# ASIC_card.net
KiCad netlist of a schematic drawn in EAGLE
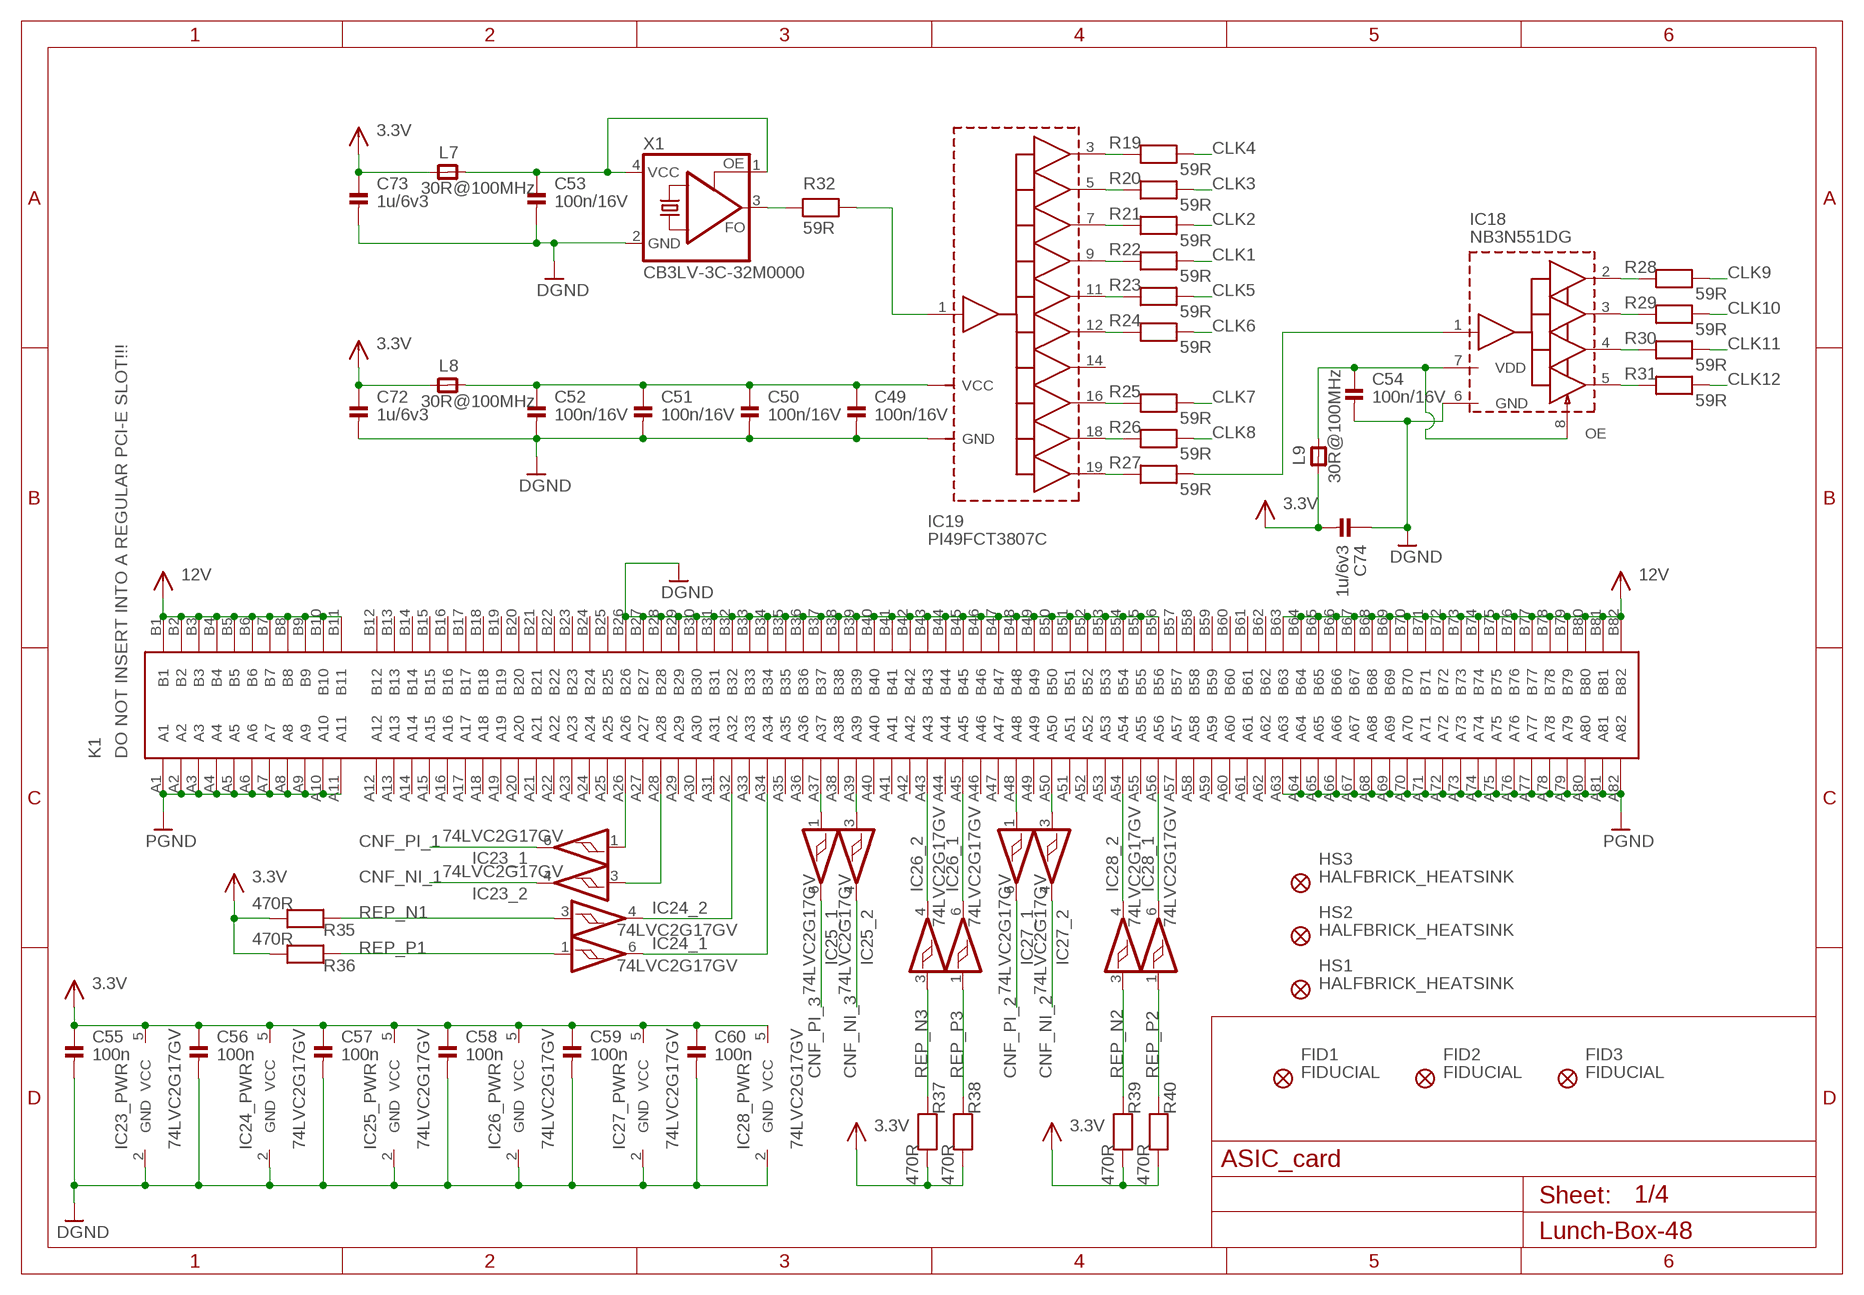
[diagram p0: schematic, sheet 1]
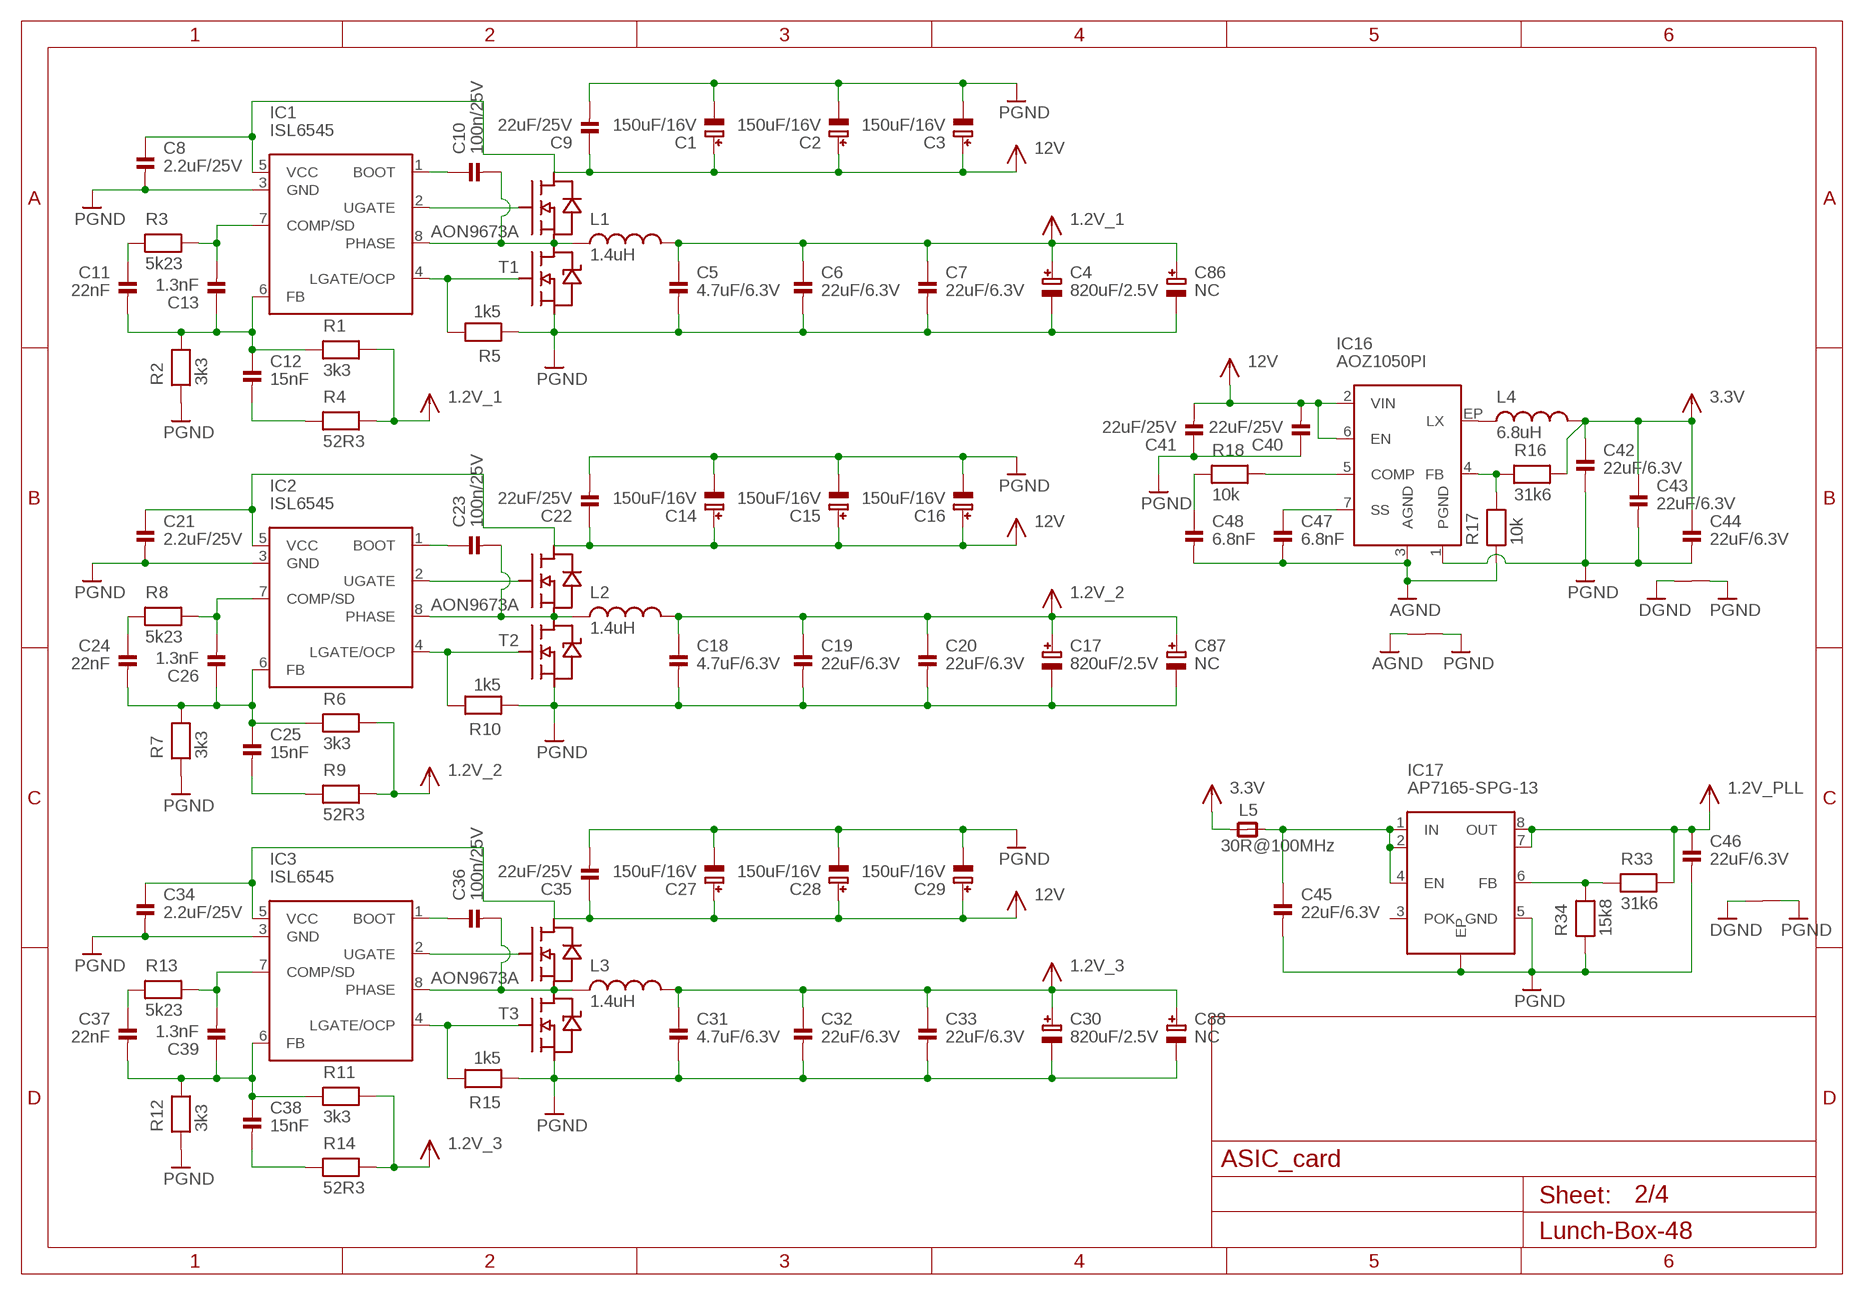
[diagram p1: schematic, sheet 2]
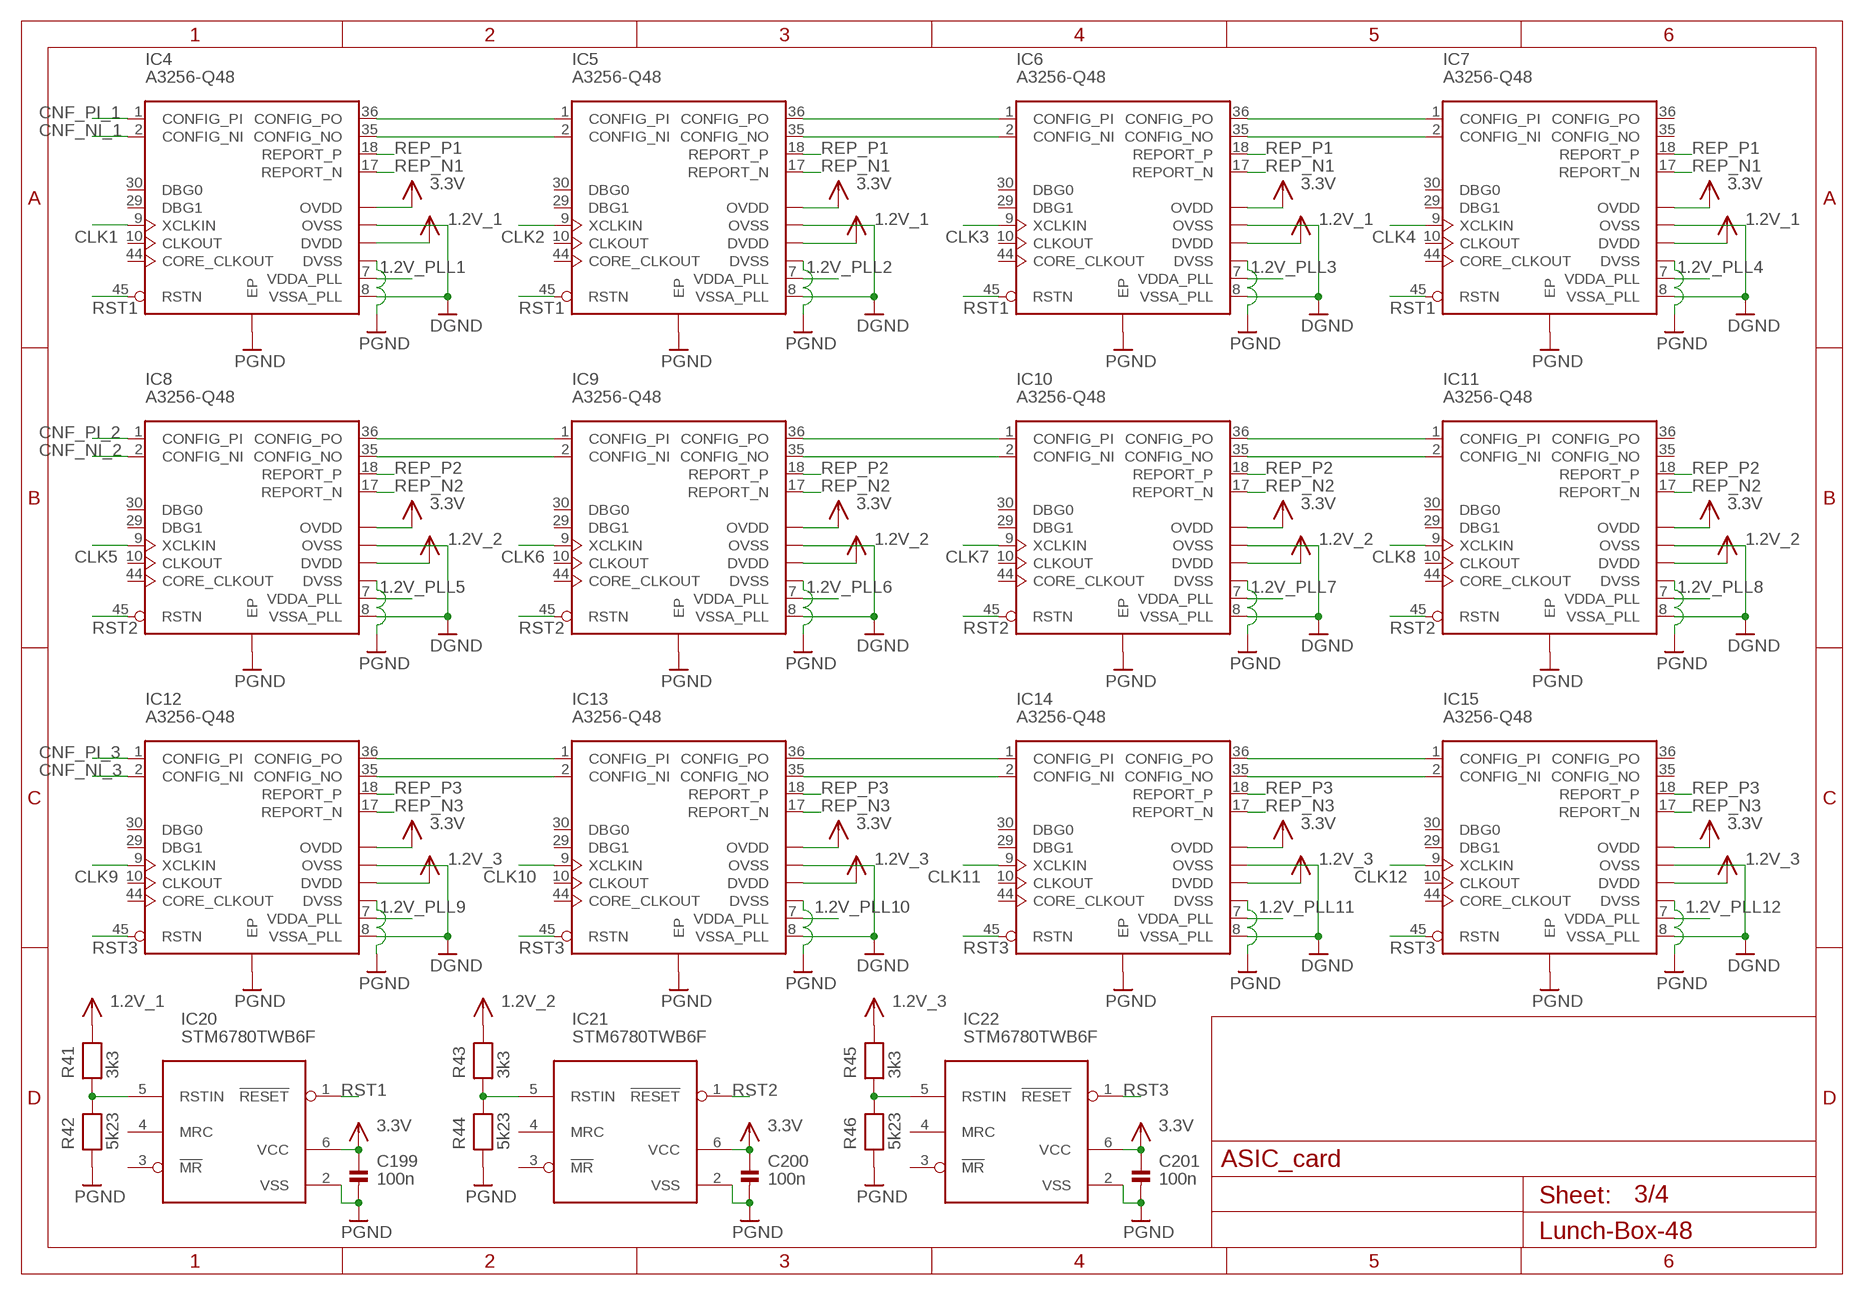
[diagram p2: schematic, sheet 3]
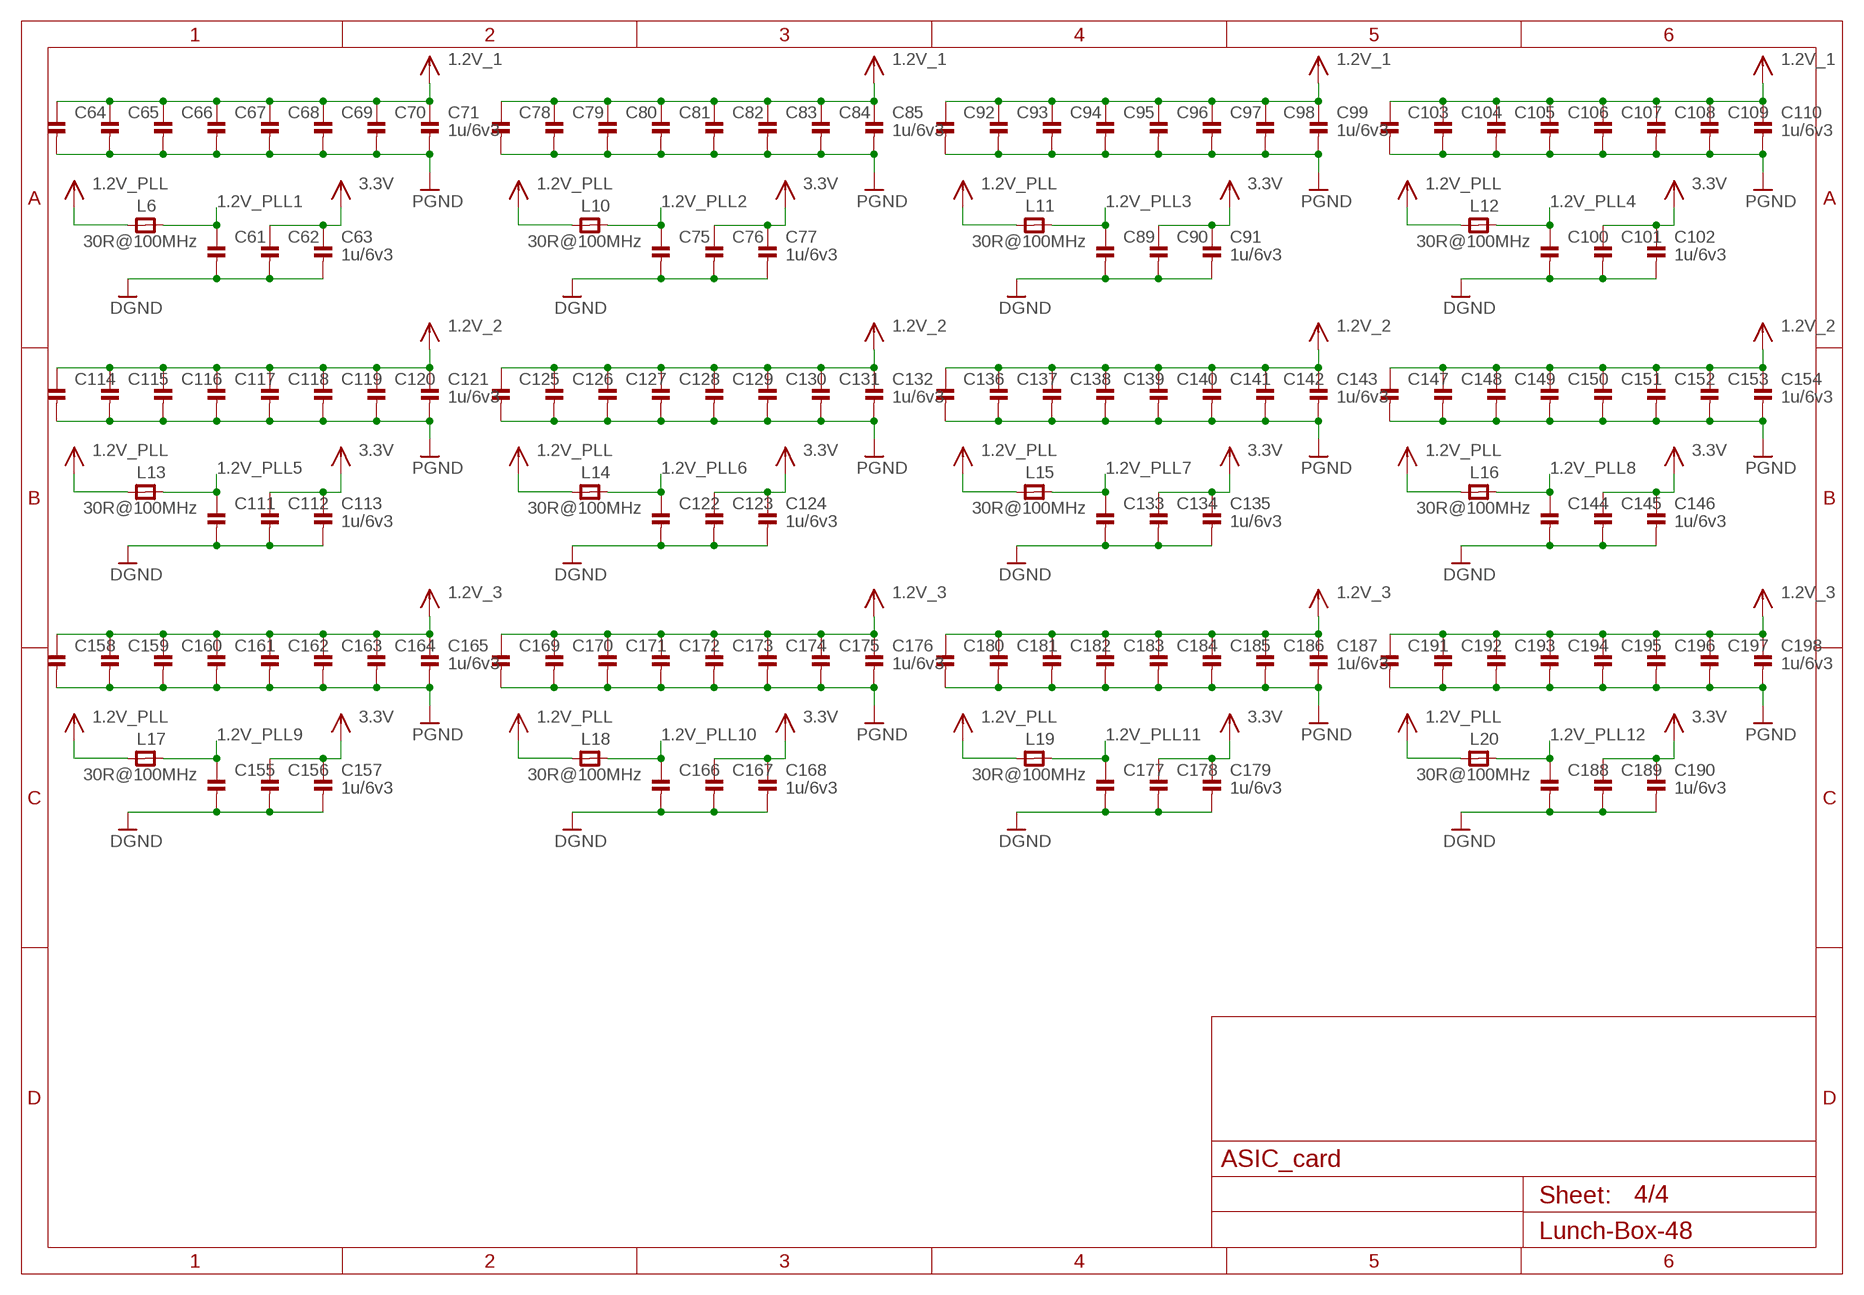
[diagram p3: schematic, sheet 4]

(export (version "E")
  (design (tool "Eeschema 10.0.6"))
  (components
    (comp (ref "C49")
      (value "100n/16V")
      (footprint "eagle-import:0402")
      (libsource (lib "eagle-import") (part "C0402"))
    )
    (comp (ref "C50")
      (value "100n/16V")
      (footprint "eagle-import:0402")
      (libsource (lib "eagle-import") (part "C0402"))
    )
    (comp (ref "C51")
      (value "100n/16V")
      (footprint "eagle-import:0402")
      (libsource (lib "eagle-import") (part "C0402"))
    )
    (comp (ref "C52")
      (value "100n/16V")
      (footprint "eagle-import:0402")
      (libsource (lib "eagle-import") (part "C0402"))
    )
    (comp (ref "C53")
      (value "100n/16V")
      (footprint "eagle-import:0402")
      (libsource (lib "eagle-import") (part "C0402"))
    )
    (comp (ref "C54")
      (value "100n/16V")
      (footprint "eagle-import:0402")
      (libsource (lib "eagle-import") (part "C0402"))
    )
    (comp (ref "C55")
      (value "100n")
      (footprint "eagle-import:0603")
      (libsource (lib "eagle-import") (part "C0603"))
    )
    (comp (ref "C56")
      (value "100n")
      (footprint "eagle-import:0603")
      (libsource (lib "eagle-import") (part "C0603"))
    )
    (comp (ref "C57")
      (value "100n")
      (footprint "eagle-import:0603")
      (libsource (lib "eagle-import") (part "C0603"))
    )
    (comp (ref "C58")
      (value "100n")
      (footprint "eagle-import:0603")
      (libsource (lib "eagle-import") (part "C0603"))
    )
    (comp (ref "C59")
      (value "100n")
      (footprint "eagle-import:0603")
      (libsource (lib "eagle-import") (part "C0603"))
    )
    (comp (ref "C60")
      (value "100n")
      (footprint "eagle-import:0603")
      (libsource (lib "eagle-import") (part "C0603"))
    )
    (comp (ref "C72")
      (value "1u/6v3")
      (footprint "eagle-import:0402")
      (libsource (lib "eagle-import") (part "C0402"))
    )
    (comp (ref "C73")
      (value "1u/6v3")
      (footprint "eagle-import:0402")
      (libsource (lib "eagle-import") (part "C0402"))
    )
    (comp (ref "C74")
      (value "1u/6v3")
      (footprint "eagle-import:0402")
      (libsource (lib "eagle-import") (part "C0402"))
    )
    (comp (ref "FID1")
      (value "FIDUCIAL")
      (footprint "eagle-import:FID_1X2,5")
      (libsource (lib "eagle-import") (part "FIDUCIAL"))
    )
    (comp (ref "FID2")
      (value "FIDUCIAL")
      (footprint "eagle-import:FID_1X2,5")
      (libsource (lib "eagle-import") (part "FIDUCIAL"))
    )
    (comp (ref "FID3")
      (value "FIDUCIAL")
      (footprint "eagle-import:FID_1X2,5")
      (libsource (lib "eagle-import") (part "FIDUCIAL"))
    )
    (comp (ref "HS1")
      (value "HALFBRICK_HEATSINK")
      (footprint "eagle-import:1_2_BRICK_HEATSINK")
      (libsource (lib "eagle-import") (part "HALFBRICK_HEATSINK"))
    )
    (comp (ref "HS2")
      (value "HALFBRICK_HEATSINK")
      (footprint "eagle-import:1_2_BRICK_HEATSINK")
      (libsource (lib "eagle-import") (part "HALFBRICK_HEATSINK"))
    )
    (comp (ref "HS3")
      (value "HALFBRICK_HEATSINK")
      (footprint "eagle-import:1_2_BRICK_HEATSINK")
      (libsource (lib "eagle-import") (part "HALFBRICK_HEATSINK"))
    )
    (comp (ref "IC18")
      (value "NB3N551DG")
      (footprint "eagle-import:SO-8")
      (libsource (lib "eagle-import") (part "NB3N551DG"))
    )
    (comp (ref "IC19")
      (value "PI49FCT3807C")
      (footprint "eagle-import:SSOP-20")
      (libsource (lib "eagle-import") (part "PI49FCT3807C"))
    )
    (comp (ref "IC23")
      (value "74LVC2G17GV")
      (footprint "eagle-import:SOT23-6")
      (libsource (lib "eagle-import") (part "74LVC2G17GV"))
    )
    (comp (ref "IC24")
      (value "74LVC2G17GV")
      (footprint "eagle-import:SOT23-6")
      (libsource (lib "eagle-import") (part "74LVC2G17GV"))
    )
    (comp (ref "IC25")
      (value "74LVC2G17GV")
      (footprint "eagle-import:SOT23-6")
      (libsource (lib "eagle-import") (part "74LVC2G17GV"))
    )
    (comp (ref "IC26")
      (value "74LVC2G17GV")
      (footprint "eagle-import:SOT23-6")
      (libsource (lib "eagle-import") (part "74LVC2G17GV"))
    )
    (comp (ref "IC27")
      (value "74LVC2G17GV")
      (footprint "eagle-import:SOT23-6")
      (libsource (lib "eagle-import") (part "74LVC2G17GV"))
    )
    (comp (ref "IC28")
      (value "74LVC2G17GV")
      (footprint "eagle-import:SOT23-6")
      (libsource (lib "eagle-import") (part "74LVC2G17GV"))
    )
    (comp (ref "K1")
      (value "DO NOT INSERT INTO A REGULAR PCI-E SLOT!!!")
      (footprint "eagle-import:PCI-E_16X")
      (libsource (lib "eagle-import") (part "PCI-E_CARDEDGE"))
    )
    (comp (ref "L7")
      (value "30R@100MHz")
      (footprint "eagle-import:0603")
      (libsource (lib "eagle-import") (part "FERRITE0603"))
    )
    (comp (ref "L8")
      (value "30R@100MHz")
      (footprint "eagle-import:0603")
      (libsource (lib "eagle-import") (part "FERRITE0603"))
    )
    (comp (ref "L9")
      (value "30R@100MHz")
      (footprint "eagle-import:0603")
      (libsource (lib "eagle-import") (part "FERRITE0603"))
    )
    (comp (ref "R19")
      (value "59R")
      (footprint "eagle-import:0402")
      (libsource (lib "eagle-import") (part "R0402"))
    )
    (comp (ref "R20")
      (value "59R")
      (footprint "eagle-import:0402")
      (libsource (lib "eagle-import") (part "R0402"))
    )
    (comp (ref "R21")
      (value "59R")
      (footprint "eagle-import:0402")
      (libsource (lib "eagle-import") (part "R0402"))
    )
    (comp (ref "R22")
      (value "59R")
      (footprint "eagle-import:0402")
      (libsource (lib "eagle-import") (part "R0402"))
    )
    (comp (ref "R23")
      (value "59R")
      (footprint "eagle-import:0402")
      (libsource (lib "eagle-import") (part "R0402"))
    )
    (comp (ref "R24")
      (value "59R")
      (footprint "eagle-import:0402")
      (libsource (lib "eagle-import") (part "R0402"))
    )
    (comp (ref "R25")
      (value "59R")
      (footprint "eagle-import:0402")
      (libsource (lib "eagle-import") (part "R0402"))
    )
    (comp (ref "R26")
      (value "59R")
      (footprint "eagle-import:0402")
      (libsource (lib "eagle-import") (part "R0402"))
    )
    (comp (ref "R27")
      (value "59R")
      (footprint "eagle-import:0402")
      (libsource (lib "eagle-import") (part "R0402"))
    )
    (comp (ref "R28")
      (value "59R")
      (footprint "eagle-import:0402")
      (libsource (lib "eagle-import") (part "R0402"))
    )
    (comp (ref "R29")
      (value "59R")
      (footprint "eagle-import:0402")
      (libsource (lib "eagle-import") (part "R0402"))
    )
    (comp (ref "R30")
      (value "59R")
      (footprint "eagle-import:0402")
      (libsource (lib "eagle-import") (part "R0402"))
    )
    (comp (ref "R31")
      (value "59R")
      (footprint "eagle-import:0402")
      (libsource (lib "eagle-import") (part "R0402"))
    )
    (comp (ref "R32")
      (value "59R")
      (footprint "eagle-import:0402")
      (libsource (lib "eagle-import") (part "R0402"))
    )
    (comp (ref "R35")
      (value "470R")
      (footprint "eagle-import:0603")
      (libsource (lib "eagle-import") (part "R0603"))
    )
    (comp (ref "R36")
      (value "470R")
      (footprint "eagle-import:0603")
      (libsource (lib "eagle-import") (part "R0603"))
    )
    (comp (ref "R37")
      (value "470R")
      (footprint "eagle-import:0603")
      (libsource (lib "eagle-import") (part "R0603"))
    )
    (comp (ref "R38")
      (value "470R")
      (footprint "eagle-import:0603")
      (libsource (lib "eagle-import") (part "R0603"))
    )
    (comp (ref "R39")
      (value "470R")
      (footprint "eagle-import:0603")
      (libsource (lib "eagle-import") (part "R0603"))
    )
    (comp (ref "R40")
      (value "470R")
      (footprint "eagle-import:0603")
      (libsource (lib "eagle-import") (part "R0603"))
    )
    (comp (ref "X1")
      (value "CB3LV-3C-32M0000")
      (footprint "eagle-import:7X5_OSC")
      (libsource (lib "eagle-import") (part "CB3LV-3C-32M0000"))
    )
    (comp (ref "C199")
      (value "100n")
      (footprint "eagle-import:0603")
      (libsource (lib "eagle-import") (part "C0603"))
    )
    (comp (ref "C200")
      (value "100n")
      (footprint "eagle-import:0603")
      (libsource (lib "eagle-import") (part "C0603"))
    )
    (comp (ref "C201")
      (value "100n")
      (footprint "eagle-import:0603")
      (libsource (lib "eagle-import") (part "C0603"))
    )
    (comp (ref "IC4")
      (value "A3256-Q48")
      (footprint "eagle-import:QFN48_EP")
      (libsource (lib "eagle-import") (part "A3256-Q48"))
    )
    (comp (ref "IC5")
      (value "A3256-Q48")
      (footprint "eagle-import:QFN48_EP")
      (libsource (lib "eagle-import") (part "A3256-Q48"))
    )
    (comp (ref "IC6")
      (value "A3256-Q48")
      (footprint "eagle-import:QFN48_EP")
      (libsource (lib "eagle-import") (part "A3256-Q48"))
    )
    (comp (ref "IC7")
      (value "A3256-Q48")
      (footprint "eagle-import:QFN48_EP")
      (libsource (lib "eagle-import") (part "A3256-Q48"))
    )
    (comp (ref "IC8")
      (value "A3256-Q48")
      (footprint "eagle-import:QFN48_EP")
      (libsource (lib "eagle-import") (part "A3256-Q48"))
    )
    (comp (ref "IC9")
      (value "A3256-Q48")
      (footprint "eagle-import:QFN48_EP")
      (libsource (lib "eagle-import") (part "A3256-Q48"))
    )
    (comp (ref "IC10")
      (value "A3256-Q48")
      (footprint "eagle-import:QFN48_EP")
      (libsource (lib "eagle-import") (part "A3256-Q48"))
    )
    (comp (ref "IC11")
      (value "A3256-Q48")
      (footprint "eagle-import:QFN48_EP")
      (libsource (lib "eagle-import") (part "A3256-Q48"))
    )
    (comp (ref "IC12")
      (value "A3256-Q48")
      (footprint "eagle-import:QFN48_EP")
      (libsource (lib "eagle-import") (part "A3256-Q48"))
    )
    (comp (ref "IC13")
      (value "A3256-Q48")
      (footprint "eagle-import:QFN48_EP")
      (libsource (lib "eagle-import") (part "A3256-Q48"))
    )
    (comp (ref "IC14")
      (value "A3256-Q48")
      (footprint "eagle-import:QFN48_EP")
      (libsource (lib "eagle-import") (part "A3256-Q48"))
    )
    (comp (ref "IC15")
      (value "A3256-Q48")
      (footprint "eagle-import:QFN48_EP")
      (libsource (lib "eagle-import") (part "A3256-Q48"))
    )
    (comp (ref "IC20")
      (value "STM6780TWB6F")
      (footprint "eagle-import:SOT23-6")
      (libsource (lib "eagle-import") (part "STM6780TWB6F"))
    )
    (comp (ref "IC21")
      (value "STM6780TWB6F")
      (footprint "eagle-import:SOT23-6")
      (libsource (lib "eagle-import") (part "STM6780TWB6F"))
    )
    (comp (ref "IC22")
      (value "STM6780TWB6F")
      (footprint "eagle-import:SOT23-6")
      (libsource (lib "eagle-import") (part "STM6780TWB6F"))
    )
    (comp (ref "R41")
      (value "3k3")
      (footprint "eagle-import:0603")
      (libsource (lib "eagle-import") (part "R0603"))
    )
    (comp (ref "R42")
      (value "5k23")
      (footprint "eagle-import:0603")
      (libsource (lib "eagle-import") (part "R0603"))
    )
    (comp (ref "R43")
      (value "3k3")
      (footprint "eagle-import:0603")
      (libsource (lib "eagle-import") (part "R0603"))
    )
    (comp (ref "R44")
      (value "5k23")
      (footprint "eagle-import:0603")
      (libsource (lib "eagle-import") (part "R0603"))
    )
    (comp (ref "R45")
      (value "3k3")
      (footprint "eagle-import:0603")
      (libsource (lib "eagle-import") (part "R0603"))
    )
    (comp (ref "R46")
      (value "5k23")
      (footprint "eagle-import:0603")
      (libsource (lib "eagle-import") (part "R0603"))
    )
    (comp (ref "C61")
      (value "1u/6v3")
      (footprint "eagle-import:0402")
      (libsource (lib "eagle-import") (part "C0402"))
    )
    (comp (ref "C62")
      (value "1u/6v3")
      (footprint "eagle-import:0402")
      (libsource (lib "eagle-import") (part "C0402"))
    )
    (comp (ref "C63")
      (value "1u/6v3")
      (footprint "eagle-import:0402")
      (libsource (lib "eagle-import") (part "C0402"))
    )
    (comp (ref "C64")
      (value "1u/6v3")
      (footprint "eagle-import:0402")
      (libsource (lib "eagle-import") (part "C0402"))
    )
    (comp (ref "C65")
      (value "1u/6v3")
      (footprint "eagle-import:0402")
      (libsource (lib "eagle-import") (part "C0402"))
    )
    (comp (ref "C66")
      (value "1u/6v3")
      (footprint "eagle-import:0402")
      (libsource (lib "eagle-import") (part "C0402"))
    )
    (comp (ref "C67")
      (value "1u/6v3")
      (footprint "eagle-import:0402")
      (libsource (lib "eagle-import") (part "C0402"))
    )
    (comp (ref "C68")
      (value "1u/6v3")
      (footprint "eagle-import:0402")
      (libsource (lib "eagle-import") (part "C0402"))
    )
    (comp (ref "C69")
      (value "1u/6v3")
      (footprint "eagle-import:0402")
      (libsource (lib "eagle-import") (part "C0402"))
    )
    (comp (ref "C70")
      (value "1u/6v3")
      (footprint "eagle-import:0402")
      (libsource (lib "eagle-import") (part "C0402"))
    )
    (comp (ref "C71")
      (value "1u/6v3")
      (footprint "eagle-import:0402")
      (libsource (lib "eagle-import") (part "C0402"))
    )
    (comp (ref "C75")
      (value "1u/6v3")
      (footprint "eagle-import:0402")
      (libsource (lib "eagle-import") (part "C0402"))
    )
    (comp (ref "C76")
      (value "1u/6v3")
      (footprint "eagle-import:0402")
      (libsource (lib "eagle-import") (part "C0402"))
    )
    (comp (ref "C77")
      (value "1u/6v3")
      (footprint "eagle-import:0402")
      (libsource (lib "eagle-import") (part "C0402"))
    )
    (comp (ref "C78")
      (value "1u/6v3")
      (footprint "eagle-import:0402")
      (libsource (lib "eagle-import") (part "C0402"))
    )
    (comp (ref "C79")
      (value "1u/6v3")
      (footprint "eagle-import:0402")
      (libsource (lib "eagle-import") (part "C0402"))
    )
    (comp (ref "C80")
      (value "1u/6v3")
      (footprint "eagle-import:0402")
      (libsource (lib "eagle-import") (part "C0402"))
    )
    (comp (ref "C81")
      (value "1u/6v3")
      (footprint "eagle-import:0402")
      (libsource (lib "eagle-import") (part "C0402"))
    )
    (comp (ref "C82")
      (value "1u/6v3")
      (footprint "eagle-import:0402")
      (libsource (lib "eagle-import") (part "C0402"))
    )
    (comp (ref "C83")
      (value "1u/6v3")
      (footprint "eagle-import:0402")
      (libsource (lib "eagle-import") (part "C0402"))
    )
    (comp (ref "C84")
      (value "1u/6v3")
      (footprint "eagle-import:0402")
      (libsource (lib "eagle-import") (part "C0402"))
    )
    (comp (ref "C85")
      (value "1u/6v3")
      (footprint "eagle-import:0402")
      (libsource (lib "eagle-import") (part "C0402"))
    )
    (comp (ref "C89")
      (value "1u/6v3")
      (footprint "eagle-import:0402")
      (libsource (lib "eagle-import") (part "C0402"))
    )
    (comp (ref "C90")
      (value "1u/6v3")
      (footprint "eagle-import:0402")
      (libsource (lib "eagle-import") (part "C0402"))
    )
    (comp (ref "C91")
      (value "1u/6v3")
      (footprint "eagle-import:0402")
      (libsource (lib "eagle-import") (part "C0402"))
    )
    (comp (ref "C92")
      (value "1u/6v3")
      (footprint "eagle-import:0402")
      (libsource (lib "eagle-import") (part "C0402"))
    )
    (comp (ref "C93")
      (value "1u/6v3")
      (footprint "eagle-import:0402")
      (libsource (lib "eagle-import") (part "C0402"))
    )
    (comp (ref "C94")
      (value "1u/6v3")
      (footprint "eagle-import:0402")
      (libsource (lib "eagle-import") (part "C0402"))
    )
    (comp (ref "C95")
      (value "1u/6v3")
      (footprint "eagle-import:0402")
      (libsource (lib "eagle-import") (part "C0402"))
    )
    (comp (ref "C96")
      (value "1u/6v3")
      (footprint "eagle-import:0402")
      (libsource (lib "eagle-import") (part "C0402"))
    )
    (comp (ref "C97")
      (value "1u/6v3")
      (footprint "eagle-import:0402")
      (libsource (lib "eagle-import") (part "C0402"))
    )
    (comp (ref "C98")
      (value "1u/6v3")
      (footprint "eagle-import:0402")
      (libsource (lib "eagle-import") (part "C0402"))
    )
    (comp (ref "C99")
      (value "1u/6v3")
      (footprint "eagle-import:0402")
      (libsource (lib "eagle-import") (part "C0402"))
    )
    (comp (ref "C100")
      (value "1u/6v3")
      (footprint "eagle-import:0402")
      (libsource (lib "eagle-import") (part "C0402"))
    )
    (comp (ref "C101")
      (value "1u/6v3")
      (footprint "eagle-import:0402")
      (libsource (lib "eagle-import") (part "C0402"))
    )
    (comp (ref "C102")
      (value "1u/6v3")
      (footprint "eagle-import:0402")
      (libsource (lib "eagle-import") (part "C0402"))
    )
    (comp (ref "C103")
      (value "1u/6v3")
      (footprint "eagle-import:0402")
      (libsource (lib "eagle-import") (part "C0402"))
    )
    (comp (ref "C104")
      (value "1u/6v3")
      (footprint "eagle-import:0402")
      (libsource (lib "eagle-import") (part "C0402"))
    )
    (comp (ref "C105")
      (value "1u/6v3")
      (footprint "eagle-import:0402")
      (libsource (lib "eagle-import") (part "C0402"))
    )
    (comp (ref "C106")
      (value "1u/6v3")
      (footprint "eagle-import:0402")
      (libsource (lib "eagle-import") (part "C0402"))
    )
    (comp (ref "C107")
      (value "1u/6v3")
      (footprint "eagle-import:0402")
      (libsource (lib "eagle-import") (part "C0402"))
    )
    (comp (ref "C108")
      (value "1u/6v3")
      (footprint "eagle-import:0402")
      (libsource (lib "eagle-import") (part "C0402"))
    )
    (comp (ref "C109")
      (value "1u/6v3")
      (footprint "eagle-import:0402")
      (libsource (lib "eagle-import") (part "C0402"))
    )
    (comp (ref "C110")
      (value "1u/6v3")
      (footprint "eagle-import:0402")
      (libsource (lib "eagle-import") (part "C0402"))
    )
    (comp (ref "C111")
      (value "1u/6v3")
      (footprint "eagle-import:0402")
      (libsource (lib "eagle-import") (part "C0402"))
    )
    (comp (ref "C112")
      (value "1u/6v3")
      (footprint "eagle-import:0402")
      (libsource (lib "eagle-import") (part "C0402"))
    )
    (comp (ref "C113")
      (value "1u/6v3")
      (footprint "eagle-import:0402")
      (libsource (lib "eagle-import") (part "C0402"))
    )
    (comp (ref "C114")
      (value "1u/6v3")
      (footprint "eagle-import:0402")
      (libsource (lib "eagle-import") (part "C0402"))
    )
    (comp (ref "C115")
      (value "1u/6v3")
      (footprint "eagle-import:0402")
      (libsource (lib "eagle-import") (part "C0402"))
    )
    (comp (ref "C116")
      (value "1u/6v3")
      (footprint "eagle-import:0402")
      (libsource (lib "eagle-import") (part "C0402"))
    )
    (comp (ref "C117")
      (value "1u/6v3")
      (footprint "eagle-import:0402")
      (libsource (lib "eagle-import") (part "C0402"))
    )
    (comp (ref "C118")
      (value "1u/6v3")
      (footprint "eagle-import:0402")
      (libsource (lib "eagle-import") (part "C0402"))
    )
    (comp (ref "C119")
      (value "1u/6v3")
      (footprint "eagle-import:0402")
      (libsource (lib "eagle-import") (part "C0402"))
    )
    (comp (ref "C120")
      (value "1u/6v3")
      (footprint "eagle-import:0402")
      (libsource (lib "eagle-import") (part "C0402"))
    )
    (comp (ref "C121")
      (value "1u/6v3")
      (footprint "eagle-import:0402")
      (libsource (lib "eagle-import") (part "C0402"))
    )
    (comp (ref "C122")
      (value "1u/6v3")
      (footprint "eagle-import:0402")
      (libsource (lib "eagle-import") (part "C0402"))
    )
    (comp (ref "C123")
      (value "1u/6v3")
      (footprint "eagle-import:0402")
      (libsource (lib "eagle-import") (part "C0402"))
    )
    (comp (ref "C124")
      (value "1u/6v3")
      (footprint "eagle-import:0402")
      (libsource (lib "eagle-import") (part "C0402"))
    )
    (comp (ref "C125")
      (value "1u/6v3")
      (footprint "eagle-import:0402")
      (libsource (lib "eagle-import") (part "C0402"))
    )
    (comp (ref "C126")
      (value "1u/6v3")
      (footprint "eagle-import:0402")
      (libsource (lib "eagle-import") (part "C0402"))
    )
    (comp (ref "C127")
      (value "1u/6v3")
      (footprint "eagle-import:0402")
      (libsource (lib "eagle-import") (part "C0402"))
    )
    (comp (ref "C128")
      (value "1u/6v3")
      (footprint "eagle-import:0402")
      (libsource (lib "eagle-import") (part "C0402"))
    )
    (comp (ref "C129")
      (value "1u/6v3")
      (footprint "eagle-import:0402")
      (libsource (lib "eagle-import") (part "C0402"))
    )
    (comp (ref "C130")
      (value "1u/6v3")
      (footprint "eagle-import:0402")
      (libsource (lib "eagle-import") (part "C0402"))
    )
    (comp (ref "C131")
      (value "1u/6v3")
      (footprint "eagle-import:0402")
      (libsource (lib "eagle-import") (part "C0402"))
    )
    (comp (ref "C132")
      (value "1u/6v3")
      (footprint "eagle-import:0402")
      (libsource (lib "eagle-import") (part "C0402"))
    )
    (comp (ref "C133")
      (value "1u/6v3")
      (footprint "eagle-import:0402")
      (libsource (lib "eagle-import") (part "C0402"))
    )
    (comp (ref "C134")
      (value "1u/6v3")
      (footprint "eagle-import:0402")
      (libsource (lib "eagle-import") (part "C0402"))
    )
    (comp (ref "C135")
      (value "1u/6v3")
      (footprint "eagle-import:0402")
      (libsource (lib "eagle-import") (part "C0402"))
    )
    (comp (ref "C136")
      (value "1u/6v3")
      (footprint "eagle-import:0402")
      (libsource (lib "eagle-import") (part "C0402"))
    )
    (comp (ref "C137")
      (value "1u/6v3")
      (footprint "eagle-import:0402")
      (libsource (lib "eagle-import") (part "C0402"))
    )
    (comp (ref "C138")
      (value "1u/6v3")
      (footprint "eagle-import:0402")
      (libsource (lib "eagle-import") (part "C0402"))
    )
    (comp (ref "C139")
      (value "1u/6v3")
      (footprint "eagle-import:0402")
      (libsource (lib "eagle-import") (part "C0402"))
    )
    (comp (ref "C140")
      (value "1u/6v3")
      (footprint "eagle-import:0402")
      (libsource (lib "eagle-import") (part "C0402"))
    )
    (comp (ref "C141")
      (value "1u/6v3")
      (footprint "eagle-import:0402")
      (libsource (lib "eagle-import") (part "C0402"))
    )
    (comp (ref "C142")
      (value "1u/6v3")
      (footprint "eagle-import:0402")
      (libsource (lib "eagle-import") (part "C0402"))
    )
    (comp (ref "C143")
      (value "1u/6v3")
      (footprint "eagle-import:0402")
      (libsource (lib "eagle-import") (part "C0402"))
    )
    (comp (ref "C144")
      (value "1u/6v3")
      (footprint "eagle-import:0402")
      (libsource (lib "eagle-import") (part "C0402"))
    )
    (comp (ref "C145")
      (value "1u/6v3")
      (footprint "eagle-import:0402")
      (libsource (lib "eagle-import") (part "C0402"))
    )
    (comp (ref "C146")
      (value "1u/6v3")
      (footprint "eagle-import:0402")
      (libsource (lib "eagle-import") (part "C0402"))
    )
    (comp (ref "C147")
      (value "1u/6v3")
      (footprint "eagle-import:0402")
      (libsource (lib "eagle-import") (part "C0402"))
    )
    (comp (ref "C148")
      (value "1u/6v3")
      (footprint "eagle-import:0402")
      (libsource (lib "eagle-import") (part "C0402"))
    )
    (comp (ref "C149")
      (value "1u/6v3")
      (footprint "eagle-import:0402")
      (libsource (lib "eagle-import") (part "C0402"))
    )
    (comp (ref "C150")
      (value "1u/6v3")
      (footprint "eagle-import:0402")
      (libsource (lib "eagle-import") (part "C0402"))
    )
    (comp (ref "C151")
      (value "1u/6v3")
      (footprint "eagle-import:0402")
      (libsource (lib "eagle-import") (part "C0402"))
    )
    (comp (ref "C152")
      (value "1u/6v3")
      (footprint "eagle-import:0402")
      (libsource (lib "eagle-import") (part "C0402"))
    )
    (comp (ref "C153")
      (value "1u/6v3")
      (footprint "eagle-import:0402")
      (libsource (lib "eagle-import") (part "C0402"))
    )
    (comp (ref "C154")
      (value "1u/6v3")
      (footprint "eagle-import:0402")
      (libsource (lib "eagle-import") (part "C0402"))
    )
    (comp (ref "C155")
      (value "1u/6v3")
      (footprint "eagle-import:0402")
      (libsource (lib "eagle-import") (part "C0402"))
    )
    (comp (ref "C156")
      (value "1u/6v3")
      (footprint "eagle-import:0402")
      (libsource (lib "eagle-import") (part "C0402"))
    )
    (comp (ref "C157")
      (value "1u/6v3")
      (footprint "eagle-import:0402")
      (libsource (lib "eagle-import") (part "C0402"))
    )
    (comp (ref "C158")
      (value "1u/6v3")
      (footprint "eagle-import:0402")
      (libsource (lib "eagle-import") (part "C0402"))
    )
    (comp (ref "C159")
      (value "1u/6v3")
      (footprint "eagle-import:0402")
      (libsource (lib "eagle-import") (part "C0402"))
    )
    (comp (ref "C160")
      (value "1u/6v3")
      (footprint "eagle-import:0402")
      (libsource (lib "eagle-import") (part "C0402"))
    )
    (comp (ref "C161")
      (value "1u/6v3")
      (footprint "eagle-import:0402")
      (libsource (lib "eagle-import") (part "C0402"))
    )
    (comp (ref "C162")
      (value "1u/6v3")
      (footprint "eagle-import:0402")
      (libsource (lib "eagle-import") (part "C0402"))
    )
    (comp (ref "C163")
      (value "1u/6v3")
      (footprint "eagle-import:0402")
      (libsource (lib "eagle-import") (part "C0402"))
    )
    (comp (ref "C164")
      (value "1u/6v3")
      (footprint "eagle-import:0402")
      (libsource (lib "eagle-import") (part "C0402"))
    )
    (comp (ref "C165")
      (value "1u/6v3")
      (footprint "eagle-import:0402")
      (libsource (lib "eagle-import") (part "C0402"))
    )
    (comp (ref "C166")
      (value "1u/6v3")
      (footprint "eagle-import:0402")
      (libsource (lib "eagle-import") (part "C0402"))
    )
    (comp (ref "C167")
      (value "1u/6v3")
      (footprint "eagle-import:0402")
      (libsource (lib "eagle-import") (part "C0402"))
    )
    (comp (ref "C168")
      (value "1u/6v3")
      (footprint "eagle-import:0402")
      (libsource (lib "eagle-import") (part "C0402"))
    )
    (comp (ref "C169")
      (value "1u/6v3")
      (footprint "eagle-import:0402")
      (libsource (lib "eagle-import") (part "C0402"))
    )
    (comp (ref "C170")
      (value "1u/6v3")
      (footprint "eagle-import:0402")
      (libsource (lib "eagle-import") (part "C0402"))
    )
    (comp (ref "C171")
      (value "1u/6v3")
      (footprint "eagle-import:0402")
      (libsource (lib "eagle-import") (part "C0402"))
    )
    (comp (ref "C172")
      (value "1u/6v3")
      (footprint "eagle-import:0402")
      (libsource (lib "eagle-import") (part "C0402"))
    )
    (comp (ref "C173")
      (value "1u/6v3")
      (footprint "eagle-import:0402")
      (libsource (lib "eagle-import") (part "C0402"))
    )
    (comp (ref "C174")
      (value "1u/6v3")
      (footprint "eagle-import:0402")
      (libsource (lib "eagle-import") (part "C0402"))
    )
    (comp (ref "C175")
      (value "1u/6v3")
      (footprint "eagle-import:0402")
      (libsource (lib "eagle-import") (part "C0402"))
    )
    (comp (ref "C176")
      (value "1u/6v3")
      (footprint "eagle-import:0402")
      (libsource (lib "eagle-import") (part "C0402"))
    )
    (comp (ref "C177")
      (value "1u/6v3")
      (footprint "eagle-import:0402")
      (libsource (lib "eagle-import") (part "C0402"))
    )
    (comp (ref "C178")
      (value "1u/6v3")
      (footprint "eagle-import:0402")
      (libsource (lib "eagle-import") (part "C0402"))
    )
    (comp (ref "C179")
      (value "1u/6v3")
      (footprint "eagle-import:0402")
      (libsource (lib "eagle-import") (part "C0402"))
    )
    (comp (ref "C180")
      (value "1u/6v3")
      (footprint "eagle-import:0402")
      (libsource (lib "eagle-import") (part "C0402"))
    )
    (comp (ref "C181")
      (value "1u/6v3")
      (footprint "eagle-import:0402")
      (libsource (lib "eagle-import") (part "C0402"))
    )
    (comp (ref "C182")
      (value "1u/6v3")
      (footprint "eagle-import:0402")
      (libsource (lib "eagle-import") (part "C0402"))
    )
    (comp (ref "C183")
      (value "1u/6v3")
      (footprint "eagle-import:0402")
      (libsource (lib "eagle-import") (part "C0402"))
    )
    (comp (ref "C184")
      (value "1u/6v3")
      (footprint "eagle-import:0402")
      (libsource (lib "eagle-import") (part "C0402"))
    )
    (comp (ref "C185")
      (value "1u/6v3")
      (footprint "eagle-import:0402")
      (libsource (lib "eagle-import") (part "C0402"))
    )
    (comp (ref "C186")
      (value "1u/6v3")
      (footprint "eagle-import:0402")
      (libsource (lib "eagle-import") (part "C0402"))
    )
    (comp (ref "C187")
      (value "1u/6v3")
      (footprint "eagle-import:0402")
      (libsource (lib "eagle-import") (part "C0402"))
    )
    (comp (ref "C188")
      (value "1u/6v3")
      (footprint "eagle-import:0402")
      (libsource (lib "eagle-import") (part "C0402"))
    )
    (comp (ref "C189")
      (value "1u/6v3")
      (footprint "eagle-import:0402")
      (libsource (lib "eagle-import") (part "C0402"))
    )
    (comp (ref "C190")
      (value "1u/6v3")
      (footprint "eagle-import:0402")
      (libsource (lib "eagle-import") (part "C0402"))
    )
    (comp (ref "C191")
      (value "1u/6v3")
      (footprint "eagle-import:0402")
      (libsource (lib "eagle-import") (part "C0402"))
    )
    (comp (ref "C192")
      (value "1u/6v3")
      (footprint "eagle-import:0402")
      (libsource (lib "eagle-import") (part "C0402"))
    )
    (comp (ref "C193")
      (value "1u/6v3")
      (footprint "eagle-import:0402")
      (libsource (lib "eagle-import") (part "C0402"))
    )
    (comp (ref "C194")
      (value "1u/6v3")
      (footprint "eagle-import:0402")
      (libsource (lib "eagle-import") (part "C0402"))
    )
    (comp (ref "C195")
      (value "1u/6v3")
      (footprint "eagle-import:0402")
      (libsource (lib "eagle-import") (part "C0402"))
    )
    (comp (ref "C196")
      (value "1u/6v3")
      (footprint "eagle-import:0402")
      (libsource (lib "eagle-import") (part "C0402"))
    )
    (comp (ref "C197")
      (value "1u/6v3")
      (footprint "eagle-import:0402")
      (libsource (lib "eagle-import") (part "C0402"))
    )
    (comp (ref "C198")
      (value "1u/6v3")
      (footprint "eagle-import:0402")
      (libsource (lib "eagle-import") (part "C0402"))
    )
    (comp (ref "L6")
      (value "30R@100MHz")
      (footprint "eagle-import:0603")
      (libsource (lib "eagle-import") (part "FERRITE0603"))
    )
    (comp (ref "L10")
      (value "30R@100MHz")
      (footprint "eagle-import:0603")
      (libsource (lib "eagle-import") (part "FERRITE0603"))
    )
    (comp (ref "L11")
      (value "30R@100MHz")
      (footprint "eagle-import:0603")
      (libsource (lib "eagle-import") (part "FERRITE0603"))
    )
    (comp (ref "L12")
      (value "30R@100MHz")
      (footprint "eagle-import:0603")
      (libsource (lib "eagle-import") (part "FERRITE0603"))
    )
    (comp (ref "L13")
      (value "30R@100MHz")
      (footprint "eagle-import:0603")
      (libsource (lib "eagle-import") (part "FERRITE0603"))
    )
    (comp (ref "L14")
      (value "30R@100MHz")
      (footprint "eagle-import:0603")
      (libsource (lib "eagle-import") (part "FERRITE0603"))
    )
    (comp (ref "L15")
      (value "30R@100MHz")
      (footprint "eagle-import:0603")
      (libsource (lib "eagle-import") (part "FERRITE0603"))
    )
    (comp (ref "L16")
      (value "30R@100MHz")
      (footprint "eagle-import:0603")
      (libsource (lib "eagle-import") (part "FERRITE0603"))
    )
    (comp (ref "L17")
      (value "30R@100MHz")
      (footprint "eagle-import:0603")
      (libsource (lib "eagle-import") (part "FERRITE0603"))
    )
    (comp (ref "L18")
      (value "30R@100MHz")
      (footprint "eagle-import:0603")
      (libsource (lib "eagle-import") (part "FERRITE0603"))
    )
    (comp (ref "L19")
      (value "30R@100MHz")
      (footprint "eagle-import:0603")
      (libsource (lib "eagle-import") (part "FERRITE0603"))
    )
    (comp (ref "L20")
      (value "30R@100MHz")
      (footprint "eagle-import:0603")
      (libsource (lib "eagle-import") (part "FERRITE0603"))
    )
    (comp (ref "C1")
      (value "150uF/16V")
      (footprint "eagle-import:CAP_POL_8MM")
      (libsource (lib "eagle-import") (part "C_POL"))
    )
    (comp (ref "C2")
      (value "150uF/16V")
      (footprint "eagle-import:CAP_POL_8MM")
      (libsource (lib "eagle-import") (part "C_POL"))
    )
    (comp (ref "C3")
      (value "150uF/16V")
      (footprint "eagle-import:CAP_POL_8MM")
      (libsource (lib "eagle-import") (part "C_POL"))
    )
    (comp (ref "C4")
      (value "820uF/2.5V")
      (footprint "eagle-import:CAP_POL_8MM")
      (libsource (lib "eagle-import") (part "C_POL"))
    )
    (comp (ref "C5")
      (value "4.7uF/6.3V")
      (footprint "eagle-import:0306")
      (libsource (lib "eagle-import") (part "C0306"))
    )
    (comp (ref "C6")
      (value "22uF/6.3V")
      (footprint "eagle-import:0805")
      (libsource (lib "eagle-import") (part "C0805"))
    )
    (comp (ref "C7")
      (value "22uF/6.3V")
      (footprint "eagle-import:0805")
      (libsource (lib "eagle-import") (part "C0805"))
    )
    (comp (ref "C8")
      (value "2.2uF/25V")
      (footprint "eagle-import:0603")
      (libsource (lib "eagle-import") (part "C0603"))
    )
    (comp (ref "C9")
      (value "22uF/25V")
      (footprint "eagle-import:1210")
      (libsource (lib "eagle-import") (part "C1210"))
    )
    (comp (ref "C10")
      (value "100n/25V")
      (footprint "eagle-import:0603")
      (libsource (lib "eagle-import") (part "C0603"))
    )
    (comp (ref "C11")
      (value "22nF")
      (footprint "eagle-import:0603")
      (libsource (lib "eagle-import") (part "C0603"))
    )
    (comp (ref "C12")
      (value "15nF")
      (footprint "eagle-import:0603")
      (libsource (lib "eagle-import") (part "C0603"))
    )
    (comp (ref "C13")
      (value "1.3nF")
      (footprint "eagle-import:0603")
      (libsource (lib "eagle-import") (part "C0603"))
    )
    (comp (ref "C14")
      (value "150uF/16V")
      (footprint "eagle-import:CAP_POL_8MM")
      (libsource (lib "eagle-import") (part "C_POL"))
    )
    (comp (ref "C15")
      (value "150uF/16V")
      (footprint "eagle-import:CAP_POL_8MM")
      (libsource (lib "eagle-import") (part "C_POL"))
    )
    (comp (ref "C16")
      (value "150uF/16V")
      (footprint "eagle-import:CAP_POL_8MM")
      (libsource (lib "eagle-import") (part "C_POL"))
    )
    (comp (ref "C17")
      (value "820uF/2.5V")
      (footprint "eagle-import:CAP_POL_8MM")
      (libsource (lib "eagle-import") (part "C_POL"))
    )
    (comp (ref "C18")
      (value "4.7uF/6.3V")
      (footprint "eagle-import:0306")
      (libsource (lib "eagle-import") (part "C0306"))
    )
    (comp (ref "C19")
      (value "22uF/6.3V")
      (footprint "eagle-import:0805")
      (libsource (lib "eagle-import") (part "C0805"))
    )
    (comp (ref "C20")
      (value "22uF/6.3V")
      (footprint "eagle-import:0805")
      (libsource (lib "eagle-import") (part "C0805"))
    )
    (comp (ref "C21")
      (value "2.2uF/25V")
      (footprint "eagle-import:0603")
      (libsource (lib "eagle-import") (part "C0603"))
    )
    (comp (ref "C22")
      (value "22uF/25V")
      (footprint "eagle-import:1210")
      (libsource (lib "eagle-import") (part "C1210"))
    )
    (comp (ref "C23")
      (value "100n/25V")
      (footprint "eagle-import:0603")
      (libsource (lib "eagle-import") (part "C0603"))
    )
    (comp (ref "C24")
      (value "22nF")
      (footprint "eagle-import:0603")
      (libsource (lib "eagle-import") (part "C0603"))
    )
    (comp (ref "C25")
      (value "15nF")
      (footprint "eagle-import:0603")
      (libsource (lib "eagle-import") (part "C0603"))
    )
    (comp (ref "C26")
      (value "1.3nF")
      (footprint "eagle-import:0603")
      (libsource (lib "eagle-import") (part "C0603"))
    )
    (comp (ref "C27")
      (value "150uF/16V")
      (footprint "eagle-import:CAP_POL_8MM")
      (libsource (lib "eagle-import") (part "C_POL"))
    )
    (comp (ref "C28")
      (value "150uF/16V")
      (footprint "eagle-import:CAP_POL_8MM")
      (libsource (lib "eagle-import") (part "C_POL"))
    )
    (comp (ref "C29")
      (value "150uF/16V")
      (footprint "eagle-import:CAP_POL_8MM")
      (libsource (lib "eagle-import") (part "C_POL"))
    )
    (comp (ref "C30")
      (value "820uF/2.5V")
      (footprint "eagle-import:CAP_POL_8MM")
      (libsource (lib "eagle-import") (part "C_POL"))
    )
    (comp (ref "C31")
      (value "4.7uF/6.3V")
      (footprint "eagle-import:0306")
      (libsource (lib "eagle-import") (part "C0306"))
    )
    (comp (ref "C32")
      (value "22uF/6.3V")
      (footprint "eagle-import:0805")
      (libsource (lib "eagle-import") (part "C0805"))
    )
    (comp (ref "C33")
      (value "22uF/6.3V")
      (footprint "eagle-import:0805")
      (libsource (lib "eagle-import") (part "C0805"))
    )
    (comp (ref "C34")
      (value "2.2uF/25V")
      (footprint "eagle-import:0603")
      (libsource (lib "eagle-import") (part "C0603"))
    )
    (comp (ref "C35")
      (value "22uF/25V")
      (footprint "eagle-import:1210")
      (libsource (lib "eagle-import") (part "C1210"))
    )
    (comp (ref "C36")
      (value "100n/25V")
      (footprint "eagle-import:0603")
      (libsource (lib "eagle-import") (part "C0603"))
    )
    (comp (ref "C37")
      (value "22nF")
      (footprint "eagle-import:0603")
      (libsource (lib "eagle-import") (part "C0603"))
    )
    (comp (ref "C38")
      (value "15nF")
      (footprint "eagle-import:0603")
      (libsource (lib "eagle-import") (part "C0603"))
    )
    (comp (ref "C39")
      (value "1.3nF")
      (footprint "eagle-import:0603")
      (libsource (lib "eagle-import") (part "C0603"))
    )
    (comp (ref "C40")
      (value "22uF/25V")
      (footprint "eagle-import:1210")
      (libsource (lib "eagle-import") (part "C1210"))
    )
    (comp (ref "C41")
      (value "22uF/25V")
      (footprint "eagle-import:1210")
      (libsource (lib "eagle-import") (part "C1210"))
    )
    (comp (ref "C42")
      (value "22uF/6.3V")
      (footprint "eagle-import:0805")
      (libsource (lib "eagle-import") (part "C0805"))
    )
    (comp (ref "C43")
      (value "22uF/6.3V")
      (footprint "eagle-import:0805")
      (libsource (lib "eagle-import") (part "C0805"))
    )
    (comp (ref "C44")
      (value "22uF/6.3V")
      (footprint "eagle-import:0805")
      (libsource (lib "eagle-import") (part "C0805"))
    )
    (comp (ref "C45")
      (value "22uF/6.3V")
      (footprint "eagle-import:0805")
      (libsource (lib "eagle-import") (part "C0805"))
    )
    (comp (ref "C46")
      (value "22uF/6.3V")
      (footprint "eagle-import:0805")
      (libsource (lib "eagle-import") (part "C0805"))
    )
    (comp (ref "C47")
      (value "6.8nF")
      (footprint "eagle-import:0603")
      (libsource (lib "eagle-import") (part "C0603"))
    )
    (comp (ref "C48")
      (value "6.8nF")
      (footprint "eagle-import:0603")
      (libsource (lib "eagle-import") (part "C0603"))
    )
    (comp (ref "C86")
      (value "NC")
      (footprint "eagle-import:CAP_POL_8MM")
      (libsource (lib "eagle-import") (part "C_POL"))
    )
    (comp (ref "C87")
      (value "NC")
      (footprint "eagle-import:CAP_POL_8MM")
      (libsource (lib "eagle-import") (part "C_POL"))
    )
    (comp (ref "C88")
      (value "NC")
      (footprint "eagle-import:CAP_POL_8MM")
      (libsource (lib "eagle-import") (part "C_POL"))
    )
    (comp (ref "IC1")
      (value "ISL6545")
      (footprint "eagle-import:SO-8_BIGPADS")
      (libsource (lib "eagle-import") (part "ISL6545"))
    )
    (comp (ref "IC2")
      (value "ISL6545")
      (footprint "eagle-import:SO-8_BIGPADS")
      (libsource (lib "eagle-import") (part "ISL6545"))
    )
    (comp (ref "IC3")
      (value "ISL6545")
      (footprint "eagle-import:SO-8_BIGPADS")
      (libsource (lib "eagle-import") (part "ISL6545"))
    )
    (comp (ref "IC16")
      (value "AOZ1050PI")
      (footprint "eagle-import:SO-8_EP")
      (libsource (lib "eagle-import") (part "AOZ1050PI"))
    )
    (comp (ref "IC17")
      (value "AP7165-SPG-13")
      (footprint "eagle-import:SO-8_EP")
      (libsource (lib "eagle-import") (part "AP7165-SPG-13"))
    )
    (comp (ref "L1")
      (value "1.4uH")
      (footprint "eagle-import:B82559A0142A013")
      (libsource (lib "eagle-import") (part "B82559A0142A013"))
    )
    (comp (ref "L2")
      (value "1.4uH")
      (footprint "eagle-import:B82559A0142A013")
      (libsource (lib "eagle-import") (part "B82559A0142A013"))
    )
    (comp (ref "L3")
      (value "1.4uH")
      (footprint "eagle-import:B82559A0142A013")
      (libsource (lib "eagle-import") (part "B82559A0142A013"))
    )
    (comp (ref "L4")
      (value "6.8uH")
      (footprint "eagle-import:SRU1048-6R8Y")
      (libsource (lib "eagle-import") (part "SRU1048-6R8Y"))
    )
    (comp (ref "L5")
      (value "30R@100MHz")
      (footprint "eagle-import:0603")
      (libsource (lib "eagle-import") (part "FERRITE0603"))
    )
    (comp (ref "R1")
      (value "3k3")
      (footprint "eagle-import:0603")
      (libsource (lib "eagle-import") (part "R0603"))
    )
    (comp (ref "R2")
      (value "3k3")
      (footprint "eagle-import:0603")
      (libsource (lib "eagle-import") (part "R0603"))
    )
    (comp (ref "R3")
      (value "5k23")
      (footprint "eagle-import:0603")
      (libsource (lib "eagle-import") (part "R0603"))
    )
    (comp (ref "R4")
      (value "52R3")
      (footprint "eagle-import:0603")
      (libsource (lib "eagle-import") (part "R0603"))
    )
    (comp (ref "R5")
      (value "1k5")
      (footprint "eagle-import:0603")
      (libsource (lib "eagle-import") (part "R0603"))
    )
    (comp (ref "R6")
      (value "3k3")
      (footprint "eagle-import:0603")
      (libsource (lib "eagle-import") (part "R0603"))
    )
    (comp (ref "R7")
      (value "3k3")
      (footprint "eagle-import:0603")
      (libsource (lib "eagle-import") (part "R0603"))
    )
    (comp (ref "R8")
      (value "5k23")
      (footprint "eagle-import:0603")
      (libsource (lib "eagle-import") (part "R0603"))
    )
    (comp (ref "R9")
      (value "52R3")
      (footprint "eagle-import:0603")
      (libsource (lib "eagle-import") (part "R0603"))
    )
    (comp (ref "R10")
      (value "1k5")
      (footprint "eagle-import:0603")
      (libsource (lib "eagle-import") (part "R0603"))
    )
    (comp (ref "R11")
      (value "3k3")
      (footprint "eagle-import:0603")
      (libsource (lib "eagle-import") (part "R0603"))
    )
    (comp (ref "R12")
      (value "3k3")
      (footprint "eagle-import:0603")
      (libsource (lib "eagle-import") (part "R0603"))
    )
    (comp (ref "R13")
      (value "5k23")
      (footprint "eagle-import:0603")
      (libsource (lib "eagle-import") (part "R0603"))
    )
    (comp (ref "R14")
      (value "52R3")
      (footprint "eagle-import:0603")
      (libsource (lib "eagle-import") (part "R0603"))
    )
    (comp (ref "R15")
      (value "1k5")
      (footprint "eagle-import:0603")
      (libsource (lib "eagle-import") (part "R0603"))
    )
    (comp (ref "R16")
      (value "31k6")
      (footprint "eagle-import:0603")
      (libsource (lib "eagle-import") (part "R0603"))
    )
    (comp (ref "R17")
      (value "10k")
      (footprint "eagle-import:0603")
      (libsource (lib "eagle-import") (part "R0603"))
    )
    (comp (ref "R18")
      (value "10k")
      (footprint "eagle-import:0603")
      (libsource (lib "eagle-import") (part "R0603"))
    )
    (comp (ref "R33")
      (value "31k6")
      (footprint "eagle-import:0603")
      (libsource (lib "eagle-import") (part "R0603"))
    )
    (comp (ref "R34")
      (value "15k8")
      (footprint "eagle-import:0603")
      (libsource (lib "eagle-import") (part "R0603"))
    )
    (comp (ref "T1")
      (value "AON9673A")
      (footprint "eagle-import:DFN5X6")
      (libsource (lib "eagle-import") (part "AON9673A"))
    )
    (comp (ref "T2")
      (value "AON9673A")
      (footprint "eagle-import:DFN5X6")
      (libsource (lib "eagle-import") (part "AON9673A"))
    )
    (comp (ref "T3")
      (value "AON9673A")
      (footprint "eagle-import:DFN5X6")
      (libsource (lib "eagle-import") (part "AON9673A"))
    )
    (comp (ref "VIA1")
      (value "VIA")
      (footprint "eagle-import:VIA")
      (libsource (lib "eagle-import") (part "VIA"))
    )
    (comp (ref "VIA2")
      (value "VIA")
      (footprint "eagle-import:VIA")
      (libsource (lib "eagle-import") (part "VIA"))
    )
    (comp (ref "VIA3")
      (value "VIA")
      (footprint "eagle-import:VIA")
      (libsource (lib "eagle-import") (part "VIA"))
    )
  )
  (nets
    (net (code "1") (name "1.2V_1") (class "Default")
      (node (ref "C103") (pin "1") (pinfunction "P$1_1") (pintype "passive"))
      (node (ref "C104") (pin "1") (pinfunction "P$1_1") (pintype "passive"))
      (node (ref "C105") (pin "1") (pinfunction "P$1_1") (pintype "passive"))
      (node (ref "C106") (pin "1") (pinfunction "P$1_1") (pintype "passive"))
      (node (ref "C107") (pin "1") (pinfunction "P$1_1") (pintype "passive"))
      (node (ref "C108") (pin "1") (pinfunction "P$1_1") (pintype "passive"))
      (node (ref "C109") (pin "1") (pinfunction "P$1_1") (pintype "passive"))
      (node (ref "C110") (pin "1") (pinfunction "P$1_1") (pintype "passive"))
      (node (ref "C4") (pin "P$1") (pinfunction "+_P$1") (pintype "passive"))
      (node (ref "C5") (pin "1") (pinfunction "P$1_1") (pintype "passive"))
      (node (ref "C6") (pin "1") (pinfunction "P$1_1") (pintype "passive"))
      (node (ref "C64") (pin "1") (pinfunction "P$1_1") (pintype "passive"))
      (node (ref "C65") (pin "1") (pinfunction "P$1_1") (pintype "passive"))
      (node (ref "C66") (pin "1") (pinfunction "P$1_1") (pintype "passive"))
      (node (ref "C67") (pin "1") (pinfunction "P$1_1") (pintype "passive"))
      (node (ref "C68") (pin "1") (pinfunction "P$1_1") (pintype "passive"))
      (node (ref "C69") (pin "1") (pinfunction "P$1_1") (pintype "passive"))
      (node (ref "C7") (pin "1") (pinfunction "P$1_1") (pintype "passive"))
      (node (ref "C70") (pin "1") (pinfunction "P$1_1") (pintype "passive"))
      (node (ref "C71") (pin "1") (pinfunction "P$1_1") (pintype "passive"))
      (node (ref "C78") (pin "1") (pinfunction "P$1_1") (pintype "passive"))
      (node (ref "C79") (pin "1") (pinfunction "P$1_1") (pintype "passive"))
      (node (ref "C80") (pin "1") (pinfunction "P$1_1") (pintype "passive"))
      (node (ref "C81") (pin "1") (pinfunction "P$1_1") (pintype "passive"))
      (node (ref "C82") (pin "1") (pinfunction "P$1_1") (pintype "passive"))
      (node (ref "C83") (pin "1") (pinfunction "P$1_1") (pintype "passive"))
      (node (ref "C84") (pin "1") (pinfunction "P$1_1") (pintype "passive"))
      (node (ref "C85") (pin "1") (pinfunction "P$1_1") (pintype "passive"))
      (node (ref "C86") (pin "P$1") (pinfunction "+_P$1") (pintype "passive"))
      (node (ref "C92") (pin "1") (pinfunction "P$1_1") (pintype "passive"))
      (node (ref "C93") (pin "1") (pinfunction "P$1_1") (pintype "passive"))
      (node (ref "C94") (pin "1") (pinfunction "P$1_1") (pintype "passive"))
      (node (ref "C95") (pin "1") (pinfunction "P$1_1") (pintype "passive"))
      (node (ref "C96") (pin "1") (pinfunction "P$1_1") (pintype "passive"))
      (node (ref "C97") (pin "1") (pinfunction "P$1_1") (pintype "passive"))
      (node (ref "C98") (pin "1") (pinfunction "P$1_1") (pintype "passive"))
      (node (ref "C99") (pin "1") (pinfunction "P$1_1") (pintype "passive"))
      (node (ref "IC4") (pin "11") (pinfunction "DVDD_11") (pintype "power_in"))
      (node (ref "IC4") (pin "12") (pinfunction "DVDD_12") (pintype "power_in"))
      (node (ref "IC4") (pin "13") (pinfunction "DVDD_13") (pintype "power_in"))
      (node (ref "IC4") (pin "14") (pinfunction "DVDD_14") (pintype "power_in"))
      (node (ref "IC4") (pin "15") (pinfunction "DVDD_15") (pintype "power_in"))
      (node (ref "IC4") (pin "16") (pinfunction "DVDD_16") (pintype "power_in"))
      (node (ref "IC4") (pin "19") (pinfunction "DVDD_19") (pintype "power_in"))
      (node (ref "IC4") (pin "21") (pinfunction "DVDD_21") (pintype "power_in"))
      (node (ref "IC4") (pin "22") (pinfunction "DVDD_22") (pintype "power_in"))
      (node (ref "IC4") (pin "25") (pinfunction "DVDD_25") (pintype "power_in"))
      (node (ref "IC4") (pin "26") (pinfunction "DVDD_26") (pintype "power_in"))
      (node (ref "IC4") (pin "27") (pinfunction "DVDD_27") (pintype "power_in"))
      (node (ref "IC4") (pin "28") (pinfunction "DVDD_28") (pintype "power_in"))
      (node (ref "IC4") (pin "3") (pinfunction "DVDD_3") (pintype "power_in"))
      (node (ref "IC4") (pin "31") (pinfunction "DVDD_31") (pintype "power_in"))
      (node (ref "IC4") (pin "33") (pinfunction "DVDD_33") (pintype "power_in"))
      (node (ref "IC4") (pin "34") (pinfunction "DVDD_34") (pintype "power_in"))
      (node (ref "IC4") (pin "39") (pinfunction "DVDD_39") (pintype "power_in"))
      (node (ref "IC4") (pin "4") (pinfunction "DVDD_4") (pintype "power_in"))
      (node (ref "IC4") (pin "40") (pinfunction "DVDD_40") (pintype "power_in"))
      (node (ref "IC4") (pin "41") (pinfunction "DVDD_41") (pintype "power_in"))
      (node (ref "IC4") (pin "43") (pinfunction "DVDD_43") (pintype "power_in"))
      (node (ref "IC4") (pin "46") (pinfunction "DVDD_46") (pintype "power_in"))
      (node (ref "IC4") (pin "47") (pinfunction "DVDD_47") (pintype "power_in"))
      (node (ref "IC4") (pin "48") (pinfunction "DVDD_48") (pintype "power_in"))
      (node (ref "IC4") (pin "6") (pinfunction "DVDD_6") (pintype "power_in"))
      (node (ref "IC5") (pin "11") (pinfunction "DVDD_11") (pintype "power_in"))
      (node (ref "IC5") (pin "12") (pinfunction "DVDD_12") (pintype "power_in"))
      (node (ref "IC5") (pin "13") (pinfunction "DVDD_13") (pintype "power_in"))
      (node (ref "IC5") (pin "14") (pinfunction "DVDD_14") (pintype "power_in"))
      (node (ref "IC5") (pin "15") (pinfunction "DVDD_15") (pintype "power_in"))
      (node (ref "IC5") (pin "16") (pinfunction "DVDD_16") (pintype "power_in"))
      (node (ref "IC5") (pin "19") (pinfunction "DVDD_19") (pintype "power_in"))
      (node (ref "IC5") (pin "21") (pinfunction "DVDD_21") (pintype "power_in"))
      (node (ref "IC5") (pin "22") (pinfunction "DVDD_22") (pintype "power_in"))
      (node (ref "IC5") (pin "25") (pinfunction "DVDD_25") (pintype "power_in"))
      (node (ref "IC5") (pin "26") (pinfunction "DVDD_26") (pintype "power_in"))
      (node (ref "IC5") (pin "27") (pinfunction "DVDD_27") (pintype "power_in"))
      (node (ref "IC5") (pin "28") (pinfunction "DVDD_28") (pintype "power_in"))
      (node (ref "IC5") (pin "3") (pinfunction "DVDD_3") (pintype "power_in"))
      (node (ref "IC5") (pin "31") (pinfunction "DVDD_31") (pintype "power_in"))
      (node (ref "IC5") (pin "33") (pinfunction "DVDD_33") (pintype "power_in"))
      (node (ref "IC5") (pin "34") (pinfunction "DVDD_34") (pintype "power_in"))
      (node (ref "IC5") (pin "39") (pinfunction "DVDD_39") (pintype "power_in"))
      (node (ref "IC5") (pin "4") (pinfunction "DVDD_4") (pintype "power_in"))
      (node (ref "IC5") (pin "40") (pinfunction "DVDD_40") (pintype "power_in"))
      (node (ref "IC5") (pin "41") (pinfunction "DVDD_41") (pintype "power_in"))
      (node (ref "IC5") (pin "43") (pinfunction "DVDD_43") (pintype "power_in"))
      (node (ref "IC5") (pin "46") (pinfunction "DVDD_46") (pintype "power_in"))
      (node (ref "IC5") (pin "47") (pinfunction "DVDD_47") (pintype "power_in"))
      (node (ref "IC5") (pin "48") (pinfunction "DVDD_48") (pintype "power_in"))
      (node (ref "IC5") (pin "6") (pinfunction "DVDD_6") (pintype "power_in"))
      (node (ref "IC6") (pin "11") (pinfunction "DVDD_11") (pintype "power_in"))
      (node (ref "IC6") (pin "12") (pinfunction "DVDD_12") (pintype "power_in"))
      (node (ref "IC6") (pin "13") (pinfunction "DVDD_13") (pintype "power_in"))
      (node (ref "IC6") (pin "14") (pinfunction "DVDD_14") (pintype "power_in"))
      (node (ref "IC6") (pin "15") (pinfunction "DVDD_15") (pintype "power_in"))
      (node (ref "IC6") (pin "16") (pinfunction "DVDD_16") (pintype "power_in"))
      (node (ref "IC6") (pin "19") (pinfunction "DVDD_19") (pintype "power_in"))
      (node (ref "IC6") (pin "21") (pinfunction "DVDD_21") (pintype "power_in"))
      (node (ref "IC6") (pin "22") (pinfunction "DVDD_22") (pintype "power_in"))
      (node (ref "IC6") (pin "25") (pinfunction "DVDD_25") (pintype "power_in"))
      (node (ref "IC6") (pin "26") (pinfunction "DVDD_26") (pintype "power_in"))
      (node (ref "IC6") (pin "27") (pinfunction "DVDD_27") (pintype "power_in"))
      (node (ref "IC6") (pin "28") (pinfunction "DVDD_28") (pintype "power_in"))
      (node (ref "IC6") (pin "3") (pinfunction "DVDD_3") (pintype "power_in"))
      (node (ref "IC6") (pin "31") (pinfunction "DVDD_31") (pintype "power_in"))
      (node (ref "IC6") (pin "33") (pinfunction "DVDD_33") (pintype "power_in"))
      (node (ref "IC6") (pin "34") (pinfunction "DVDD_34") (pintype "power_in"))
      (node (ref "IC6") (pin "39") (pinfunction "DVDD_39") (pintype "power_in"))
      (node (ref "IC6") (pin "4") (pinfunction "DVDD_4") (pintype "power_in"))
      (node (ref "IC6") (pin "40") (pinfunction "DVDD_40") (pintype "power_in"))
      (node (ref "IC6") (pin "41") (pinfunction "DVDD_41") (pintype "power_in"))
      (node (ref "IC6") (pin "43") (pinfunction "DVDD_43") (pintype "power_in"))
      (node (ref "IC6") (pin "46") (pinfunction "DVDD_46") (pintype "power_in"))
      (node (ref "IC6") (pin "47") (pinfunction "DVDD_47") (pintype "power_in"))
      (node (ref "IC6") (pin "48") (pinfunction "DVDD_48") (pintype "power_in"))
      (node (ref "IC6") (pin "6") (pinfunction "DVDD_6") (pintype "power_in"))
      (node (ref "IC7") (pin "11") (pinfunction "DVDD_11") (pintype "power_in"))
      (node (ref "IC7") (pin "12") (pinfunction "DVDD_12") (pintype "power_in"))
      (node (ref "IC7") (pin "13") (pinfunction "DVDD_13") (pintype "power_in"))
      (node (ref "IC7") (pin "14") (pinfunction "DVDD_14") (pintype "power_in"))
      (node (ref "IC7") (pin "15") (pinfunction "DVDD_15") (pintype "power_in"))
      (node (ref "IC7") (pin "16") (pinfunction "DVDD_16") (pintype "power_in"))
      (node (ref "IC7") (pin "19") (pinfunction "DVDD_19") (pintype "power_in"))
      (node (ref "IC7") (pin "21") (pinfunction "DVDD_21") (pintype "power_in"))
      (node (ref "IC7") (pin "22") (pinfunction "DVDD_22") (pintype "power_in"))
      (node (ref "IC7") (pin "25") (pinfunction "DVDD_25") (pintype "power_in"))
      (node (ref "IC7") (pin "26") (pinfunction "DVDD_26") (pintype "power_in"))
      (node (ref "IC7") (pin "27") (pinfunction "DVDD_27") (pintype "power_in"))
      (node (ref "IC7") (pin "28") (pinfunction "DVDD_28") (pintype "power_in"))
      (node (ref "IC7") (pin "3") (pinfunction "DVDD_3") (pintype "power_in"))
      (node (ref "IC7") (pin "31") (pinfunction "DVDD_31") (pintype "power_in"))
      (node (ref "IC7") (pin "33") (pinfunction "DVDD_33") (pintype "power_in"))
      (node (ref "IC7") (pin "34") (pinfunction "DVDD_34") (pintype "power_in"))
      (node (ref "IC7") (pin "39") (pinfunction "DVDD_39") (pintype "power_in"))
      (node (ref "IC7") (pin "4") (pinfunction "DVDD_4") (pintype "power_in"))
      (node (ref "IC7") (pin "40") (pinfunction "DVDD_40") (pintype "power_in"))
      (node (ref "IC7") (pin "41") (pinfunction "DVDD_41") (pintype "power_in"))
      (node (ref "IC7") (pin "43") (pinfunction "DVDD_43") (pintype "power_in"))
      (node (ref "IC7") (pin "46") (pinfunction "DVDD_46") (pintype "power_in"))
      (node (ref "IC7") (pin "47") (pinfunction "DVDD_47") (pintype "power_in"))
      (node (ref "IC7") (pin "48") (pinfunction "DVDD_48") (pintype "power_in"))
      (node (ref "IC7") (pin "6") (pinfunction "DVDD_6") (pintype "power_in"))
      (node (ref "L1") (pin "2") (pinfunction "P$2_2") (pintype "passive"))
      (node (ref "R1") (pin "2") (pinfunction "2_2") (pintype "passive"))
      (node (ref "R4") (pin "2") (pinfunction "2_2") (pintype "passive"))
      (node (ref "R41") (pin "2") (pinfunction "2_2") (pintype "passive"))
    )
    (net (code "2") (name "1.2V_2") (class "Default")
      (node (ref "C114") (pin "1") (pinfunction "P$1_1") (pintype "passive"))
      (node (ref "C115") (pin "1") (pinfunction "P$1_1") (pintype "passive"))
      (node (ref "C116") (pin "1") (pinfunction "P$1_1") (pintype "passive"))
      (node (ref "C117") (pin "1") (pinfunction "P$1_1") (pintype "passive"))
      (node (ref "C118") (pin "1") (pinfunction "P$1_1") (pintype "passive"))
      (node (ref "C119") (pin "1") (pinfunction "P$1_1") (pintype "passive"))
      (node (ref "C120") (pin "1") (pinfunction "P$1_1") (pintype "passive"))
      (node (ref "C121") (pin "1") (pinfunction "P$1_1") (pintype "passive"))
      (node (ref "C125") (pin "1") (pinfunction "P$1_1") (pintype "passive"))
      (node (ref "C126") (pin "1") (pinfunction "P$1_1") (pintype "passive"))
      (node (ref "C127") (pin "1") (pinfunction "P$1_1") (pintype "passive"))
      (node (ref "C128") (pin "1") (pinfunction "P$1_1") (pintype "passive"))
      (node (ref "C129") (pin "1") (pinfunction "P$1_1") (pintype "passive"))
      (node (ref "C130") (pin "1") (pinfunction "P$1_1") (pintype "passive"))
      (node (ref "C131") (pin "1") (pinfunction "P$1_1") (pintype "passive"))
      (node (ref "C132") (pin "1") (pinfunction "P$1_1") (pintype "passive"))
      (node (ref "C136") (pin "1") (pinfunction "P$1_1") (pintype "passive"))
      (node (ref "C137") (pin "1") (pinfunction "P$1_1") (pintype "passive"))
      (node (ref "C138") (pin "1") (pinfunction "P$1_1") (pintype "passive"))
      (node (ref "C139") (pin "1") (pinfunction "P$1_1") (pintype "passive"))
      (node (ref "C140") (pin "1") (pinfunction "P$1_1") (pintype "passive"))
      (node (ref "C141") (pin "1") (pinfunction "P$1_1") (pintype "passive"))
      (node (ref "C142") (pin "1") (pinfunction "P$1_1") (pintype "passive"))
      (node (ref "C143") (pin "1") (pinfunction "P$1_1") (pintype "passive"))
      (node (ref "C147") (pin "1") (pinfunction "P$1_1") (pintype "passive"))
      (node (ref "C148") (pin "1") (pinfunction "P$1_1") (pintype "passive"))
      (node (ref "C149") (pin "1") (pinfunction "P$1_1") (pintype "passive"))
      (node (ref "C150") (pin "1") (pinfunction "P$1_1") (pintype "passive"))
      (node (ref "C151") (pin "1") (pinfunction "P$1_1") (pintype "passive"))
      (node (ref "C152") (pin "1") (pinfunction "P$1_1") (pintype "passive"))
      (node (ref "C153") (pin "1") (pinfunction "P$1_1") (pintype "passive"))
      (node (ref "C154") (pin "1") (pinfunction "P$1_1") (pintype "passive"))
      (node (ref "C17") (pin "P$1") (pinfunction "+_P$1") (pintype "passive"))
      (node (ref "C18") (pin "1") (pinfunction "P$1_1") (pintype "passive"))
      (node (ref "C19") (pin "1") (pinfunction "P$1_1") (pintype "passive"))
      (node (ref "C20") (pin "1") (pinfunction "P$1_1") (pintype "passive"))
      (node (ref "C87") (pin "P$1") (pinfunction "+_P$1") (pintype "passive"))
      (node (ref "IC10") (pin "11") (pinfunction "DVDD_11") (pintype "power_in"))
      (node (ref "IC10") (pin "12") (pinfunction "DVDD_12") (pintype "power_in"))
      (node (ref "IC10") (pin "13") (pinfunction "DVDD_13") (pintype "power_in"))
      (node (ref "IC10") (pin "14") (pinfunction "DVDD_14") (pintype "power_in"))
      (node (ref "IC10") (pin "15") (pinfunction "DVDD_15") (pintype "power_in"))
      (node (ref "IC10") (pin "16") (pinfunction "DVDD_16") (pintype "power_in"))
      (node (ref "IC10") (pin "19") (pinfunction "DVDD_19") (pintype "power_in"))
      (node (ref "IC10") (pin "21") (pinfunction "DVDD_21") (pintype "power_in"))
      (node (ref "IC10") (pin "22") (pinfunction "DVDD_22") (pintype "power_in"))
      (node (ref "IC10") (pin "25") (pinfunction "DVDD_25") (pintype "power_in"))
      (node (ref "IC10") (pin "26") (pinfunction "DVDD_26") (pintype "power_in"))
      (node (ref "IC10") (pin "27") (pinfunction "DVDD_27") (pintype "power_in"))
      (node (ref "IC10") (pin "28") (pinfunction "DVDD_28") (pintype "power_in"))
      (node (ref "IC10") (pin "3") (pinfunction "DVDD_3") (pintype "power_in"))
      (node (ref "IC10") (pin "31") (pinfunction "DVDD_31") (pintype "power_in"))
      (node (ref "IC10") (pin "33") (pinfunction "DVDD_33") (pintype "power_in"))
      (node (ref "IC10") (pin "34") (pinfunction "DVDD_34") (pintype "power_in"))
      (node (ref "IC10") (pin "39") (pinfunction "DVDD_39") (pintype "power_in"))
      (node (ref "IC10") (pin "4") (pinfunction "DVDD_4") (pintype "power_in"))
      (node (ref "IC10") (pin "40") (pinfunction "DVDD_40") (pintype "power_in"))
      (node (ref "IC10") (pin "41") (pinfunction "DVDD_41") (pintype "power_in"))
      (node (ref "IC10") (pin "43") (pinfunction "DVDD_43") (pintype "power_in"))
      (node (ref "IC10") (pin "46") (pinfunction "DVDD_46") (pintype "power_in"))
      (node (ref "IC10") (pin "47") (pinfunction "DVDD_47") (pintype "power_in"))
      (node (ref "IC10") (pin "48") (pinfunction "DVDD_48") (pintype "power_in"))
      (node (ref "IC10") (pin "6") (pinfunction "DVDD_6") (pintype "power_in"))
      (node (ref "IC11") (pin "11") (pinfunction "DVDD_11") (pintype "power_in"))
      (node (ref "IC11") (pin "12") (pinfunction "DVDD_12") (pintype "power_in"))
      (node (ref "IC11") (pin "13") (pinfunction "DVDD_13") (pintype "power_in"))
      (node (ref "IC11") (pin "14") (pinfunction "DVDD_14") (pintype "power_in"))
      (node (ref "IC11") (pin "15") (pinfunction "DVDD_15") (pintype "power_in"))
      (node (ref "IC11") (pin "16") (pinfunction "DVDD_16") (pintype "power_in"))
      (node (ref "IC11") (pin "19") (pinfunction "DVDD_19") (pintype "power_in"))
      (node (ref "IC11") (pin "21") (pinfunction "DVDD_21") (pintype "power_in"))
      (node (ref "IC11") (pin "22") (pinfunction "DVDD_22") (pintype "power_in"))
      (node (ref "IC11") (pin "25") (pinfunction "DVDD_25") (pintype "power_in"))
      (node (ref "IC11") (pin "26") (pinfunction "DVDD_26") (pintype "power_in"))
      (node (ref "IC11") (pin "27") (pinfunction "DVDD_27") (pintype "power_in"))
      (node (ref "IC11") (pin "28") (pinfunction "DVDD_28") (pintype "power_in"))
      (node (ref "IC11") (pin "3") (pinfunction "DVDD_3") (pintype "power_in"))
      (node (ref "IC11") (pin "31") (pinfunction "DVDD_31") (pintype "power_in"))
      (node (ref "IC11") (pin "33") (pinfunction "DVDD_33") (pintype "power_in"))
      (node (ref "IC11") (pin "34") (pinfunction "DVDD_34") (pintype "power_in"))
      (node (ref "IC11") (pin "39") (pinfunction "DVDD_39") (pintype "power_in"))
      (node (ref "IC11") (pin "4") (pinfunction "DVDD_4") (pintype "power_in"))
      (node (ref "IC11") (pin "40") (pinfunction "DVDD_40") (pintype "power_in"))
      (node (ref "IC11") (pin "41") (pinfunction "DVDD_41") (pintype "power_in"))
      (node (ref "IC11") (pin "43") (pinfunction "DVDD_43") (pintype "power_in"))
      (node (ref "IC11") (pin "46") (pinfunction "DVDD_46") (pintype "power_in"))
      (node (ref "IC11") (pin "47") (pinfunction "DVDD_47") (pintype "power_in"))
      (node (ref "IC11") (pin "48") (pinfunction "DVDD_48") (pintype "power_in"))
      (node (ref "IC11") (pin "6") (pinfunction "DVDD_6") (pintype "power_in"))
      (node (ref "IC8") (pin "11") (pinfunction "DVDD_11") (pintype "power_in"))
      (node (ref "IC8") (pin "12") (pinfunction "DVDD_12") (pintype "power_in"))
      (node (ref "IC8") (pin "13") (pinfunction "DVDD_13") (pintype "power_in"))
      (node (ref "IC8") (pin "14") (pinfunction "DVDD_14") (pintype "power_in"))
      (node (ref "IC8") (pin "15") (pinfunction "DVDD_15") (pintype "power_in"))
      (node (ref "IC8") (pin "16") (pinfunction "DVDD_16") (pintype "power_in"))
      (node (ref "IC8") (pin "19") (pinfunction "DVDD_19") (pintype "power_in"))
      (node (ref "IC8") (pin "21") (pinfunction "DVDD_21") (pintype "power_in"))
      (node (ref "IC8") (pin "22") (pinfunction "DVDD_22") (pintype "power_in"))
      (node (ref "IC8") (pin "25") (pinfunction "DVDD_25") (pintype "power_in"))
      (node (ref "IC8") (pin "26") (pinfunction "DVDD_26") (pintype "power_in"))
      (node (ref "IC8") (pin "27") (pinfunction "DVDD_27") (pintype "power_in"))
      (node (ref "IC8") (pin "28") (pinfunction "DVDD_28") (pintype "power_in"))
      (node (ref "IC8") (pin "3") (pinfunction "DVDD_3") (pintype "power_in"))
      (node (ref "IC8") (pin "31") (pinfunction "DVDD_31") (pintype "power_in"))
      (node (ref "IC8") (pin "33") (pinfunction "DVDD_33") (pintype "power_in"))
      (node (ref "IC8") (pin "34") (pinfunction "DVDD_34") (pintype "power_in"))
      (node (ref "IC8") (pin "39") (pinfunction "DVDD_39") (pintype "power_in"))
      (node (ref "IC8") (pin "4") (pinfunction "DVDD_4") (pintype "power_in"))
      (node (ref "IC8") (pin "40") (pinfunction "DVDD_40") (pintype "power_in"))
      (node (ref "IC8") (pin "41") (pinfunction "DVDD_41") (pintype "power_in"))
      (node (ref "IC8") (pin "43") (pinfunction "DVDD_43") (pintype "power_in"))
      (node (ref "IC8") (pin "46") (pinfunction "DVDD_46") (pintype "power_in"))
      (node (ref "IC8") (pin "47") (pinfunction "DVDD_47") (pintype "power_in"))
      (node (ref "IC8") (pin "48") (pinfunction "DVDD_48") (pintype "power_in"))
      (node (ref "IC8") (pin "6") (pinfunction "DVDD_6") (pintype "power_in"))
      (node (ref "IC9") (pin "11") (pinfunction "DVDD_11") (pintype "power_in"))
      (node (ref "IC9") (pin "12") (pinfunction "DVDD_12") (pintype "power_in"))
      (node (ref "IC9") (pin "13") (pinfunction "DVDD_13") (pintype "power_in"))
      (node (ref "IC9") (pin "14") (pinfunction "DVDD_14") (pintype "power_in"))
      (node (ref "IC9") (pin "15") (pinfunction "DVDD_15") (pintype "power_in"))
      (node (ref "IC9") (pin "16") (pinfunction "DVDD_16") (pintype "power_in"))
      (node (ref "IC9") (pin "19") (pinfunction "DVDD_19") (pintype "power_in"))
      (node (ref "IC9") (pin "21") (pinfunction "DVDD_21") (pintype "power_in"))
      (node (ref "IC9") (pin "22") (pinfunction "DVDD_22") (pintype "power_in"))
      (node (ref "IC9") (pin "25") (pinfunction "DVDD_25") (pintype "power_in"))
      (node (ref "IC9") (pin "26") (pinfunction "DVDD_26") (pintype "power_in"))
      (node (ref "IC9") (pin "27") (pinfunction "DVDD_27") (pintype "power_in"))
      (node (ref "IC9") (pin "28") (pinfunction "DVDD_28") (pintype "power_in"))
      (node (ref "IC9") (pin "3") (pinfunction "DVDD_3") (pintype "power_in"))
      (node (ref "IC9") (pin "31") (pinfunction "DVDD_31") (pintype "power_in"))
      (node (ref "IC9") (pin "33") (pinfunction "DVDD_33") (pintype "power_in"))
      (node (ref "IC9") (pin "34") (pinfunction "DVDD_34") (pintype "power_in"))
      (node (ref "IC9") (pin "39") (pinfunction "DVDD_39") (pintype "power_in"))
      (node (ref "IC9") (pin "4") (pinfunction "DVDD_4") (pintype "power_in"))
      (node (ref "IC9") (pin "40") (pinfunction "DVDD_40") (pintype "power_in"))
      (node (ref "IC9") (pin "41") (pinfunction "DVDD_41") (pintype "power_in"))
      (node (ref "IC9") (pin "43") (pinfunction "DVDD_43") (pintype "power_in"))
      (node (ref "IC9") (pin "46") (pinfunction "DVDD_46") (pintype "power_in"))
      (node (ref "IC9") (pin "47") (pinfunction "DVDD_47") (pintype "power_in"))
      (node (ref "IC9") (pin "48") (pinfunction "DVDD_48") (pintype "power_in"))
      (node (ref "IC9") (pin "6") (pinfunction "DVDD_6") (pintype "power_in"))
      (node (ref "L2") (pin "2") (pinfunction "P$2_2") (pintype "passive"))
      (node (ref "R43") (pin "2") (pinfunction "2_2") (pintype "passive"))
      (node (ref "R6") (pin "2") (pinfunction "2_2") (pintype "passive"))
      (node (ref "R9") (pin "2") (pinfunction "2_2") (pintype "passive"))
    )
    (net (code "3") (name "1.2V_3") (class "Default")
      (node (ref "C158") (pin "1") (pinfunction "P$1_1") (pintype "passive"))
      (node (ref "C159") (pin "1") (pinfunction "P$1_1") (pintype "passive"))
      (node (ref "C160") (pin "1") (pinfunction "P$1_1") (pintype "passive"))
      (node (ref "C161") (pin "1") (pinfunction "P$1_1") (pintype "passive"))
      (node (ref "C162") (pin "1") (pinfunction "P$1_1") (pintype "passive"))
      (node (ref "C163") (pin "1") (pinfunction "P$1_1") (pintype "passive"))
      (node (ref "C164") (pin "1") (pinfunction "P$1_1") (pintype "passive"))
      (node (ref "C165") (pin "1") (pinfunction "P$1_1") (pintype "passive"))
      (node (ref "C169") (pin "1") (pinfunction "P$1_1") (pintype "passive"))
      (node (ref "C170") (pin "1") (pinfunction "P$1_1") (pintype "passive"))
      (node (ref "C171") (pin "1") (pinfunction "P$1_1") (pintype "passive"))
      (node (ref "C172") (pin "1") (pinfunction "P$1_1") (pintype "passive"))
      (node (ref "C173") (pin "1") (pinfunction "P$1_1") (pintype "passive"))
      (node (ref "C174") (pin "1") (pinfunction "P$1_1") (pintype "passive"))
      (node (ref "C175") (pin "1") (pinfunction "P$1_1") (pintype "passive"))
      (node (ref "C176") (pin "1") (pinfunction "P$1_1") (pintype "passive"))
      (node (ref "C180") (pin "1") (pinfunction "P$1_1") (pintype "passive"))
      (node (ref "C181") (pin "1") (pinfunction "P$1_1") (pintype "passive"))
      (node (ref "C182") (pin "1") (pinfunction "P$1_1") (pintype "passive"))
      (node (ref "C183") (pin "1") (pinfunction "P$1_1") (pintype "passive"))
      (node (ref "C184") (pin "1") (pinfunction "P$1_1") (pintype "passive"))
      (node (ref "C185") (pin "1") (pinfunction "P$1_1") (pintype "passive"))
      (node (ref "C186") (pin "1") (pinfunction "P$1_1") (pintype "passive"))
      (node (ref "C187") (pin "1") (pinfunction "P$1_1") (pintype "passive"))
      (node (ref "C191") (pin "1") (pinfunction "P$1_1") (pintype "passive"))
      (node (ref "C192") (pin "1") (pinfunction "P$1_1") (pintype "passive"))
      (node (ref "C193") (pin "1") (pinfunction "P$1_1") (pintype "passive"))
      (node (ref "C194") (pin "1") (pinfunction "P$1_1") (pintype "passive"))
      (node (ref "C195") (pin "1") (pinfunction "P$1_1") (pintype "passive"))
      (node (ref "C196") (pin "1") (pinfunction "P$1_1") (pintype "passive"))
      (node (ref "C197") (pin "1") (pinfunction "P$1_1") (pintype "passive"))
      (node (ref "C198") (pin "1") (pinfunction "P$1_1") (pintype "passive"))
      (node (ref "C30") (pin "P$1") (pinfunction "+_P$1") (pintype "passive"))
      (node (ref "C31") (pin "1") (pinfunction "P$1_1") (pintype "passive"))
      (node (ref "C32") (pin "1") (pinfunction "P$1_1") (pintype "passive"))
      (node (ref "C33") (pin "1") (pinfunction "P$1_1") (pintype "passive"))
      (node (ref "C88") (pin "P$1") (pinfunction "+_P$1") (pintype "passive"))
      (node (ref "IC12") (pin "11") (pinfunction "DVDD_11") (pintype "power_in"))
      (node (ref "IC12") (pin "12") (pinfunction "DVDD_12") (pintype "power_in"))
      (node (ref "IC12") (pin "13") (pinfunction "DVDD_13") (pintype "power_in"))
      (node (ref "IC12") (pin "14") (pinfunction "DVDD_14") (pintype "power_in"))
      (node (ref "IC12") (pin "15") (pinfunction "DVDD_15") (pintype "power_in"))
      (node (ref "IC12") (pin "16") (pinfunction "DVDD_16") (pintype "power_in"))
      (node (ref "IC12") (pin "19") (pinfunction "DVDD_19") (pintype "power_in"))
      (node (ref "IC12") (pin "21") (pinfunction "DVDD_21") (pintype "power_in"))
      (node (ref "IC12") (pin "22") (pinfunction "DVDD_22") (pintype "power_in"))
      (node (ref "IC12") (pin "25") (pinfunction "DVDD_25") (pintype "power_in"))
      (node (ref "IC12") (pin "26") (pinfunction "DVDD_26") (pintype "power_in"))
      (node (ref "IC12") (pin "27") (pinfunction "DVDD_27") (pintype "power_in"))
      (node (ref "IC12") (pin "28") (pinfunction "DVDD_28") (pintype "power_in"))
      (node (ref "IC12") (pin "3") (pinfunction "DVDD_3") (pintype "power_in"))
      (node (ref "IC12") (pin "31") (pinfunction "DVDD_31") (pintype "power_in"))
      (node (ref "IC12") (pin "33") (pinfunction "DVDD_33") (pintype "power_in"))
      (node (ref "IC12") (pin "34") (pinfunction "DVDD_34") (pintype "power_in"))
      (node (ref "IC12") (pin "39") (pinfunction "DVDD_39") (pintype "power_in"))
      (node (ref "IC12") (pin "4") (pinfunction "DVDD_4") (pintype "power_in"))
      (node (ref "IC12") (pin "40") (pinfunction "DVDD_40") (pintype "power_in"))
      (node (ref "IC12") (pin "41") (pinfunction "DVDD_41") (pintype "power_in"))
      (node (ref "IC12") (pin "43") (pinfunction "DVDD_43") (pintype "power_in"))
      (node (ref "IC12") (pin "46") (pinfunction "DVDD_46") (pintype "power_in"))
      (node (ref "IC12") (pin "47") (pinfunction "DVDD_47") (pintype "power_in"))
      (node (ref "IC12") (pin "48") (pinfunction "DVDD_48") (pintype "power_in"))
      (node (ref "IC12") (pin "6") (pinfunction "DVDD_6") (pintype "power_in"))
      (node (ref "IC13") (pin "11") (pinfunction "DVDD_11") (pintype "power_in"))
      (node (ref "IC13") (pin "12") (pinfunction "DVDD_12") (pintype "power_in"))
      (node (ref "IC13") (pin "13") (pinfunction "DVDD_13") (pintype "power_in"))
      (node (ref "IC13") (pin "14") (pinfunction "DVDD_14") (pintype "power_in"))
      (node (ref "IC13") (pin "15") (pinfunction "DVDD_15") (pintype "power_in"))
      (node (ref "IC13") (pin "16") (pinfunction "DVDD_16") (pintype "power_in"))
      (node (ref "IC13") (pin "19") (pinfunction "DVDD_19") (pintype "power_in"))
      (node (ref "IC13") (pin "21") (pinfunction "DVDD_21") (pintype "power_in"))
      (node (ref "IC13") (pin "22") (pinfunction "DVDD_22") (pintype "power_in"))
      (node (ref "IC13") (pin "25") (pinfunction "DVDD_25") (pintype "power_in"))
      (node (ref "IC13") (pin "26") (pinfunction "DVDD_26") (pintype "power_in"))
      (node (ref "IC13") (pin "27") (pinfunction "DVDD_27") (pintype "power_in"))
      (node (ref "IC13") (pin "28") (pinfunction "DVDD_28") (pintype "power_in"))
      (node (ref "IC13") (pin "3") (pinfunction "DVDD_3") (pintype "power_in"))
      (node (ref "IC13") (pin "31") (pinfunction "DVDD_31") (pintype "power_in"))
      (node (ref "IC13") (pin "33") (pinfunction "DVDD_33") (pintype "power_in"))
      (node (ref "IC13") (pin "34") (pinfunction "DVDD_34") (pintype "power_in"))
      (node (ref "IC13") (pin "39") (pinfunction "DVDD_39") (pintype "power_in"))
      (node (ref "IC13") (pin "4") (pinfunction "DVDD_4") (pintype "power_in"))
      (node (ref "IC13") (pin "40") (pinfunction "DVDD_40") (pintype "power_in"))
      (node (ref "IC13") (pin "41") (pinfunction "DVDD_41") (pintype "power_in"))
      (node (ref "IC13") (pin "43") (pinfunction "DVDD_43") (pintype "power_in"))
      (node (ref "IC13") (pin "46") (pinfunction "DVDD_46") (pintype "power_in"))
      (node (ref "IC13") (pin "47") (pinfunction "DVDD_47") (pintype "power_in"))
      (node (ref "IC13") (pin "48") (pinfunction "DVDD_48") (pintype "power_in"))
      (node (ref "IC13") (pin "6") (pinfunction "DVDD_6") (pintype "power_in"))
      (node (ref "IC14") (pin "11") (pinfunction "DVDD_11") (pintype "power_in"))
      (node (ref "IC14") (pin "12") (pinfunction "DVDD_12") (pintype "power_in"))
      (node (ref "IC14") (pin "13") (pinfunction "DVDD_13") (pintype "power_in"))
      (node (ref "IC14") (pin "14") (pinfunction "DVDD_14") (pintype "power_in"))
      (node (ref "IC14") (pin "15") (pinfunction "DVDD_15") (pintype "power_in"))
      (node (ref "IC14") (pin "16") (pinfunction "DVDD_16") (pintype "power_in"))
      (node (ref "IC14") (pin "19") (pinfunction "DVDD_19") (pintype "power_in"))
      (node (ref "IC14") (pin "21") (pinfunction "DVDD_21") (pintype "power_in"))
      (node (ref "IC14") (pin "22") (pinfunction "DVDD_22") (pintype "power_in"))
      (node (ref "IC14") (pin "25") (pinfunction "DVDD_25") (pintype "power_in"))
      (node (ref "IC14") (pin "26") (pinfunction "DVDD_26") (pintype "power_in"))
      (node (ref "IC14") (pin "27") (pinfunction "DVDD_27") (pintype "power_in"))
      (node (ref "IC14") (pin "28") (pinfunction "DVDD_28") (pintype "power_in"))
      (node (ref "IC14") (pin "3") (pinfunction "DVDD_3") (pintype "power_in"))
      (node (ref "IC14") (pin "31") (pinfunction "DVDD_31") (pintype "power_in"))
      (node (ref "IC14") (pin "33") (pinfunction "DVDD_33") (pintype "power_in"))
      (node (ref "IC14") (pin "34") (pinfunction "DVDD_34") (pintype "power_in"))
      (node (ref "IC14") (pin "39") (pinfunction "DVDD_39") (pintype "power_in"))
      (node (ref "IC14") (pin "4") (pinfunction "DVDD_4") (pintype "power_in"))
      (node (ref "IC14") (pin "40") (pinfunction "DVDD_40") (pintype "power_in"))
      (node (ref "IC14") (pin "41") (pinfunction "DVDD_41") (pintype "power_in"))
      (node (ref "IC14") (pin "43") (pinfunction "DVDD_43") (pintype "power_in"))
      (node (ref "IC14") (pin "46") (pinfunction "DVDD_46") (pintype "power_in"))
      (node (ref "IC14") (pin "47") (pinfunction "DVDD_47") (pintype "power_in"))
      (node (ref "IC14") (pin "48") (pinfunction "DVDD_48") (pintype "power_in"))
      (node (ref "IC14") (pin "6") (pinfunction "DVDD_6") (pintype "power_in"))
      (node (ref "IC15") (pin "11") (pinfunction "DVDD_11") (pintype "power_in"))
      (node (ref "IC15") (pin "12") (pinfunction "DVDD_12") (pintype "power_in"))
      (node (ref "IC15") (pin "13") (pinfunction "DVDD_13") (pintype "power_in"))
      (node (ref "IC15") (pin "14") (pinfunction "DVDD_14") (pintype "power_in"))
      (node (ref "IC15") (pin "15") (pinfunction "DVDD_15") (pintype "power_in"))
      (node (ref "IC15") (pin "16") (pinfunction "DVDD_16") (pintype "power_in"))
      (node (ref "IC15") (pin "19") (pinfunction "DVDD_19") (pintype "power_in"))
      (node (ref "IC15") (pin "21") (pinfunction "DVDD_21") (pintype "power_in"))
      (node (ref "IC15") (pin "22") (pinfunction "DVDD_22") (pintype "power_in"))
      (node (ref "IC15") (pin "25") (pinfunction "DVDD_25") (pintype "power_in"))
      (node (ref "IC15") (pin "26") (pinfunction "DVDD_26") (pintype "power_in"))
      (node (ref "IC15") (pin "27") (pinfunction "DVDD_27") (pintype "power_in"))
      (node (ref "IC15") (pin "28") (pinfunction "DVDD_28") (pintype "power_in"))
      (node (ref "IC15") (pin "3") (pinfunction "DVDD_3") (pintype "power_in"))
      (node (ref "IC15") (pin "31") (pinfunction "DVDD_31") (pintype "power_in"))
      (node (ref "IC15") (pin "33") (pinfunction "DVDD_33") (pintype "power_in"))
      (node (ref "IC15") (pin "34") (pinfunction "DVDD_34") (pintype "power_in"))
      (node (ref "IC15") (pin "39") (pinfunction "DVDD_39") (pintype "power_in"))
      (node (ref "IC15") (pin "4") (pinfunction "DVDD_4") (pintype "power_in"))
      (node (ref "IC15") (pin "40") (pinfunction "DVDD_40") (pintype "power_in"))
      (node (ref "IC15") (pin "41") (pinfunction "DVDD_41") (pintype "power_in"))
      (node (ref "IC15") (pin "43") (pinfunction "DVDD_43") (pintype "power_in"))
      (node (ref "IC15") (pin "46") (pinfunction "DVDD_46") (pintype "power_in"))
      (node (ref "IC15") (pin "47") (pinfunction "DVDD_47") (pintype "power_in"))
      (node (ref "IC15") (pin "48") (pinfunction "DVDD_48") (pintype "power_in"))
      (node (ref "IC15") (pin "6") (pinfunction "DVDD_6") (pintype "power_in"))
      (node (ref "L3") (pin "2") (pinfunction "P$2_2") (pintype "passive"))
      (node (ref "R11") (pin "2") (pinfunction "2_2") (pintype "passive"))
      (node (ref "R14") (pin "2") (pinfunction "2_2") (pintype "passive"))
      (node (ref "R45") (pin "2") (pinfunction "2_2") (pintype "passive"))
    )
    (net (code "4") (name "1.2V_PLL") (class "Default")
      (node (ref "C46") (pin "1") (pinfunction "P$1_1") (pintype "passive"))
      (node (ref "IC17") (pin "7") (pinfunction "OUT1_7") (pintype "power_in"))
      (node (ref "IC17") (pin "8") (pinfunction "OUT_8") (pintype "power_in"))
      (node (ref "L10") (pin "1") (pinfunction "P$1_1") (pintype "passive"))
      (node (ref "L11") (pin "1") (pinfunction "P$1_1") (pintype "passive"))
      (node (ref "L12") (pin "1") (pinfunction "P$1_1") (pintype "passive"))
      (node (ref "L13") (pin "1") (pinfunction "P$1_1") (pintype "passive"))
      (node (ref "L14") (pin "1") (pinfunction "P$1_1") (pintype "passive"))
      (node (ref "L15") (pin "1") (pinfunction "P$1_1") (pintype "passive"))
      (node (ref "L16") (pin "1") (pinfunction "P$1_1") (pintype "passive"))
      (node (ref "L17") (pin "1") (pinfunction "P$1_1") (pintype "passive"))
      (node (ref "L18") (pin "1") (pinfunction "P$1_1") (pintype "passive"))
      (node (ref "L19") (pin "1") (pinfunction "P$1_1") (pintype "passive"))
      (node (ref "L20") (pin "1") (pinfunction "P$1_1") (pintype "passive"))
      (node (ref "L6") (pin "1") (pinfunction "P$1_1") (pintype "passive"))
      (node (ref "R33") (pin "2") (pinfunction "2_2") (pintype "passive"))
    )
    (net (code "5") (name "1.2V_PLL1") (class "Default")
      (node (ref "C61") (pin "1") (pinfunction "P$1_1") (pintype "passive"))
      (node (ref "IC4") (pin "7") (pinfunction "VDDA_PLL_7") (pintype "power_in"))
      (node (ref "L6") (pin "2") (pinfunction "P$2_2") (pintype "passive"))
    )
    (net (code "6") (name "1.2V_PLL2") (class "Default")
      (node (ref "C75") (pin "1") (pinfunction "P$1_1") (pintype "passive"))
      (node (ref "IC5") (pin "7") (pinfunction "VDDA_PLL_7") (pintype "power_in"))
      (node (ref "L10") (pin "2") (pinfunction "P$2_2") (pintype "passive"))
    )
    (net (code "7") (name "1.2V_PLL3") (class "Default")
      (node (ref "C89") (pin "1") (pinfunction "P$1_1") (pintype "passive"))
      (node (ref "IC6") (pin "7") (pinfunction "VDDA_PLL_7") (pintype "power_in"))
      (node (ref "L11") (pin "2") (pinfunction "P$2_2") (pintype "passive"))
    )
    (net (code "8") (name "1.2V_PLL4") (class "Default")
      (node (ref "C100") (pin "1") (pinfunction "P$1_1") (pintype "passive"))
      (node (ref "IC7") (pin "7") (pinfunction "VDDA_PLL_7") (pintype "power_in"))
      (node (ref "L12") (pin "2") (pinfunction "P$2_2") (pintype "passive"))
    )
    (net (code "9") (name "1.2V_PLL5") (class "Default")
      (node (ref "C111") (pin "1") (pinfunction "P$1_1") (pintype "passive"))
      (node (ref "IC8") (pin "7") (pinfunction "VDDA_PLL_7") (pintype "power_in"))
      (node (ref "L13") (pin "2") (pinfunction "P$2_2") (pintype "passive"))
    )
    (net (code "10") (name "1.2V_PLL6") (class "Default")
      (node (ref "C122") (pin "1") (pinfunction "P$1_1") (pintype "passive"))
      (node (ref "IC9") (pin "7") (pinfunction "VDDA_PLL_7") (pintype "power_in"))
      (node (ref "L14") (pin "2") (pinfunction "P$2_2") (pintype "passive"))
    )
    (net (code "11") (name "1.2V_PLL7") (class "Default")
      (node (ref "C133") (pin "1") (pinfunction "P$1_1") (pintype "passive"))
      (node (ref "IC10") (pin "7") (pinfunction "VDDA_PLL_7") (pintype "power_in"))
      (node (ref "L15") (pin "2") (pinfunction "P$2_2") (pintype "passive"))
    )
    (net (code "12") (name "1.2V_PLL8") (class "Default")
      (node (ref "C144") (pin "1") (pinfunction "P$1_1") (pintype "passive"))
      (node (ref "IC11") (pin "7") (pinfunction "VDDA_PLL_7") (pintype "power_in"))
      (node (ref "L16") (pin "2") (pinfunction "P$2_2") (pintype "passive"))
    )
    (net (code "13") (name "1.2V_PLL9") (class "Default")
      (node (ref "C155") (pin "1") (pinfunction "P$1_1") (pintype "passive"))
      (node (ref "IC12") (pin "7") (pinfunction "VDDA_PLL_7") (pintype "power_in"))
      (node (ref "L17") (pin "2") (pinfunction "P$2_2") (pintype "passive"))
    )
    (net (code "14") (name "1.2V_PLL10") (class "Default")
      (node (ref "C166") (pin "1") (pinfunction "P$1_1") (pintype "passive"))
      (node (ref "IC13") (pin "7") (pinfunction "VDDA_PLL_7") (pintype "power_in"))
      (node (ref "L18") (pin "2") (pinfunction "P$2_2") (pintype "passive"))
    )
    (net (code "15") (name "1.2V_PLL11") (class "Default")
      (node (ref "C177") (pin "1") (pinfunction "P$1_1") (pintype "passive"))
      (node (ref "IC14") (pin "7") (pinfunction "VDDA_PLL_7") (pintype "power_in"))
      (node (ref "L19") (pin "2") (pinfunction "P$2_2") (pintype "passive"))
    )
    (net (code "16") (name "1.2V_PLL12") (class "Default")
      (node (ref "C188") (pin "1") (pinfunction "P$1_1") (pintype "passive"))
      (node (ref "IC15") (pin "7") (pinfunction "VDDA_PLL_7") (pintype "power_in"))
      (node (ref "L20") (pin "2") (pinfunction "P$2_2") (pintype "passive"))
    )
    (net (code "17") (name "3.3V") (class "Default")
      (node (ref "C101") (pin "1") (pinfunction "P$1_1") (pintype "passive"))
      (node (ref "C102") (pin "1") (pinfunction "P$1_1") (pintype "passive"))
      (node (ref "C112") (pin "1") (pinfunction "P$1_1") (pintype "passive"))
      (node (ref "C113") (pin "1") (pinfunction "P$1_1") (pintype "passive"))
      (node (ref "C123") (pin "1") (pinfunction "P$1_1") (pintype "passive"))
      (node (ref "C124") (pin "1") (pinfunction "P$1_1") (pintype "passive"))
      (node (ref "C134") (pin "1") (pinfunction "P$1_1") (pintype "passive"))
      (node (ref "C135") (pin "1") (pinfunction "P$1_1") (pintype "passive"))
      (node (ref "C145") (pin "1") (pinfunction "P$1_1") (pintype "passive"))
      (node (ref "C146") (pin "1") (pinfunction "P$1_1") (pintype "passive"))
      (node (ref "C156") (pin "1") (pinfunction "P$1_1") (pintype "passive"))
      (node (ref "C157") (pin "1") (pinfunction "P$1_1") (pintype "passive"))
      (node (ref "C167") (pin "1") (pinfunction "P$1_1") (pintype "passive"))
      (node (ref "C168") (pin "1") (pinfunction "P$1_1") (pintype "passive"))
      (node (ref "C178") (pin "1") (pinfunction "P$1_1") (pintype "passive"))
      (node (ref "C179") (pin "1") (pinfunction "P$1_1") (pintype "passive"))
      (node (ref "C189") (pin "1") (pinfunction "P$1_1") (pintype "passive"))
      (node (ref "C190") (pin "1") (pinfunction "P$1_1") (pintype "passive"))
      (node (ref "C199") (pin "1") (pinfunction "P$1_1") (pintype "passive"))
      (node (ref "C200") (pin "1") (pinfunction "P$1_1") (pintype "passive"))
      (node (ref "C201") (pin "1") (pinfunction "P$1_1") (pintype "passive"))
      (node (ref "C42") (pin "1") (pinfunction "P$1_1") (pintype "passive"))
      (node (ref "C43") (pin "1") (pinfunction "P$1_1") (pintype "passive"))
      (node (ref "C44") (pin "1") (pinfunction "P$1_1") (pintype "passive"))
      (node (ref "C55") (pin "1") (pinfunction "P$1_1") (pintype "passive"))
      (node (ref "C56") (pin "1") (pinfunction "P$1_1") (pintype "passive"))
      (node (ref "C57") (pin "1") (pinfunction "P$1_1") (pintype "passive"))
      (node (ref "C58") (pin "1") (pinfunction "P$1_1") (pintype "passive"))
      (node (ref "C59") (pin "1") (pinfunction "P$1_1") (pintype "passive"))
      (node (ref "C60") (pin "1") (pinfunction "P$1_1") (pintype "passive"))
      (node (ref "C62") (pin "1") (pinfunction "P$1_1") (pintype "passive"))
      (node (ref "C63") (pin "1") (pinfunction "P$1_1") (pintype "passive"))
      (node (ref "C72") (pin "1") (pinfunction "P$1_1") (pintype "passive"))
      (node (ref "C73") (pin "1") (pinfunction "P$1_1") (pintype "passive"))
      (node (ref "C74") (pin "2") (pinfunction "P$2_2") (pintype "passive"))
      (node (ref "C76") (pin "1") (pinfunction "P$1_1") (pintype "passive"))
      (node (ref "C77") (pin "1") (pinfunction "P$1_1") (pintype "passive"))
      (node (ref "C90") (pin "1") (pinfunction "P$1_1") (pintype "passive"))
      (node (ref "C91") (pin "1") (pinfunction "P$1_1") (pintype "passive"))
      (node (ref "IC10") (pin "24") (pinfunction "OVDD_24") (pintype "power_in"))
      (node (ref "IC10") (pin "37") (pinfunction "OVDD_37") (pintype "power_in"))
      (node (ref "IC11") (pin "24") (pinfunction "OVDD_24") (pintype "power_in"))
      (node (ref "IC11") (pin "37") (pinfunction "OVDD_37") (pintype "power_in"))
      (node (ref "IC12") (pin "24") (pinfunction "OVDD_24") (pintype "power_in"))
      (node (ref "IC12") (pin "37") (pinfunction "OVDD_37") (pintype "power_in"))
      (node (ref "IC13") (pin "24") (pinfunction "OVDD_24") (pintype "power_in"))
      (node (ref "IC13") (pin "37") (pinfunction "OVDD_37") (pintype "power_in"))
      (node (ref "IC14") (pin "24") (pinfunction "OVDD_24") (pintype "power_in"))
      (node (ref "IC14") (pin "37") (pinfunction "OVDD_37") (pintype "power_in"))
      (node (ref "IC15") (pin "24") (pinfunction "OVDD_24") (pintype "power_in"))
      (node (ref "IC15") (pin "37") (pinfunction "OVDD_37") (pintype "power_in"))
      (node (ref "IC20") (pin "6") (pinfunction "VCC_6") (pintype "power_in"))
      (node (ref "IC21") (pin "6") (pinfunction "VCC_6") (pintype "power_in"))
      (node (ref "IC22") (pin "6") (pinfunction "VCC_6") (pintype "power_in"))
      (node (ref "IC23") (pin "5") (pinfunction "VCC_5") (pintype "power_in"))
      (node (ref "IC24") (pin "5") (pinfunction "VCC_5") (pintype "power_in"))
      (node (ref "IC25") (pin "5") (pinfunction "VCC_5") (pintype "power_in"))
      (node (ref "IC26") (pin "5") (pinfunction "VCC_5") (pintype "power_in"))
      (node (ref "IC27") (pin "5") (pinfunction "VCC_5") (pintype "power_in"))
      (node (ref "IC28") (pin "5") (pinfunction "VCC_5") (pintype "power_in"))
      (node (ref "IC4") (pin "24") (pinfunction "OVDD_24") (pintype "power_in"))
      (node (ref "IC4") (pin "37") (pinfunction "OVDD_37") (pintype "power_in"))
      (node (ref "IC5") (pin "24") (pinfunction "OVDD_24") (pintype "power_in"))
      (node (ref "IC5") (pin "37") (pinfunction "OVDD_37") (pintype "power_in"))
      (node (ref "IC6") (pin "24") (pinfunction "OVDD_24") (pintype "power_in"))
      (node (ref "IC6") (pin "37") (pinfunction "OVDD_37") (pintype "power_in"))
      (node (ref "IC7") (pin "24") (pinfunction "OVDD_24") (pintype "power_in"))
      (node (ref "IC7") (pin "37") (pinfunction "OVDD_37") (pintype "power_in"))
      (node (ref "IC8") (pin "24") (pinfunction "OVDD_24") (pintype "power_in"))
      (node (ref "IC8") (pin "37") (pinfunction "OVDD_37") (pintype "power_in"))
      (node (ref "IC9") (pin "24") (pinfunction "OVDD_24") (pintype "power_in"))
      (node (ref "IC9") (pin "37") (pinfunction "OVDD_37") (pintype "power_in"))
      (node (ref "L4") (pin "2") (pinfunction "P$2_2") (pintype "passive"))
      (node (ref "L5") (pin "1") (pinfunction "P$1_1") (pintype "passive"))
      (node (ref "L7") (pin "1") (pinfunction "P$1_1") (pintype "passive"))
      (node (ref "L8") (pin "1") (pinfunction "P$1_1") (pintype "passive"))
      (node (ref "L9") (pin "1") (pinfunction "P$1_1") (pintype "passive"))
      (node (ref "R16") (pin "2") (pinfunction "2_2") (pintype "passive"))
      (node (ref "R35") (pin "1") (pinfunction "1_1") (pintype "passive"))
      (node (ref "R36") (pin "1") (pinfunction "1_1") (pintype "passive"))
      (node (ref "R37") (pin "1") (pinfunction "1_1") (pintype "passive"))
      (node (ref "R38") (pin "1") (pinfunction "1_1") (pintype "passive"))
      (node (ref "R39") (pin "1") (pinfunction "1_1") (pintype "passive"))
      (node (ref "R40") (pin "1") (pinfunction "1_1") (pintype "passive"))
    )
    (net (code "18") (name "12V") (class "Default")
      (node (ref "C1") (pin "P$1") (pinfunction "+_P$1") (pintype "passive"))
      (node (ref "C14") (pin "P$1") (pinfunction "+_P$1") (pintype "passive"))
      (node (ref "C15") (pin "P$1") (pinfunction "+_P$1") (pintype "passive"))
      (node (ref "C16") (pin "P$1") (pinfunction "+_P$1") (pintype "passive"))
      (node (ref "C2") (pin "P$1") (pinfunction "+_P$1") (pintype "passive"))
      (node (ref "C21") (pin "1") (pinfunction "P$1_1") (pintype "passive"))
      (node (ref "C22") (pin "1") (pinfunction "P$1_1") (pintype "passive"))
      (node (ref "C27") (pin "P$1") (pinfunction "+_P$1") (pintype "passive"))
      (node (ref "C28") (pin "P$1") (pinfunction "+_P$1") (pintype "passive"))
      (node (ref "C29") (pin "P$1") (pinfunction "+_P$1") (pintype "passive"))
      (node (ref "C3") (pin "P$1") (pinfunction "+_P$1") (pintype "passive"))
      (node (ref "C34") (pin "1") (pinfunction "P$1_1") (pintype "passive"))
      (node (ref "C35") (pin "1") (pinfunction "P$1_1") (pintype "passive"))
      (node (ref "C40") (pin "2") (pinfunction "P$2_2") (pintype "passive"))
      (node (ref "C41") (pin "2") (pinfunction "P$2_2") (pintype "passive"))
      (node (ref "C8") (pin "1") (pinfunction "P$1_1") (pintype "passive"))
      (node (ref "C9") (pin "1") (pinfunction "P$1_1") (pintype "passive"))
      (node (ref "IC1") (pin "5") (pinfunction "VCC_5") (pintype "power_in"))
      (node (ref "IC16") (pin "2") (pinfunction "VIN_2") (pintype "power_in"))
      (node (ref "IC16") (pin "6") (pinfunction "EN_6") (pintype "input"))
      (node (ref "IC2") (pin "5") (pinfunction "VCC_5") (pintype "power_in"))
      (node (ref "IC3") (pin "5") (pinfunction "VCC_5") (pintype "power_in"))
      (node (ref "K1") (pin "B1") (pinfunction "B1_B1") (pintype "passive"))
      (node (ref "K1") (pin "B10") (pinfunction "B10_B10") (pintype "passive"))
      (node (ref "K1") (pin "B11") (pinfunction "B11_B11") (pintype "passive"))
      (node (ref "K1") (pin "B2") (pinfunction "B2_B2") (pintype "passive"))
      (node (ref "K1") (pin "B3") (pinfunction "B3_B3") (pintype "passive"))
      (node (ref "K1") (pin "B4") (pinfunction "B4_B4") (pintype "passive"))
      (node (ref "K1") (pin "B5") (pinfunction "B5_B5") (pintype "passive"))
      (node (ref "K1") (pin "B6") (pinfunction "B6_B6") (pintype "passive"))
      (node (ref "K1") (pin "B63") (pinfunction "B63_B63") (pintype "passive"))
      (node (ref "K1") (pin "B64") (pinfunction "B64_B64") (pintype "passive"))
      (node (ref "K1") (pin "B65") (pinfunction "B65_B65") (pintype "passive"))
      (node (ref "K1") (pin "B66") (pinfunction "B66_B66") (pintype "passive"))
      (node (ref "K1") (pin "B67") (pinfunction "B67_B67") (pintype "passive"))
      (node (ref "K1") (pin "B68") (pinfunction "B68_B68") (pintype "passive"))
      (node (ref "K1") (pin "B69") (pinfunction "B69_B69") (pintype "passive"))
      (node (ref "K1") (pin "B7") (pinfunction "B7_B7") (pintype "passive"))
      (node (ref "K1") (pin "B70") (pinfunction "B70_B70") (pintype "passive"))
      (node (ref "K1") (pin "B71") (pinfunction "B71_B71") (pintype "passive"))
      (node (ref "K1") (pin "B72") (pinfunction "B72_B72") (pintype "passive"))
      (node (ref "K1") (pin "B73") (pinfunction "B73_B73") (pintype "passive"))
      (node (ref "K1") (pin "B74") (pinfunction "B74_B74") (pintype "passive"))
      (node (ref "K1") (pin "B75") (pinfunction "B75_B75") (pintype "passive"))
      (node (ref "K1") (pin "B76") (pinfunction "B76_B76") (pintype "passive"))
      (node (ref "K1") (pin "B77") (pinfunction "B77_B77") (pintype "passive"))
      (node (ref "K1") (pin "B78") (pinfunction "B78_B78") (pintype "passive"))
      (node (ref "K1") (pin "B79") (pinfunction "B79_B79") (pintype "passive"))
      (node (ref "K1") (pin "B8") (pinfunction "B8_B8") (pintype "passive"))
      (node (ref "K1") (pin "B80") (pinfunction "B80_B80") (pintype "passive"))
      (node (ref "K1") (pin "B81") (pinfunction "B81_B81") (pintype "passive"))
      (node (ref "K1") (pin "B82") (pinfunction "B82_B82") (pintype "passive"))
      (node (ref "K1") (pin "B9") (pinfunction "B9_B9") (pintype "passive"))
      (node (ref "T1") (pin "D1") (pinfunction "D1_D1") (pintype "bidirectional"))
      (node (ref "T2") (pin "D1") (pinfunction "D1_D1") (pintype "bidirectional"))
      (node (ref "T3") (pin "D1") (pinfunction "D1_D1") (pintype "bidirectional"))
    )
    (net (code "19") (name "AGND") (class "Default")
      (node (ref "C47") (pin "2") (pinfunction "P$2_2") (pintype "passive"))
      (node (ref "C48") (pin "2") (pinfunction "P$2_2") (pintype "passive"))
      (node (ref "IC16") (pin "3") (pinfunction "AGND_3") (pintype "power_in"))
      (node (ref "R17") (pin "1") (pinfunction "1_1") (pintype "passive"))
      (node (ref "VIA1") (pin "P$1") (pinfunction "P$1_P$1") (pintype "bidirectional"))
    )
    (net (code "20") (name "CLK1") (class "Default")
      (node (ref "IC4") (pin "9") (pinfunction "XCLKIN_9") (pintype "input"))
      (node (ref "R22") (pin "2") (pinfunction "2_2") (pintype "passive"))
    )
    (net (code "21") (name "CLK2") (class "Default")
      (node (ref "IC5") (pin "9") (pinfunction "XCLKIN_9") (pintype "input"))
      (node (ref "R21") (pin "2") (pinfunction "2_2") (pintype "passive"))
    )
    (net (code "22") (name "CLK3") (class "Default")
      (node (ref "IC6") (pin "9") (pinfunction "XCLKIN_9") (pintype "input"))
      (node (ref "R20") (pin "2") (pinfunction "2_2") (pintype "passive"))
    )
    (net (code "23") (name "CLK4") (class "Default")
      (node (ref "IC7") (pin "9") (pinfunction "XCLKIN_9") (pintype "input"))
      (node (ref "R19") (pin "2") (pinfunction "2_2") (pintype "passive"))
    )
    (net (code "24") (name "CLK5") (class "Default")
      (node (ref "IC8") (pin "9") (pinfunction "XCLKIN_9") (pintype "input"))
      (node (ref "R23") (pin "2") (pinfunction "2_2") (pintype "passive"))
    )
    (net (code "25") (name "CLK6") (class "Default")
      (node (ref "IC9") (pin "9") (pinfunction "XCLKIN_9") (pintype "input"))
      (node (ref "R24") (pin "2") (pinfunction "2_2") (pintype "passive"))
    )
    (net (code "26") (name "CLK7") (class "Default")
      (node (ref "IC10") (pin "9") (pinfunction "XCLKIN_9") (pintype "input"))
      (node (ref "R25") (pin "2") (pinfunction "2_2") (pintype "passive"))
    )
    (net (code "27") (name "CLK8") (class "Default")
      (node (ref "IC11") (pin "9") (pinfunction "XCLKIN_9") (pintype "input"))
      (node (ref "R26") (pin "2") (pinfunction "2_2") (pintype "passive"))
    )
    (net (code "28") (name "CLK9") (class "Default")
      (node (ref "IC12") (pin "9") (pinfunction "XCLKIN_9") (pintype "input"))
      (node (ref "R28") (pin "2") (pinfunction "2_2") (pintype "passive"))
    )
    (net (code "29") (name "CLK10") (class "Default")
      (node (ref "IC13") (pin "9") (pinfunction "XCLKIN_9") (pintype "input"))
      (node (ref "R29") (pin "2") (pinfunction "2_2") (pintype "passive"))
    )
    (net (code "30") (name "CLK11") (class "Default")
      (node (ref "IC14") (pin "9") (pinfunction "XCLKIN_9") (pintype "input"))
      (node (ref "R30") (pin "2") (pinfunction "2_2") (pintype "passive"))
    )
    (net (code "31") (name "CLK12") (class "Default")
      (node (ref "IC15") (pin "9") (pinfunction "XCLKIN_9") (pintype "input"))
      (node (ref "R31") (pin "2") (pinfunction "2_2") (pintype "passive"))
    )
    (net (code "32") (name "CNF_NI_1") (class "Default")
      (node (ref "IC23") (pin "4") (pinfunction "O_4") (pintype "output"))
      (node (ref "IC4") (pin "2") (pinfunction "CONFIG_NI_2") (pintype "input"))
    )
    (net (code "33") (name "CNF_NI_2") (class "Default")
      (node (ref "IC27") (pin "4") (pinfunction "O_4") (pintype "output"))
      (node (ref "IC8") (pin "2") (pinfunction "CONFIG_NI_2") (pintype "input"))
    )
    (net (code "34") (name "CNF_NI_3") (class "Default")
      (node (ref "IC12") (pin "2") (pinfunction "CONFIG_NI_2") (pintype "input"))
      (node (ref "IC25") (pin "4") (pinfunction "O_4") (pintype "output"))
    )
    (net (code "35") (name "CNF_PI_1") (class "Default")
      (node (ref "IC23") (pin "6") (pinfunction "O_6") (pintype "output"))
      (node (ref "IC4") (pin "1") (pinfunction "CONFIG_PI_1") (pintype "input"))
    )
    (net (code "36") (name "CNF_PI_2") (class "Default")
      (node (ref "IC27") (pin "6") (pinfunction "O_6") (pintype "output"))
      (node (ref "IC8") (pin "1") (pinfunction "CONFIG_PI_1") (pintype "input"))
    )
    (net (code "37") (name "CNF_PI_3") (class "Default")
      (node (ref "IC12") (pin "1") (pinfunction "CONFIG_PI_1") (pintype "input"))
      (node (ref "IC25") (pin "6") (pinfunction "O_6") (pintype "output"))
    )
    (net (code "38") (name "DGND") (class "Default")
      (node (ref "C100") (pin "2") (pinfunction "P$2_2") (pintype "passive"))
      (node (ref "C101") (pin "2") (pinfunction "P$2_2") (pintype "passive"))
      (node (ref "C102") (pin "2") (pinfunction "P$2_2") (pintype "passive"))
      (node (ref "C111") (pin "2") (pinfunction "P$2_2") (pintype "passive"))
      (node (ref "C112") (pin "2") (pinfunction "P$2_2") (pintype "passive"))
      (node (ref "C113") (pin "2") (pinfunction "P$2_2") (pintype "passive"))
      (node (ref "C122") (pin "2") (pinfunction "P$2_2") (pintype "passive"))
      (node (ref "C123") (pin "2") (pinfunction "P$2_2") (pintype "passive"))
      (node (ref "C124") (pin "2") (pinfunction "P$2_2") (pintype "passive"))
      (node (ref "C133") (pin "2") (pinfunction "P$2_2") (pintype "passive"))
      (node (ref "C134") (pin "2") (pinfunction "P$2_2") (pintype "passive"))
      (node (ref "C135") (pin "2") (pinfunction "P$2_2") (pintype "passive"))
      (node (ref "C144") (pin "2") (pinfunction "P$2_2") (pintype "passive"))
      (node (ref "C145") (pin "2") (pinfunction "P$2_2") (pintype "passive"))
      (node (ref "C146") (pin "2") (pinfunction "P$2_2") (pintype "passive"))
      (node (ref "C155") (pin "2") (pinfunction "P$2_2") (pintype "passive"))
      (node (ref "C156") (pin "2") (pinfunction "P$2_2") (pintype "passive"))
      (node (ref "C157") (pin "2") (pinfunction "P$2_2") (pintype "passive"))
      (node (ref "C166") (pin "2") (pinfunction "P$2_2") (pintype "passive"))
      (node (ref "C167") (pin "2") (pinfunction "P$2_2") (pintype "passive"))
      (node (ref "C168") (pin "2") (pinfunction "P$2_2") (pintype "passive"))
      (node (ref "C177") (pin "2") (pinfunction "P$2_2") (pintype "passive"))
      (node (ref "C178") (pin "2") (pinfunction "P$2_2") (pintype "passive"))
      (node (ref "C179") (pin "2") (pinfunction "P$2_2") (pintype "passive"))
      (node (ref "C188") (pin "2") (pinfunction "P$2_2") (pintype "passive"))
      (node (ref "C189") (pin "2") (pinfunction "P$2_2") (pintype "passive"))
      (node (ref "C190") (pin "2") (pinfunction "P$2_2") (pintype "passive"))
      (node (ref "C49") (pin "2") (pinfunction "P$2_2") (pintype "passive"))
      (node (ref "C50") (pin "2") (pinfunction "P$2_2") (pintype "passive"))
      (node (ref "C51") (pin "2") (pinfunction "P$2_2") (pintype "passive"))
      (node (ref "C52") (pin "2") (pinfunction "P$2_2") (pintype "passive"))
      (node (ref "C53") (pin "2") (pinfunction "P$2_2") (pintype "passive"))
      (node (ref "C54") (pin "2") (pinfunction "P$2_2") (pintype "passive"))
      (node (ref "C55") (pin "2") (pinfunction "P$2_2") (pintype "passive"))
      (node (ref "C56") (pin "2") (pinfunction "P$2_2") (pintype "passive"))
      (node (ref "C57") (pin "2") (pinfunction "P$2_2") (pintype "passive"))
      (node (ref "C58") (pin "2") (pinfunction "P$2_2") (pintype "passive"))
      (node (ref "C59") (pin "2") (pinfunction "P$2_2") (pintype "passive"))
      (node (ref "C60") (pin "2") (pinfunction "P$2_2") (pintype "passive"))
      (node (ref "C61") (pin "2") (pinfunction "P$2_2") (pintype "passive"))
      (node (ref "C62") (pin "2") (pinfunction "P$2_2") (pintype "passive"))
      (node (ref "C63") (pin "2") (pinfunction "P$2_2") (pintype "passive"))
      (node (ref "C72") (pin "2") (pinfunction "P$2_2") (pintype "passive"))
      (node (ref "C73") (pin "2") (pinfunction "P$2_2") (pintype "passive"))
      (node (ref "C74") (pin "1") (pinfunction "P$1_1") (pintype "passive"))
      (node (ref "C75") (pin "2") (pinfunction "P$2_2") (pintype "passive"))
      (node (ref "C76") (pin "2") (pinfunction "P$2_2") (pintype "passive"))
      (node (ref "C77") (pin "2") (pinfunction "P$2_2") (pintype "passive"))
      (node (ref "C89") (pin "2") (pinfunction "P$2_2") (pintype "passive"))
      (node (ref "C90") (pin "2") (pinfunction "P$2_2") (pintype "passive"))
      (node (ref "C91") (pin "2") (pinfunction "P$2_2") (pintype "passive"))
      (node (ref "IC10") (pin "23") (pinfunction "OVSS_23") (pintype "power_in"))
      (node (ref "IC10") (pin "38") (pinfunction "OVSS_38") (pintype "power_in"))
      (node (ref "IC10") (pin "8") (pinfunction "VSSA_PLL_8") (pintype "power_in"))
      (node (ref "IC11") (pin "23") (pinfunction "OVSS_23") (pintype "power_in"))
      (node (ref "IC11") (pin "38") (pinfunction "OVSS_38") (pintype "power_in"))
      (node (ref "IC11") (pin "8") (pinfunction "VSSA_PLL_8") (pintype "power_in"))
      (node (ref "IC12") (pin "23") (pinfunction "OVSS_23") (pintype "power_in"))
      (node (ref "IC12") (pin "38") (pinfunction "OVSS_38") (pintype "power_in"))
      (node (ref "IC12") (pin "8") (pinfunction "VSSA_PLL_8") (pintype "power_in"))
      (node (ref "IC13") (pin "23") (pinfunction "OVSS_23") (pintype "power_in"))
      (node (ref "IC13") (pin "38") (pinfunction "OVSS_38") (pintype "power_in"))
      (node (ref "IC13") (pin "8") (pinfunction "VSSA_PLL_8") (pintype "power_in"))
      (node (ref "IC14") (pin "23") (pinfunction "OVSS_23") (pintype "power_in"))
      (node (ref "IC14") (pin "38") (pinfunction "OVSS_38") (pintype "power_in"))
      (node (ref "IC14") (pin "8") (pinfunction "VSSA_PLL_8") (pintype "power_in"))
      (node (ref "IC15") (pin "23") (pinfunction "OVSS_23") (pintype "power_in"))
      (node (ref "IC15") (pin "38") (pinfunction "OVSS_38") (pintype "power_in"))
      (node (ref "IC15") (pin "8") (pinfunction "VSSA_PLL_8") (pintype "power_in"))
      (node (ref "IC18") (pin "6") (pinfunction "GND_6") (pintype "power_in"))
      (node (ref "IC19") (pin "10") (pinfunction "GND_10") (pintype "power_in"))
      (node (ref "IC19") (pin "13") (pinfunction "GND_13") (pintype "power_in"))
      (node (ref "IC19") (pin "17") (pinfunction "GND_17") (pintype "power_in"))
      (node (ref "IC19") (pin "2") (pinfunction "GND_2") (pintype "power_in"))
      (node (ref "IC19") (pin "6") (pinfunction "GND_6") (pintype "power_in"))
      (node (ref "IC23") (pin "2") (pinfunction "GND_2") (pintype "power_in"))
      (node (ref "IC24") (pin "2") (pinfunction "GND_2") (pintype "power_in"))
      (node (ref "IC25") (pin "2") (pinfunction "GND_2") (pintype "power_in"))
      (node (ref "IC26") (pin "2") (pinfunction "GND_2") (pintype "power_in"))
      (node (ref "IC27") (pin "2") (pinfunction "GND_2") (pintype "power_in"))
      (node (ref "IC28") (pin "2") (pinfunction "GND_2") (pintype "power_in"))
      (node (ref "IC4") (pin "23") (pinfunction "OVSS_23") (pintype "power_in"))
      (node (ref "IC4") (pin "38") (pinfunction "OVSS_38") (pintype "power_in"))
      (node (ref "IC4") (pin "8") (pinfunction "VSSA_PLL_8") (pintype "power_in"))
      (node (ref "IC5") (pin "23") (pinfunction "OVSS_23") (pintype "power_in"))
      (node (ref "IC5") (pin "38") (pinfunction "OVSS_38") (pintype "power_in"))
      (node (ref "IC5") (pin "8") (pinfunction "VSSA_PLL_8") (pintype "power_in"))
      (node (ref "IC6") (pin "23") (pinfunction "OVSS_23") (pintype "power_in"))
      (node (ref "IC6") (pin "38") (pinfunction "OVSS_38") (pintype "power_in"))
      (node (ref "IC6") (pin "8") (pinfunction "VSSA_PLL_8") (pintype "power_in"))
      (node (ref "IC7") (pin "23") (pinfunction "OVSS_23") (pintype "power_in"))
      (node (ref "IC7") (pin "38") (pinfunction "OVSS_38") (pintype "power_in"))
      (node (ref "IC7") (pin "8") (pinfunction "VSSA_PLL_8") (pintype "power_in"))
      (node (ref "IC8") (pin "23") (pinfunction "OVSS_23") (pintype "power_in"))
      (node (ref "IC8") (pin "38") (pinfunction "OVSS_38") (pintype "power_in"))
      (node (ref "IC8") (pin "8") (pinfunction "VSSA_PLL_8") (pintype "power_in"))
      (node (ref "IC9") (pin "23") (pinfunction "OVSS_23") (pintype "power_in"))
      (node (ref "IC9") (pin "38") (pinfunction "OVSS_38") (pintype "power_in"))
      (node (ref "IC9") (pin "8") (pinfunction "VSSA_PLL_8") (pintype "power_in"))
      (node (ref "K1") (pin "B26") (pinfunction "B26_B26") (pintype "passive"))
      (node (ref "K1") (pin "B27") (pinfunction "B27_B27") (pintype "passive"))
      (node (ref "K1") (pin "B28") (pinfunction "B28_B28") (pintype "passive"))
      (node (ref "K1") (pin "B29") (pinfunction "B29_B29") (pintype "passive"))
      (node (ref "K1") (pin "B30") (pinfunction "B30_B30") (pintype "passive"))
      (node (ref "K1") (pin "B31") (pinfunction "B31_B31") (pintype "passive"))
      (node (ref "K1") (pin "B32") (pinfunction "B32_B32") (pintype "passive"))
      (node (ref "K1") (pin "B33") (pinfunction "B33_B33") (pintype "passive"))
      (node (ref "K1") (pin "B34") (pinfunction "B34_B34") (pintype "passive"))
      (node (ref "K1") (pin "B35") (pinfunction "B35_B35") (pintype "passive"))
      (node (ref "K1") (pin "B36") (pinfunction "B36_B36") (pintype "passive"))
      (node (ref "K1") (pin "B37") (pinfunction "B37_B37") (pintype "passive"))
      (node (ref "K1") (pin "B38") (pinfunction "B38_B38") (pintype "passive"))
      (node (ref "K1") (pin "B39") (pinfunction "B39_B39") (pintype "passive"))
      (node (ref "K1") (pin "B40") (pinfunction "B40_B40") (pintype "passive"))
      (node (ref "K1") (pin "B41") (pinfunction "B41_B41") (pintype "passive"))
      (node (ref "K1") (pin "B42") (pinfunction "B42_B42") (pintype "passive"))
      (node (ref "K1") (pin "B43") (pinfunction "B43_B43") (pintype "passive"))
      (node (ref "K1") (pin "B44") (pinfunction "B44_B44") (pintype "passive"))
      (node (ref "K1") (pin "B45") (pinfunction "B45_B45") (pintype "passive"))
      (node (ref "K1") (pin "B46") (pinfunction "B46_B46") (pintype "passive"))
      (node (ref "K1") (pin "B47") (pinfunction "B47_B47") (pintype "passive"))
      (node (ref "K1") (pin "B48") (pinfunction "B48_B48") (pintype "passive"))
      (node (ref "K1") (pin "B49") (pinfunction "B49_B49") (pintype "passive"))
      (node (ref "K1") (pin "B50") (pinfunction "B50_B50") (pintype "passive"))
      (node (ref "K1") (pin "B51") (pinfunction "B51_B51") (pintype "passive"))
      (node (ref "K1") (pin "B52") (pinfunction "B52_B52") (pintype "passive"))
      (node (ref "K1") (pin "B53") (pinfunction "B53_B53") (pintype "passive"))
      (node (ref "K1") (pin "B54") (pinfunction "B54_B54") (pintype "passive"))
      (node (ref "K1") (pin "B55") (pinfunction "B55_B55") (pintype "passive"))
      (node (ref "K1") (pin "B56") (pinfunction "B56_B56") (pintype "passive"))
      (node (ref "VIA2") (pin "P$1") (pinfunction "P$1_P$1") (pintype "bidirectional"))
      (node (ref "VIA3") (pin "P$1") (pinfunction "P$1_P$1") (pintype "bidirectional"))
      (node (ref "X1") (pin "2") (pinfunction "GND_2") (pintype "power_in"))
    )
    (net (code "39") (name "Net-(C10-P$1)") (class "Default")
      (node (ref "C10") (pin "1") (pinfunction "P$1_1") (pintype "passive"))
      (node (ref "IC1") (pin "1") (pinfunction "BOOT_1") (pintype "bidirectional"))
    )
    (net (code "40") (name "Net-(C10-P$2)") (class "Default")
      (node (ref "C10") (pin "2") (pinfunction "P$2_2") (pintype "passive"))
      (node (ref "IC1") (pin "8") (pinfunction "PHASE_8") (pintype "bidirectional"))
      (node (ref "L1") (pin "1") (pinfunction "P$1_1") (pintype "passive"))
      (node (ref "T1") (pin "S1_D2") (pinfunction "S1_D2_S1_D2") (pintype "bidirectional"))
    )
    (net (code "41") (name "Net-(C11-P$1)") (class "Default")
      (node (ref "C11") (pin "1") (pinfunction "P$1_1") (pintype "passive"))
      (node (ref "R3") (pin "1") (pinfunction "1_1") (pintype "passive"))
    )
    (net (code "42") (name "Net-(C11-P$2)") (class "Default")
      (node (ref "C11") (pin "2") (pinfunction "P$2_2") (pintype "passive"))
      (node (ref "C12") (pin "1") (pinfunction "P$1_1") (pintype "passive"))
      (node (ref "C13") (pin "1") (pinfunction "P$1_1") (pintype "passive"))
      (node (ref "IC1") (pin "6") (pinfunction "FB_6") (pintype "input"))
      (node (ref "R1") (pin "1") (pinfunction "1_1") (pintype "passive"))
      (node (ref "R2") (pin "2") (pinfunction "2_2") (pintype "passive"))
    )
    (net (code "43") (name "Net-(C12-P$2)") (class "Default")
      (node (ref "C12") (pin "2") (pinfunction "P$2_2") (pintype "passive"))
      (node (ref "R4") (pin "1") (pinfunction "1_1") (pintype "passive"))
    )
    (net (code "44") (name "Net-(C13-P$2)") (class "Default")
      (node (ref "C13") (pin "2") (pinfunction "P$2_2") (pintype "passive"))
      (node (ref "IC1") (pin "7") (pinfunction "COMP/SD_7") (pintype "output"))
      (node (ref "R3") (pin "2") (pinfunction "2_2") (pintype "passive"))
    )
    (net (code "45") (name "Net-(C23-P$1)") (class "Default")
      (node (ref "C23") (pin "1") (pinfunction "P$1_1") (pintype "passive"))
      (node (ref "IC2") (pin "1") (pinfunction "BOOT_1") (pintype "bidirectional"))
    )
    (net (code "46") (name "Net-(C23-P$2)") (class "Default")
      (node (ref "C23") (pin "2") (pinfunction "P$2_2") (pintype "passive"))
      (node (ref "IC2") (pin "8") (pinfunction "PHASE_8") (pintype "bidirectional"))
      (node (ref "L2") (pin "1") (pinfunction "P$1_1") (pintype "passive"))
      (node (ref "T2") (pin "S1_D2") (pinfunction "S1_D2_S1_D2") (pintype "bidirectional"))
    )
    (net (code "47") (name "Net-(C24-P$1)") (class "Default")
      (node (ref "C24") (pin "1") (pinfunction "P$1_1") (pintype "passive"))
      (node (ref "R8") (pin "1") (pinfunction "1_1") (pintype "passive"))
    )
    (net (code "48") (name "Net-(C24-P$2)") (class "Default")
      (node (ref "C24") (pin "2") (pinfunction "P$2_2") (pintype "passive"))
      (node (ref "C25") (pin "1") (pinfunction "P$1_1") (pintype "passive"))
      (node (ref "C26") (pin "1") (pinfunction "P$1_1") (pintype "passive"))
      (node (ref "IC2") (pin "6") (pinfunction "FB_6") (pintype "input"))
      (node (ref "R6") (pin "1") (pinfunction "1_1") (pintype "passive"))
      (node (ref "R7") (pin "2") (pinfunction "2_2") (pintype "passive"))
    )
    (net (code "49") (name "Net-(C25-P$2)") (class "Default")
      (node (ref "C25") (pin "2") (pinfunction "P$2_2") (pintype "passive"))
      (node (ref "R9") (pin "1") (pinfunction "1_1") (pintype "passive"))
    )
    (net (code "50") (name "Net-(C26-P$2)") (class "Default")
      (node (ref "C26") (pin "2") (pinfunction "P$2_2") (pintype "passive"))
      (node (ref "IC2") (pin "7") (pinfunction "COMP/SD_7") (pintype "output"))
      (node (ref "R8") (pin "2") (pinfunction "2_2") (pintype "passive"))
    )
    (net (code "51") (name "Net-(C36-P$1)") (class "Default")
      (node (ref "C36") (pin "1") (pinfunction "P$1_1") (pintype "passive"))
      (node (ref "IC3") (pin "1") (pinfunction "BOOT_1") (pintype "bidirectional"))
    )
    (net (code "52") (name "Net-(C36-P$2)") (class "Default")
      (node (ref "C36") (pin "2") (pinfunction "P$2_2") (pintype "passive"))
      (node (ref "IC3") (pin "8") (pinfunction "PHASE_8") (pintype "bidirectional"))
      (node (ref "L3") (pin "1") (pinfunction "P$1_1") (pintype "passive"))
      (node (ref "T3") (pin "S1_D2") (pinfunction "S1_D2_S1_D2") (pintype "bidirectional"))
    )
    (net (code "53") (name "Net-(C37-P$1)") (class "Default")
      (node (ref "C37") (pin "1") (pinfunction "P$1_1") (pintype "passive"))
      (node (ref "R13") (pin "1") (pinfunction "1_1") (pintype "passive"))
    )
    (net (code "54") (name "Net-(C37-P$2)") (class "Default")
      (node (ref "C37") (pin "2") (pinfunction "P$2_2") (pintype "passive"))
      (node (ref "C38") (pin "1") (pinfunction "P$1_1") (pintype "passive"))
      (node (ref "C39") (pin "1") (pinfunction "P$1_1") (pintype "passive"))
      (node (ref "IC3") (pin "6") (pinfunction "FB_6") (pintype "input"))
      (node (ref "R11") (pin "1") (pinfunction "1_1") (pintype "passive"))
      (node (ref "R12") (pin "2") (pinfunction "2_2") (pintype "passive"))
    )
    (net (code "55") (name "Net-(C38-P$2)") (class "Default")
      (node (ref "C38") (pin "2") (pinfunction "P$2_2") (pintype "passive"))
      (node (ref "R14") (pin "1") (pinfunction "1_1") (pintype "passive"))
    )
    (net (code "56") (name "Net-(C39-P$2)") (class "Default")
      (node (ref "C39") (pin "2") (pinfunction "P$2_2") (pintype "passive"))
      (node (ref "IC3") (pin "7") (pinfunction "COMP/SD_7") (pintype "output"))
      (node (ref "R13") (pin "2") (pinfunction "2_2") (pintype "passive"))
    )
    (net (code "57") (name "Net-(C45-P$1)") (class "Default")
      (node (ref "C45") (pin "1") (pinfunction "P$1_1") (pintype "passive"))
      (node (ref "IC17") (pin "1") (pinfunction "IN_1") (pintype "power_in"))
      (node (ref "IC17") (pin "2") (pinfunction "IN1_2") (pintype "power_in"))
      (node (ref "IC17") (pin "4") (pinfunction "EN_4") (pintype "input"))
      (node (ref "L5") (pin "2") (pinfunction "P$2_2") (pintype "passive"))
    )
    (net (code "58") (name "Net-(C47-P$1)") (class "Default")
      (node (ref "C47") (pin "1") (pinfunction "P$1_1") (pintype "passive"))
      (node (ref "IC16") (pin "7") (pinfunction "SS_7") (pintype "output"))
    )
    (net (code "59") (name "Net-(C48-P$1)") (class "Default")
      (node (ref "C48") (pin "1") (pinfunction "P$1_1") (pintype "passive"))
      (node (ref "R18") (pin "1") (pinfunction "1_1") (pintype "passive"))
    )
    (net (code "60") (name "Net-(C49-P$1)") (class "Default")
      (node (ref "C49") (pin "1") (pinfunction "P$1_1") (pintype "passive"))
      (node (ref "C50") (pin "1") (pinfunction "P$1_1") (pintype "passive"))
      (node (ref "C51") (pin "1") (pinfunction "P$1_1") (pintype "passive"))
      (node (ref "C52") (pin "1") (pinfunction "P$1_1") (pintype "passive"))
      (node (ref "IC19") (pin "15") (pinfunction "VCC_15") (pintype "power_in"))
      (node (ref "IC19") (pin "20") (pinfunction "VCC_20") (pintype "power_in"))
      (node (ref "IC19") (pin "4") (pinfunction "VCC_4") (pintype "power_in"))
      (node (ref "IC19") (pin "8") (pinfunction "VCC_8") (pintype "power_in"))
      (node (ref "L8") (pin "2") (pinfunction "P$2_2") (pintype "passive"))
    )
    (net (code "61") (name "Net-(C53-P$1)") (class "Default")
      (node (ref "C53") (pin "1") (pinfunction "P$1_1") (pintype "passive"))
      (node (ref "L7") (pin "2") (pinfunction "P$2_2") (pintype "passive"))
      (node (ref "X1") (pin "1") (pinfunction "OE_1") (pintype "input"))
      (node (ref "X1") (pin "4") (pinfunction "VCC_4") (pintype "power_in"))
    )
    (net (code "62") (name "Net-(C54-P$1)") (class "Default")
      (node (ref "C54") (pin "1") (pinfunction "P$1_1") (pintype "passive"))
      (node (ref "IC18") (pin "7") (pinfunction "VDD_7") (pintype "power_in"))
      (node (ref "IC18") (pin "8") (pinfunction "OE_8") (pintype "input"))
      (node (ref "L9") (pin "2") (pinfunction "P$2_2") (pintype "passive"))
    )
    (net (code "63") (name "Net-(IC1-LGATE{slash}OCP)") (class "Default")
      (node (ref "IC1") (pin "4") (pinfunction "LGATE/OCP_4") (pintype "output"))
      (node (ref "R5") (pin "2") (pinfunction "2_2") (pintype "passive"))
      (node (ref "T1") (pin "8") (pinfunction "G2_8") (pintype "bidirectional"))
    )
    (net (code "64") (name "Net-(IC1-UGATE)") (class "Default")
      (node (ref "IC1") (pin "2") (pinfunction "UGATE_2") (pintype "output"))
      (node (ref "T1") (pin "1") (pinfunction "G1_1") (pintype "bidirectional"))
    )
    (net (code "65") (name "Net-(IC2-LGATE{slash}OCP)") (class "Default")
      (node (ref "IC2") (pin "4") (pinfunction "LGATE/OCP_4") (pintype "output"))
      (node (ref "R10") (pin "2") (pinfunction "2_2") (pintype "passive"))
      (node (ref "T2") (pin "8") (pinfunction "G2_8") (pintype "bidirectional"))
    )
    (net (code "66") (name "Net-(IC2-UGATE)") (class "Default")
      (node (ref "IC2") (pin "2") (pinfunction "UGATE_2") (pintype "output"))
      (node (ref "T2") (pin "1") (pinfunction "G1_1") (pintype "bidirectional"))
    )
    (net (code "67") (name "Net-(IC3-LGATE{slash}OCP)") (class "Default")
      (node (ref "IC3") (pin "4") (pinfunction "LGATE/OCP_4") (pintype "output"))
      (node (ref "R15") (pin "2") (pinfunction "2_2") (pintype "passive"))
      (node (ref "T3") (pin "8") (pinfunction "G2_8") (pintype "bidirectional"))
    )
    (net (code "68") (name "Net-(IC3-UGATE)") (class "Default")
      (node (ref "IC3") (pin "2") (pinfunction "UGATE_2") (pintype "output"))
      (node (ref "T3") (pin "1") (pinfunction "G1_1") (pintype "bidirectional"))
    )
    (net (code "69") (name "Net-(IC4-CONFIG_NO)") (class "Default")
      (node (ref "IC4") (pin "35") (pinfunction "CONFIG_NO_35") (pintype "output"))
      (node (ref "IC5") (pin "2") (pinfunction "CONFIG_NI_2") (pintype "input"))
    )
    (net (code "70") (name "Net-(IC4-CONFIG_PO)") (class "Default")
      (node (ref "IC4") (pin "36") (pinfunction "CONFIG_PO_36") (pintype "output"))
      (node (ref "IC5") (pin "1") (pinfunction "CONFIG_PI_1") (pintype "input"))
    )
    (net (code "71") (name "Net-(IC5-CONFIG_NO)") (class "Default")
      (node (ref "IC5") (pin "35") (pinfunction "CONFIG_NO_35") (pintype "output"))
      (node (ref "IC6") (pin "2") (pinfunction "CONFIG_NI_2") (pintype "input"))
    )
    (net (code "72") (name "Net-(IC5-CONFIG_PO)") (class "Default")
      (node (ref "IC5") (pin "36") (pinfunction "CONFIG_PO_36") (pintype "output"))
      (node (ref "IC6") (pin "1") (pinfunction "CONFIG_PI_1") (pintype "input"))
    )
    (net (code "73") (name "Net-(IC6-CONFIG_NO)") (class "Default")
      (node (ref "IC6") (pin "35") (pinfunction "CONFIG_NO_35") (pintype "output"))
      (node (ref "IC7") (pin "2") (pinfunction "CONFIG_NI_2") (pintype "input"))
    )
    (net (code "74") (name "Net-(IC6-CONFIG_PO)") (class "Default")
      (node (ref "IC6") (pin "36") (pinfunction "CONFIG_PO_36") (pintype "output"))
      (node (ref "IC7") (pin "1") (pinfunction "CONFIG_PI_1") (pintype "input"))
    )
    (net (code "75") (name "Net-(IC8-CONFIG_NO)") (class "Default")
      (node (ref "IC8") (pin "35") (pinfunction "CONFIG_NO_35") (pintype "output"))
      (node (ref "IC9") (pin "2") (pinfunction "CONFIG_NI_2") (pintype "input"))
    )
    (net (code "76") (name "Net-(IC8-CONFIG_PO)") (class "Default")
      (node (ref "IC8") (pin "36") (pinfunction "CONFIG_PO_36") (pintype "output"))
      (node (ref "IC9") (pin "1") (pinfunction "CONFIG_PI_1") (pintype "input"))
    )
    (net (code "77") (name "Net-(IC10-CONFIG_NI)") (class "Default")
      (node (ref "IC10") (pin "2") (pinfunction "CONFIG_NI_2") (pintype "input"))
      (node (ref "IC9") (pin "35") (pinfunction "CONFIG_NO_35") (pintype "output"))
    )
    (net (code "78") (name "Net-(IC10-CONFIG_NO)") (class "Default")
      (node (ref "IC10") (pin "35") (pinfunction "CONFIG_NO_35") (pintype "output"))
      (node (ref "IC11") (pin "2") (pinfunction "CONFIG_NI_2") (pintype "input"))
    )
    (net (code "79") (name "Net-(IC10-CONFIG_PI)") (class "Default")
      (node (ref "IC10") (pin "1") (pinfunction "CONFIG_PI_1") (pintype "input"))
      (node (ref "IC9") (pin "36") (pinfunction "CONFIG_PO_36") (pintype "output"))
    )
    (net (code "80") (name "Net-(IC10-CONFIG_PO)") (class "Default")
      (node (ref "IC10") (pin "36") (pinfunction "CONFIG_PO_36") (pintype "output"))
      (node (ref "IC11") (pin "1") (pinfunction "CONFIG_PI_1") (pintype "input"))
    )
    (net (code "81") (name "Net-(IC12-CONFIG_NO)") (class "Default")
      (node (ref "IC12") (pin "35") (pinfunction "CONFIG_NO_35") (pintype "output"))
      (node (ref "IC13") (pin "2") (pinfunction "CONFIG_NI_2") (pintype "input"))
    )
    (net (code "82") (name "Net-(IC12-CONFIG_PO)") (class "Default")
      (node (ref "IC12") (pin "36") (pinfunction "CONFIG_PO_36") (pintype "output"))
      (node (ref "IC13") (pin "1") (pinfunction "CONFIG_PI_1") (pintype "input"))
    )
    (net (code "83") (name "Net-(IC13-CONFIG_NO)") (class "Default")
      (node (ref "IC13") (pin "35") (pinfunction "CONFIG_NO_35") (pintype "output"))
      (node (ref "IC14") (pin "2") (pinfunction "CONFIG_NI_2") (pintype "input"))
    )
    (net (code "84") (name "Net-(IC13-CONFIG_PO)") (class "Default")
      (node (ref "IC13") (pin "36") (pinfunction "CONFIG_PO_36") (pintype "output"))
      (node (ref "IC14") (pin "1") (pinfunction "CONFIG_PI_1") (pintype "input"))
    )
    (net (code "85") (name "Net-(IC14-CONFIG_NO)") (class "Default")
      (node (ref "IC14") (pin "35") (pinfunction "CONFIG_NO_35") (pintype "output"))
      (node (ref "IC15") (pin "2") (pinfunction "CONFIG_NI_2") (pintype "input"))
    )
    (net (code "86") (name "Net-(IC14-CONFIG_PO)") (class "Default")
      (node (ref "IC14") (pin "36") (pinfunction "CONFIG_PO_36") (pintype "output"))
      (node (ref "IC15") (pin "1") (pinfunction "CONFIG_PI_1") (pintype "input"))
    )
    (net (code "87") (name "Net-(IC16-COMP)") (class "Default")
      (node (ref "IC16") (pin "5") (pinfunction "COMP_5") (pintype "output"))
      (node (ref "R18") (pin "2") (pinfunction "2_2") (pintype "passive"))
    )
    (net (code "88") (name "Net-(IC16-FB)") (class "Default")
      (node (ref "IC16") (pin "4") (pinfunction "FB_4") (pintype "input"))
      (node (ref "R16") (pin "1") (pinfunction "1_1") (pintype "passive"))
      (node (ref "R17") (pin "2") (pinfunction "2_2") (pintype "passive"))
    )
    (net (code "89") (name "Net-(IC16-LX)") (class "Default")
      (node (ref "IC16") (pin "EP") (pinfunction "LX_EP") (pintype "power_in"))
      (node (ref "L4") (pin "1") (pinfunction "P$1_1") (pintype "passive"))
    )
    (net (code "90") (name "Net-(IC17-FB)") (class "Default")
      (node (ref "IC17") (pin "6") (pinfunction "FB_6") (pintype "input"))
      (node (ref "R33") (pin "1") (pinfunction "1_1") (pintype "passive"))
      (node (ref "R34") (pin "2") (pinfunction "2_2") (pintype "passive"))
    )
    (net (code "91") (name "Net-(IC18-CLK)") (class "Default")
      (node (ref "IC18") (pin "1") (pinfunction "CLK_1") (pintype "input"))
      (node (ref "R27") (pin "2") (pinfunction "2_2") (pintype "passive"))
    )
    (net (code "92") (name "Net-(IC18-Q1)") (class "Default")
      (node (ref "IC18") (pin "2") (pinfunction "Q1_2") (pintype "output"))
      (node (ref "R28") (pin "1") (pinfunction "1_1") (pintype "passive"))
    )
    (net (code "93") (name "Net-(IC18-Q2)") (class "Default")
      (node (ref "IC18") (pin "3") (pinfunction "Q2_3") (pintype "output"))
      (node (ref "R29") (pin "1") (pinfunction "1_1") (pintype "passive"))
    )
    (net (code "94") (name "Net-(IC18-Q3)") (class "Default")
      (node (ref "IC18") (pin "4") (pinfunction "Q3_4") (pintype "output"))
      (node (ref "R30") (pin "1") (pinfunction "1_1") (pintype "passive"))
    )
    (net (code "95") (name "Net-(IC18-Q4)") (class "Default")
      (node (ref "IC18") (pin "5") (pinfunction "Q4_5") (pintype "output"))
      (node (ref "R31") (pin "1") (pinfunction "1_1") (pintype "passive"))
    )
    (net (code "96") (name "Net-(IC19-A)") (class "Default")
      (node (ref "IC19") (pin "1") (pinfunction "A_1") (pintype "input"))
      (node (ref "R32") (pin "2") (pinfunction "2_2") (pintype "passive"))
    )
    (net (code "97") (name "Net-(IC19-B0)") (class "Default")
      (node (ref "IC19") (pin "3") (pinfunction "B0_3") (pintype "output"))
      (node (ref "R19") (pin "1") (pinfunction "1_1") (pintype "passive"))
    )
    (net (code "98") (name "Net-(IC19-B1)") (class "Default")
      (node (ref "IC19") (pin "5") (pinfunction "B1_5") (pintype "output"))
      (node (ref "R20") (pin "1") (pinfunction "1_1") (pintype "passive"))
    )
    (net (code "99") (name "Net-(IC19-B2)") (class "Default")
      (node (ref "IC19") (pin "7") (pinfunction "B2_7") (pintype "output"))
      (node (ref "R21") (pin "1") (pinfunction "1_1") (pintype "passive"))
    )
    (net (code "100") (name "Net-(IC19-B3)") (class "Default")
      (node (ref "IC19") (pin "9") (pinfunction "B3_9") (pintype "output"))
      (node (ref "R22") (pin "1") (pinfunction "1_1") (pintype "passive"))
    )
    (net (code "101") (name "Net-(IC19-B4)") (class "Default")
      (node (ref "IC19") (pin "11") (pinfunction "B4_11") (pintype "output"))
      (node (ref "R23") (pin "1") (pinfunction "1_1") (pintype "passive"))
    )
    (net (code "102") (name "Net-(IC19-B5)") (class "Default")
      (node (ref "IC19") (pin "12") (pinfunction "B5_12") (pintype "output"))
      (node (ref "R24") (pin "1") (pinfunction "1_1") (pintype "passive"))
    )
    (net (code "103") (name "Net-(IC19-B7)") (class "Default")
      (node (ref "IC19") (pin "16") (pinfunction "B7_16") (pintype "output"))
      (node (ref "R25") (pin "1") (pinfunction "1_1") (pintype "passive"))
    )
    (net (code "104") (name "Net-(IC19-B8)") (class "Default")
      (node (ref "IC19") (pin "18") (pinfunction "B8_18") (pintype "output"))
      (node (ref "R26") (pin "1") (pinfunction "1_1") (pintype "passive"))
    )
    (net (code "105") (name "Net-(IC19-B9)") (class "Default")
      (node (ref "IC19") (pin "19") (pinfunction "B9_19") (pintype "output"))
      (node (ref "R27") (pin "1") (pinfunction "1_1") (pintype "passive"))
    )
    (net (code "106") (name "Net-(IC20-RSTIN)") (class "Default")
      (node (ref "IC20") (pin "5") (pinfunction "RSTIN_5") (pintype "input"))
      (node (ref "R41") (pin "1") (pinfunction "1_1") (pintype "passive"))
      (node (ref "R42") (pin "2") (pinfunction "2_2") (pintype "passive"))
    )
    (net (code "107") (name "Net-(IC21-RSTIN)") (class "Default")
      (node (ref "IC21") (pin "5") (pinfunction "RSTIN_5") (pintype "input"))
      (node (ref "R43") (pin "1") (pinfunction "1_1") (pintype "passive"))
      (node (ref "R44") (pin "2") (pinfunction "2_2") (pintype "passive"))
    )
    (net (code "108") (name "Net-(IC22-RSTIN)") (class "Default")
      (node (ref "IC22") (pin "5") (pinfunction "RSTIN_5") (pintype "input"))
      (node (ref "R45") (pin "1") (pinfunction "1_1") (pintype "passive"))
      (node (ref "R46") (pin "2") (pinfunction "2_2") (pintype "passive"))
    )
    (net (code "109") (name "Net-(IC23A-I)") (class "Default")
      (node (ref "IC23") (pin "1") (pinfunction "I_1") (pintype "input"))
      (node (ref "K1") (pin "A26") (pinfunction "A26_A26") (pintype "passive"))
    )
    (net (code "110") (name "Net-(IC23B-I)") (class "Default")
      (node (ref "IC23") (pin "3") (pinfunction "I_3") (pintype "input"))
      (node (ref "K1") (pin "A28") (pinfunction "A28_A28") (pintype "passive"))
    )
    (net (code "111") (name "Net-(IC24A-O)") (class "Default")
      (node (ref "IC24") (pin "6") (pinfunction "O_6") (pintype "output"))
      (node (ref "K1") (pin "A34") (pinfunction "A34_A34") (pintype "passive"))
    )
    (net (code "112") (name "Net-(IC24B-O)") (class "Default")
      (node (ref "IC24") (pin "4") (pinfunction "O_4") (pintype "output"))
      (node (ref "K1") (pin "A32") (pinfunction "A32_A32") (pintype "passive"))
    )
    (net (code "113") (name "Net-(IC25A-I)") (class "Default")
      (node (ref "IC25") (pin "1") (pinfunction "I_1") (pintype "input"))
      (node (ref "K1") (pin "A37") (pinfunction "A37_A37") (pintype "passive"))
    )
    (net (code "114") (name "Net-(IC25B-I)") (class "Default")
      (node (ref "IC25") (pin "3") (pinfunction "I_3") (pintype "input"))
      (node (ref "K1") (pin "A39") (pinfunction "A39_A39") (pintype "passive"))
    )
    (net (code "115") (name "Net-(IC26A-O)") (class "Default")
      (node (ref "IC26") (pin "6") (pinfunction "O_6") (pintype "output"))
      (node (ref "K1") (pin "A45") (pinfunction "A45_A45") (pintype "passive"))
    )
    (net (code "116") (name "Net-(IC26B-O)") (class "Default")
      (node (ref "IC26") (pin "4") (pinfunction "O_4") (pintype "output"))
      (node (ref "K1") (pin "A43") (pinfunction "A43_A43") (pintype "passive"))
    )
    (net (code "117") (name "Net-(IC27A-I)") (class "Default")
      (node (ref "IC27") (pin "1") (pinfunction "I_1") (pintype "input"))
      (node (ref "K1") (pin "A48") (pinfunction "A48_A48") (pintype "passive"))
    )
    (net (code "118") (name "Net-(IC27B-I)") (class "Default")
      (node (ref "IC27") (pin "3") (pinfunction "I_3") (pintype "input"))
      (node (ref "K1") (pin "A50") (pinfunction "A50_A50") (pintype "passive"))
    )
    (net (code "119") (name "Net-(IC28A-O)") (class "Default")
      (node (ref "IC28") (pin "6") (pinfunction "O_6") (pintype "output"))
      (node (ref "K1") (pin "A56") (pinfunction "A56_A56") (pintype "passive"))
    )
    (net (code "120") (name "Net-(IC28B-O)") (class "Default")
      (node (ref "IC28") (pin "4") (pinfunction "O_4") (pintype "output"))
      (node (ref "K1") (pin "A54") (pinfunction "A54_A54") (pintype "passive"))
    )
    (net (code "121") (name "Net-(X1-FO)") (class "Default")
      (node (ref "R32") (pin "1") (pinfunction "1_1") (pintype "passive"))
      (node (ref "X1") (pin "3") (pinfunction "FO_3") (pintype "output"))
    )
    (net (code "122") (name "PGND") (class "Default")
      (node (ref "C1") (pin "P$2") (pinfunction "-_P$2") (pintype "passive"))
      (node (ref "C103") (pin "2") (pinfunction "P$2_2") (pintype "passive"))
      (node (ref "C104") (pin "2") (pinfunction "P$2_2") (pintype "passive"))
      (node (ref "C105") (pin "2") (pinfunction "P$2_2") (pintype "passive"))
      (node (ref "C106") (pin "2") (pinfunction "P$2_2") (pintype "passive"))
      (node (ref "C107") (pin "2") (pinfunction "P$2_2") (pintype "passive"))
      (node (ref "C108") (pin "2") (pinfunction "P$2_2") (pintype "passive"))
      (node (ref "C109") (pin "2") (pinfunction "P$2_2") (pintype "passive"))
      (node (ref "C110") (pin "2") (pinfunction "P$2_2") (pintype "passive"))
      (node (ref "C114") (pin "2") (pinfunction "P$2_2") (pintype "passive"))
      (node (ref "C115") (pin "2") (pinfunction "P$2_2") (pintype "passive"))
      (node (ref "C116") (pin "2") (pinfunction "P$2_2") (pintype "passive"))
      (node (ref "C117") (pin "2") (pinfunction "P$2_2") (pintype "passive"))
      (node (ref "C118") (pin "2") (pinfunction "P$2_2") (pintype "passive"))
      (node (ref "C119") (pin "2") (pinfunction "P$2_2") (pintype "passive"))
      (node (ref "C120") (pin "2") (pinfunction "P$2_2") (pintype "passive"))
      (node (ref "C121") (pin "2") (pinfunction "P$2_2") (pintype "passive"))
      (node (ref "C125") (pin "2") (pinfunction "P$2_2") (pintype "passive"))
      (node (ref "C126") (pin "2") (pinfunction "P$2_2") (pintype "passive"))
      (node (ref "C127") (pin "2") (pinfunction "P$2_2") (pintype "passive"))
      (node (ref "C128") (pin "2") (pinfunction "P$2_2") (pintype "passive"))
      (node (ref "C129") (pin "2") (pinfunction "P$2_2") (pintype "passive"))
      (node (ref "C130") (pin "2") (pinfunction "P$2_2") (pintype "passive"))
      (node (ref "C131") (pin "2") (pinfunction "P$2_2") (pintype "passive"))
      (node (ref "C132") (pin "2") (pinfunction "P$2_2") (pintype "passive"))
      (node (ref "C136") (pin "2") (pinfunction "P$2_2") (pintype "passive"))
      (node (ref "C137") (pin "2") (pinfunction "P$2_2") (pintype "passive"))
      (node (ref "C138") (pin "2") (pinfunction "P$2_2") (pintype "passive"))
      (node (ref "C139") (pin "2") (pinfunction "P$2_2") (pintype "passive"))
      (node (ref "C14") (pin "P$2") (pinfunction "-_P$2") (pintype "passive"))
      (node (ref "C140") (pin "2") (pinfunction "P$2_2") (pintype "passive"))
      (node (ref "C141") (pin "2") (pinfunction "P$2_2") (pintype "passive"))
      (node (ref "C142") (pin "2") (pinfunction "P$2_2") (pintype "passive"))
      (node (ref "C143") (pin "2") (pinfunction "P$2_2") (pintype "passive"))
      (node (ref "C147") (pin "2") (pinfunction "P$2_2") (pintype "passive"))
      (node (ref "C148") (pin "2") (pinfunction "P$2_2") (pintype "passive"))
      (node (ref "C149") (pin "2") (pinfunction "P$2_2") (pintype "passive"))
      (node (ref "C15") (pin "P$2") (pinfunction "-_P$2") (pintype "passive"))
      (node (ref "C150") (pin "2") (pinfunction "P$2_2") (pintype "passive"))
      (node (ref "C151") (pin "2") (pinfunction "P$2_2") (pintype "passive"))
      (node (ref "C152") (pin "2") (pinfunction "P$2_2") (pintype "passive"))
      (node (ref "C153") (pin "2") (pinfunction "P$2_2") (pintype "passive"))
      (node (ref "C154") (pin "2") (pinfunction "P$2_2") (pintype "passive"))
      (node (ref "C158") (pin "2") (pinfunction "P$2_2") (pintype "passive"))
      (node (ref "C159") (pin "2") (pinfunction "P$2_2") (pintype "passive"))
      (node (ref "C16") (pin "P$2") (pinfunction "-_P$2") (pintype "passive"))
      (node (ref "C160") (pin "2") (pinfunction "P$2_2") (pintype "passive"))
      (node (ref "C161") (pin "2") (pinfunction "P$2_2") (pintype "passive"))
      (node (ref "C162") (pin "2") (pinfunction "P$2_2") (pintype "passive"))
      (node (ref "C163") (pin "2") (pinfunction "P$2_2") (pintype "passive"))
      (node (ref "C164") (pin "2") (pinfunction "P$2_2") (pintype "passive"))
      (node (ref "C165") (pin "2") (pinfunction "P$2_2") (pintype "passive"))
      (node (ref "C169") (pin "2") (pinfunction "P$2_2") (pintype "passive"))
      (node (ref "C17") (pin "P$2") (pinfunction "-_P$2") (pintype "passive"))
      (node (ref "C170") (pin "2") (pinfunction "P$2_2") (pintype "passive"))
      (node (ref "C171") (pin "2") (pinfunction "P$2_2") (pintype "passive"))
      (node (ref "C172") (pin "2") (pinfunction "P$2_2") (pintype "passive"))
      (node (ref "C173") (pin "2") (pinfunction "P$2_2") (pintype "passive"))
      (node (ref "C174") (pin "2") (pinfunction "P$2_2") (pintype "passive"))
      (node (ref "C175") (pin "2") (pinfunction "P$2_2") (pintype "passive"))
      (node (ref "C176") (pin "2") (pinfunction "P$2_2") (pintype "passive"))
      (node (ref "C18") (pin "2") (pinfunction "P$2_2") (pintype "passive"))
      (node (ref "C180") (pin "2") (pinfunction "P$2_2") (pintype "passive"))
      (node (ref "C181") (pin "2") (pinfunction "P$2_2") (pintype "passive"))
      (node (ref "C182") (pin "2") (pinfunction "P$2_2") (pintype "passive"))
      (node (ref "C183") (pin "2") (pinfunction "P$2_2") (pintype "passive"))
      (node (ref "C184") (pin "2") (pinfunction "P$2_2") (pintype "passive"))
      (node (ref "C185") (pin "2") (pinfunction "P$2_2") (pintype "passive"))
      (node (ref "C186") (pin "2") (pinfunction "P$2_2") (pintype "passive"))
      (node (ref "C187") (pin "2") (pinfunction "P$2_2") (pintype "passive"))
      (node (ref "C19") (pin "2") (pinfunction "P$2_2") (pintype "passive"))
      (node (ref "C191") (pin "2") (pinfunction "P$2_2") (pintype "passive"))
      (node (ref "C192") (pin "2") (pinfunction "P$2_2") (pintype "passive"))
      (node (ref "C193") (pin "2") (pinfunction "P$2_2") (pintype "passive"))
      (node (ref "C194") (pin "2") (pinfunction "P$2_2") (pintype "passive"))
      (node (ref "C195") (pin "2") (pinfunction "P$2_2") (pintype "passive"))
      (node (ref "C196") (pin "2") (pinfunction "P$2_2") (pintype "passive"))
      (node (ref "C197") (pin "2") (pinfunction "P$2_2") (pintype "passive"))
      (node (ref "C198") (pin "2") (pinfunction "P$2_2") (pintype "passive"))
      (node (ref "C199") (pin "2") (pinfunction "P$2_2") (pintype "passive"))
      (node (ref "C2") (pin "P$2") (pinfunction "-_P$2") (pintype "passive"))
      (node (ref "C20") (pin "2") (pinfunction "P$2_2") (pintype "passive"))
      (node (ref "C200") (pin "2") (pinfunction "P$2_2") (pintype "passive"))
      (node (ref "C201") (pin "2") (pinfunction "P$2_2") (pintype "passive"))
      (node (ref "C21") (pin "2") (pinfunction "P$2_2") (pintype "passive"))
      (node (ref "C22") (pin "2") (pinfunction "P$2_2") (pintype "passive"))
      (node (ref "C27") (pin "P$2") (pinfunction "-_P$2") (pintype "passive"))
      (node (ref "C28") (pin "P$2") (pinfunction "-_P$2") (pintype "passive"))
      (node (ref "C29") (pin "P$2") (pinfunction "-_P$2") (pintype "passive"))
      (node (ref "C3") (pin "P$2") (pinfunction "-_P$2") (pintype "passive"))
      (node (ref "C30") (pin "P$2") (pinfunction "-_P$2") (pintype "passive"))
      (node (ref "C31") (pin "2") (pinfunction "P$2_2") (pintype "passive"))
      (node (ref "C32") (pin "2") (pinfunction "P$2_2") (pintype "passive"))
      (node (ref "C33") (pin "2") (pinfunction "P$2_2") (pintype "passive"))
      (node (ref "C34") (pin "2") (pinfunction "P$2_2") (pintype "passive"))
      (node (ref "C35") (pin "2") (pinfunction "P$2_2") (pintype "passive"))
      (node (ref "C4") (pin "P$2") (pinfunction "-_P$2") (pintype "passive"))
      (node (ref "C40") (pin "1") (pinfunction "P$1_1") (pintype "passive"))
      (node (ref "C41") (pin "1") (pinfunction "P$1_1") (pintype "passive"))
      (node (ref "C42") (pin "2") (pinfunction "P$2_2") (pintype "passive"))
      (node (ref "C43") (pin "2") (pinfunction "P$2_2") (pintype "passive"))
      (node (ref "C44") (pin "2") (pinfunction "P$2_2") (pintype "passive"))
      (node (ref "C45") (pin "2") (pinfunction "P$2_2") (pintype "passive"))
      (node (ref "C46") (pin "2") (pinfunction "P$2_2") (pintype "passive"))
      (node (ref "C5") (pin "2") (pinfunction "P$2_2") (pintype "passive"))
      (node (ref "C6") (pin "2") (pinfunction "P$2_2") (pintype "passive"))
      (node (ref "C64") (pin "2") (pinfunction "P$2_2") (pintype "passive"))
      (node (ref "C65") (pin "2") (pinfunction "P$2_2") (pintype "passive"))
      (node (ref "C66") (pin "2") (pinfunction "P$2_2") (pintype "passive"))
      (node (ref "C67") (pin "2") (pinfunction "P$2_2") (pintype "passive"))
      (node (ref "C68") (pin "2") (pinfunction "P$2_2") (pintype "passive"))
      (node (ref "C69") (pin "2") (pinfunction "P$2_2") (pintype "passive"))
      (node (ref "C7") (pin "2") (pinfunction "P$2_2") (pintype "passive"))
      (node (ref "C70") (pin "2") (pinfunction "P$2_2") (pintype "passive"))
      (node (ref "C71") (pin "2") (pinfunction "P$2_2") (pintype "passive"))
      (node (ref "C78") (pin "2") (pinfunction "P$2_2") (pintype "passive"))
      (node (ref "C79") (pin "2") (pinfunction "P$2_2") (pintype "passive"))
      (node (ref "C8") (pin "2") (pinfunction "P$2_2") (pintype "passive"))
      (node (ref "C80") (pin "2") (pinfunction "P$2_2") (pintype "passive"))
      (node (ref "C81") (pin "2") (pinfunction "P$2_2") (pintype "passive"))
      (node (ref "C82") (pin "2") (pinfunction "P$2_2") (pintype "passive"))
      (node (ref "C83") (pin "2") (pinfunction "P$2_2") (pintype "passive"))
      (node (ref "C84") (pin "2") (pinfunction "P$2_2") (pintype "passive"))
      (node (ref "C85") (pin "2") (pinfunction "P$2_2") (pintype "passive"))
      (node (ref "C86") (pin "P$2") (pinfunction "-_P$2") (pintype "passive"))
      (node (ref "C87") (pin "P$2") (pinfunction "-_P$2") (pintype "passive"))
      (node (ref "C88") (pin "P$2") (pinfunction "-_P$2") (pintype "passive"))
      (node (ref "C9") (pin "2") (pinfunction "P$2_2") (pintype "passive"))
      (node (ref "C92") (pin "2") (pinfunction "P$2_2") (pintype "passive"))
      (node (ref "C93") (pin "2") (pinfunction "P$2_2") (pintype "passive"))
      (node (ref "C94") (pin "2") (pinfunction "P$2_2") (pintype "passive"))
      (node (ref "C95") (pin "2") (pinfunction "P$2_2") (pintype "passive"))
      (node (ref "C96") (pin "2") (pinfunction "P$2_2") (pintype "passive"))
      (node (ref "C97") (pin "2") (pinfunction "P$2_2") (pintype "passive"))
      (node (ref "C98") (pin "2") (pinfunction "P$2_2") (pintype "passive"))
      (node (ref "C99") (pin "2") (pinfunction "P$2_2") (pintype "passive"))
      (node (ref "IC1") (pin "3") (pinfunction "GND_3") (pintype "power_in"))
      (node (ref "IC10") (pin "20") (pinfunction "DVSS_20") (pintype "power_in"))
      (node (ref "IC10") (pin "32") (pinfunction "DVSS_32") (pintype "power_in"))
      (node (ref "IC10") (pin "42") (pinfunction "DVSS_42") (pintype "power_in"))
      (node (ref "IC10") (pin "5") (pinfunction "DVSS_5") (pintype "power_in"))
      (node (ref "IC10") (pin "EP") (pinfunction "EP_EP") (pintype "power_in"))
      (node (ref "IC11") (pin "20") (pinfunction "DVSS_20") (pintype "power_in"))
      (node (ref "IC11") (pin "32") (pinfunction "DVSS_32") (pintype "power_in"))
      (node (ref "IC11") (pin "42") (pinfunction "DVSS_42") (pintype "power_in"))
      (node (ref "IC11") (pin "5") (pinfunction "DVSS_5") (pintype "power_in"))
      (node (ref "IC11") (pin "EP") (pinfunction "EP_EP") (pintype "power_in"))
      (node (ref "IC12") (pin "20") (pinfunction "DVSS_20") (pintype "power_in"))
      (node (ref "IC12") (pin "32") (pinfunction "DVSS_32") (pintype "power_in"))
      (node (ref "IC12") (pin "42") (pinfunction "DVSS_42") (pintype "power_in"))
      (node (ref "IC12") (pin "5") (pinfunction "DVSS_5") (pintype "power_in"))
      (node (ref "IC12") (pin "EP") (pinfunction "EP_EP") (pintype "power_in"))
      (node (ref "IC13") (pin "20") (pinfunction "DVSS_20") (pintype "power_in"))
      (node (ref "IC13") (pin "32") (pinfunction "DVSS_32") (pintype "power_in"))
      (node (ref "IC13") (pin "42") (pinfunction "DVSS_42") (pintype "power_in"))
      (node (ref "IC13") (pin "5") (pinfunction "DVSS_5") (pintype "power_in"))
      (node (ref "IC13") (pin "EP") (pinfunction "EP_EP") (pintype "power_in"))
      (node (ref "IC14") (pin "20") (pinfunction "DVSS_20") (pintype "power_in"))
      (node (ref "IC14") (pin "32") (pinfunction "DVSS_32") (pintype "power_in"))
      (node (ref "IC14") (pin "42") (pinfunction "DVSS_42") (pintype "power_in"))
      (node (ref "IC14") (pin "5") (pinfunction "DVSS_5") (pintype "power_in"))
      (node (ref "IC14") (pin "EP") (pinfunction "EP_EP") (pintype "power_in"))
      (node (ref "IC15") (pin "20") (pinfunction "DVSS_20") (pintype "power_in"))
      (node (ref "IC15") (pin "32") (pinfunction "DVSS_32") (pintype "power_in"))
      (node (ref "IC15") (pin "42") (pinfunction "DVSS_42") (pintype "power_in"))
      (node (ref "IC15") (pin "5") (pinfunction "DVSS_5") (pintype "power_in"))
      (node (ref "IC15") (pin "EP") (pinfunction "EP_EP") (pintype "power_in"))
      (node (ref "IC16") (pin "1") (pinfunction "PGND_1") (pintype "power_in"))
      (node (ref "IC17") (pin "5") (pinfunction "GND_5") (pintype "power_in"))
      (node (ref "IC17") (pin "EP") (pinfunction "EP_EP") (pintype "power_in"))
      (node (ref "IC2") (pin "3") (pinfunction "GND_3") (pintype "power_in"))
      (node (ref "IC20") (pin "2") (pinfunction "VSS_2") (pintype "power_in"))
      (node (ref "IC21") (pin "2") (pinfunction "VSS_2") (pintype "power_in"))
      (node (ref "IC22") (pin "2") (pinfunction "VSS_2") (pintype "power_in"))
      (node (ref "IC3") (pin "3") (pinfunction "GND_3") (pintype "power_in"))
      (node (ref "IC4") (pin "20") (pinfunction "DVSS_20") (pintype "power_in"))
      (node (ref "IC4") (pin "32") (pinfunction "DVSS_32") (pintype "power_in"))
      (node (ref "IC4") (pin "42") (pinfunction "DVSS_42") (pintype "power_in"))
      (node (ref "IC4") (pin "5") (pinfunction "DVSS_5") (pintype "power_in"))
      (node (ref "IC4") (pin "EP") (pinfunction "EP_EP") (pintype "power_in"))
      (node (ref "IC5") (pin "20") (pinfunction "DVSS_20") (pintype "power_in"))
      (node (ref "IC5") (pin "32") (pinfunction "DVSS_32") (pintype "power_in"))
      (node (ref "IC5") (pin "42") (pinfunction "DVSS_42") (pintype "power_in"))
      (node (ref "IC5") (pin "5") (pinfunction "DVSS_5") (pintype "power_in"))
      (node (ref "IC5") (pin "EP") (pinfunction "EP_EP") (pintype "power_in"))
      (node (ref "IC6") (pin "20") (pinfunction "DVSS_20") (pintype "power_in"))
      (node (ref "IC6") (pin "32") (pinfunction "DVSS_32") (pintype "power_in"))
      (node (ref "IC6") (pin "42") (pinfunction "DVSS_42") (pintype "power_in"))
      (node (ref "IC6") (pin "5") (pinfunction "DVSS_5") (pintype "power_in"))
      (node (ref "IC6") (pin "EP") (pinfunction "EP_EP") (pintype "power_in"))
      (node (ref "IC7") (pin "20") (pinfunction "DVSS_20") (pintype "power_in"))
      (node (ref "IC7") (pin "32") (pinfunction "DVSS_32") (pintype "power_in"))
      (node (ref "IC7") (pin "42") (pinfunction "DVSS_42") (pintype "power_in"))
      (node (ref "IC7") (pin "5") (pinfunction "DVSS_5") (pintype "power_in"))
      (node (ref "IC7") (pin "EP") (pinfunction "EP_EP") (pintype "power_in"))
      (node (ref "IC8") (pin "20") (pinfunction "DVSS_20") (pintype "power_in"))
      (node (ref "IC8") (pin "32") (pinfunction "DVSS_32") (pintype "power_in"))
      (node (ref "IC8") (pin "42") (pinfunction "DVSS_42") (pintype "power_in"))
      (node (ref "IC8") (pin "5") (pinfunction "DVSS_5") (pintype "power_in"))
      (node (ref "IC8") (pin "EP") (pinfunction "EP_EP") (pintype "power_in"))
      (node (ref "IC9") (pin "20") (pinfunction "DVSS_20") (pintype "power_in"))
      (node (ref "IC9") (pin "32") (pinfunction "DVSS_32") (pintype "power_in"))
      (node (ref "IC9") (pin "42") (pinfunction "DVSS_42") (pintype "power_in"))
      (node (ref "IC9") (pin "5") (pinfunction "DVSS_5") (pintype "power_in"))
      (node (ref "IC9") (pin "EP") (pinfunction "EP_EP") (pintype "power_in"))
      (node (ref "K1") (pin "A1") (pinfunction "A1_A1") (pintype "passive"))
      (node (ref "K1") (pin "A10") (pinfunction "A10_A10") (pintype "passive"))
      (node (ref "K1") (pin "A11") (pinfunction "A11_A11") (pintype "passive"))
      (node (ref "K1") (pin "A2") (pinfunction "A2_A2") (pintype "passive"))
      (node (ref "K1") (pin "A3") (pinfunction "A3_A3") (pintype "passive"))
      (node (ref "K1") (pin "A4") (pinfunction "A4_A4") (pintype "passive"))
      (node (ref "K1") (pin "A5") (pinfunction "A5_A5") (pintype "passive"))
      (node (ref "K1") (pin "A6") (pinfunction "A6_A6") (pintype "passive"))
      (node (ref "K1") (pin "A63") (pinfunction "A63_A63") (pintype "passive"))
      (node (ref "K1") (pin "A64") (pinfunction "A64_A64") (pintype "passive"))
      (node (ref "K1") (pin "A65") (pinfunction "A65_A65") (pintype "passive"))
      (node (ref "K1") (pin "A66") (pinfunction "A66_A66") (pintype "passive"))
      (node (ref "K1") (pin "A67") (pinfunction "A67_A67") (pintype "passive"))
      (node (ref "K1") (pin "A68") (pinfunction "A68_A68") (pintype "passive"))
      (node (ref "K1") (pin "A69") (pinfunction "A69_A69") (pintype "passive"))
      (node (ref "K1") (pin "A7") (pinfunction "A7_A7") (pintype "passive"))
      (node (ref "K1") (pin "A70") (pinfunction "A70_A70") (pintype "passive"))
      (node (ref "K1") (pin "A71") (pinfunction "A71_A71") (pintype "passive"))
      (node (ref "K1") (pin "A72") (pinfunction "A72_A72") (pintype "passive"))
      (node (ref "K1") (pin "A73") (pinfunction "A73_A73") (pintype "passive"))
      (node (ref "K1") (pin "A74") (pinfunction "A74_A74") (pintype "passive"))
      (node (ref "K1") (pin "A75") (pinfunction "A75_A75") (pintype "passive"))
      (node (ref "K1") (pin "A76") (pinfunction "A76_A76") (pintype "passive"))
      (node (ref "K1") (pin "A77") (pinfunction "A77_A77") (pintype "passive"))
      (node (ref "K1") (pin "A78") (pinfunction "A78_A78") (pintype "passive"))
      (node (ref "K1") (pin "A79") (pinfunction "A79_A79") (pintype "passive"))
      (node (ref "K1") (pin "A8") (pinfunction "A8_A8") (pintype "passive"))
      (node (ref "K1") (pin "A80") (pinfunction "A80_A80") (pintype "passive"))
      (node (ref "K1") (pin "A81") (pinfunction "A81_A81") (pintype "passive"))
      (node (ref "K1") (pin "A82") (pinfunction "A82_A82") (pintype "passive"))
      (node (ref "K1") (pin "A9") (pinfunction "A9_A9") (pintype "passive"))
      (node (ref "R10") (pin "1") (pinfunction "1_1") (pintype "passive"))
      (node (ref "R12") (pin "1") (pinfunction "1_1") (pintype "passive"))
      (node (ref "R15") (pin "1") (pinfunction "1_1") (pintype "passive"))
      (node (ref "R2") (pin "1") (pinfunction "1_1") (pintype "passive"))
      (node (ref "R34") (pin "1") (pinfunction "1_1") (pintype "passive"))
      (node (ref "R42") (pin "1") (pinfunction "1_1") (pintype "passive"))
      (node (ref "R44") (pin "1") (pinfunction "1_1") (pintype "passive"))
      (node (ref "R46") (pin "1") (pinfunction "1_1") (pintype "passive"))
      (node (ref "R5") (pin "1") (pinfunction "1_1") (pintype "passive"))
      (node (ref "R7") (pin "1") (pinfunction "1_1") (pintype "passive"))
      (node (ref "T1") (pin "5") (pinfunction "S2_5") (pintype "bidirectional"))
      (node (ref "T1") (pin "6") (pinfunction "S2_6") (pintype "bidirectional"))
      (node (ref "T1") (pin "7") (pinfunction "S2_7") (pintype "bidirectional"))
      (node (ref "T2") (pin "5") (pinfunction "S2_5") (pintype "bidirectional"))
      (node (ref "T2") (pin "6") (pinfunction "S2_6") (pintype "bidirectional"))
      (node (ref "T2") (pin "7") (pinfunction "S2_7") (pintype "bidirectional"))
      (node (ref "T3") (pin "5") (pinfunction "S2_5") (pintype "bidirectional"))
      (node (ref "T3") (pin "6") (pinfunction "S2_6") (pintype "bidirectional"))
      (node (ref "T3") (pin "7") (pinfunction "S2_7") (pintype "bidirectional"))
      (node (ref "VIA1") (pin "P$2") (pinfunction "P$2_P$2") (pintype "bidirectional"))
      (node (ref "VIA2") (pin "P$2") (pinfunction "P$2_P$2") (pintype "bidirectional"))
      (node (ref "VIA3") (pin "P$2") (pinfunction "P$2_P$2") (pintype "bidirectional"))
    )
    (net (code "123") (name "REP_N1") (class "Default")
      (node (ref "IC24") (pin "3") (pinfunction "I_3") (pintype "input"))
      (node (ref "IC4") (pin "17") (pinfunction "REPORT_N_17") (pintype "output"))
      (node (ref "IC5") (pin "17") (pinfunction "REPORT_N_17") (pintype "output"))
      (node (ref "IC6") (pin "17") (pinfunction "REPORT_N_17") (pintype "output"))
      (node (ref "IC7") (pin "17") (pinfunction "REPORT_N_17") (pintype "output"))
      (node (ref "R35") (pin "2") (pinfunction "2_2") (pintype "passive"))
    )
    (net (code "124") (name "REP_N2") (class "Default")
      (node (ref "IC10") (pin "17") (pinfunction "REPORT_N_17") (pintype "output"))
      (node (ref "IC11") (pin "17") (pinfunction "REPORT_N_17") (pintype "output"))
      (node (ref "IC28") (pin "3") (pinfunction "I_3") (pintype "input"))
      (node (ref "IC8") (pin "17") (pinfunction "REPORT_N_17") (pintype "output"))
      (node (ref "IC9") (pin "17") (pinfunction "REPORT_N_17") (pintype "output"))
      (node (ref "R39") (pin "2") (pinfunction "2_2") (pintype "passive"))
    )
    (net (code "125") (name "REP_N3") (class "Default")
      (node (ref "IC12") (pin "17") (pinfunction "REPORT_N_17") (pintype "output"))
      (node (ref "IC13") (pin "17") (pinfunction "REPORT_N_17") (pintype "output"))
      (node (ref "IC14") (pin "17") (pinfunction "REPORT_N_17") (pintype "output"))
      (node (ref "IC15") (pin "17") (pinfunction "REPORT_N_17") (pintype "output"))
      (node (ref "IC26") (pin "3") (pinfunction "I_3") (pintype "input"))
      (node (ref "R37") (pin "2") (pinfunction "2_2") (pintype "passive"))
    )
    (net (code "126") (name "REP_P1") (class "Default")
      (node (ref "IC24") (pin "1") (pinfunction "I_1") (pintype "input"))
      (node (ref "IC4") (pin "18") (pinfunction "REPORT_P_18") (pintype "output"))
      (node (ref "IC5") (pin "18") (pinfunction "REPORT_P_18") (pintype "output"))
      (node (ref "IC6") (pin "18") (pinfunction "REPORT_P_18") (pintype "output"))
      (node (ref "IC7") (pin "18") (pinfunction "REPORT_P_18") (pintype "output"))
      (node (ref "R36") (pin "2") (pinfunction "2_2") (pintype "passive"))
    )
    (net (code "127") (name "REP_P2") (class "Default")
      (node (ref "IC10") (pin "18") (pinfunction "REPORT_P_18") (pintype "output"))
      (node (ref "IC11") (pin "18") (pinfunction "REPORT_P_18") (pintype "output"))
      (node (ref "IC28") (pin "1") (pinfunction "I_1") (pintype "input"))
      (node (ref "IC8") (pin "18") (pinfunction "REPORT_P_18") (pintype "output"))
      (node (ref "IC9") (pin "18") (pinfunction "REPORT_P_18") (pintype "output"))
      (node (ref "R40") (pin "2") (pinfunction "2_2") (pintype "passive"))
    )
    (net (code "128") (name "REP_P3") (class "Default")
      (node (ref "IC12") (pin "18") (pinfunction "REPORT_P_18") (pintype "output"))
      (node (ref "IC13") (pin "18") (pinfunction "REPORT_P_18") (pintype "output"))
      (node (ref "IC14") (pin "18") (pinfunction "REPORT_P_18") (pintype "output"))
      (node (ref "IC15") (pin "18") (pinfunction "REPORT_P_18") (pintype "output"))
      (node (ref "IC26") (pin "1") (pinfunction "I_1") (pintype "input"))
      (node (ref "R38") (pin "2") (pinfunction "2_2") (pintype "passive"))
    )
    (net (code "129") (name "RST1") (class "Default")
      (node (ref "IC20") (pin "1") (pinfunction "~{RESET}_1") (pintype "output"))
      (node (ref "IC4") (pin "45") (pinfunction "RSTN_45") (pintype "input"))
      (node (ref "IC5") (pin "45") (pinfunction "RSTN_45") (pintype "input"))
      (node (ref "IC6") (pin "45") (pinfunction "RSTN_45") (pintype "input"))
      (node (ref "IC7") (pin "45") (pinfunction "RSTN_45") (pintype "input"))
    )
    (net (code "130") (name "RST2") (class "Default")
      (node (ref "IC10") (pin "45") (pinfunction "RSTN_45") (pintype "input"))
      (node (ref "IC11") (pin "45") (pinfunction "RSTN_45") (pintype "input"))
      (node (ref "IC21") (pin "1") (pinfunction "~{RESET}_1") (pintype "output"))
      (node (ref "IC8") (pin "45") (pinfunction "RSTN_45") (pintype "input"))
      (node (ref "IC9") (pin "45") (pinfunction "RSTN_45") (pintype "input"))
    )
    (net (code "131") (name "RST3") (class "Default")
      (node (ref "IC12") (pin "45") (pinfunction "RSTN_45") (pintype "input"))
      (node (ref "IC13") (pin "45") (pinfunction "RSTN_45") (pintype "input"))
      (node (ref "IC14") (pin "45") (pinfunction "RSTN_45") (pintype "input"))
      (node (ref "IC15") (pin "45") (pinfunction "RSTN_45") (pintype "input"))
      (node (ref "IC22") (pin "1") (pinfunction "~{RESET}_1") (pintype "output"))
    )
    (net (code "132") (name "unconnected-(IC4-CLKOUT-Pad10)") (class "Default")
      (node (ref "IC4") (pin "10") (pinfunction "CLKOUT_10") (pintype "output"))
    )
    (net (code "133") (name "unconnected-(IC4-CORE_CLKOUT-Pad44)") (class "Default")
      (node (ref "IC4") (pin "44") (pinfunction "CORE_CLKOUT_44") (pintype "output"))
    )
    (net (code "134") (name "unconnected-(IC4-DBG0-Pad30)") (class "Default")
      (node (ref "IC4") (pin "30") (pinfunction "DBG0_30") (pintype "output"))
    )
    (net (code "135") (name "unconnected-(IC4-DBG1-Pad29)") (class "Default")
      (node (ref "IC4") (pin "29") (pinfunction "DBG1_29") (pintype "output"))
    )
    (net (code "136") (name "unconnected-(IC5-CLKOUT-Pad10)") (class "Default")
      (node (ref "IC5") (pin "10") (pinfunction "CLKOUT_10") (pintype "output"))
    )
    (net (code "137") (name "unconnected-(IC5-CORE_CLKOUT-Pad44)") (class "Default")
      (node (ref "IC5") (pin "44") (pinfunction "CORE_CLKOUT_44") (pintype "output"))
    )
    (net (code "138") (name "unconnected-(IC5-DBG0-Pad30)") (class "Default")
      (node (ref "IC5") (pin "30") (pinfunction "DBG0_30") (pintype "output"))
    )
    (net (code "139") (name "unconnected-(IC5-DBG1-Pad29)") (class "Default")
      (node (ref "IC5") (pin "29") (pinfunction "DBG1_29") (pintype "output"))
    )
    (net (code "140") (name "unconnected-(IC6-CLKOUT-Pad10)") (class "Default")
      (node (ref "IC6") (pin "10") (pinfunction "CLKOUT_10") (pintype "output"))
    )
    (net (code "141") (name "unconnected-(IC6-CORE_CLKOUT-Pad44)") (class "Default")
      (node (ref "IC6") (pin "44") (pinfunction "CORE_CLKOUT_44") (pintype "output"))
    )
    (net (code "142") (name "unconnected-(IC6-DBG0-Pad30)") (class "Default")
      (node (ref "IC6") (pin "30") (pinfunction "DBG0_30") (pintype "output"))
    )
    (net (code "143") (name "unconnected-(IC6-DBG1-Pad29)") (class "Default")
      (node (ref "IC6") (pin "29") (pinfunction "DBG1_29") (pintype "output"))
    )
    (net (code "144") (name "unconnected-(IC7-CLKOUT-Pad10)") (class "Default")
      (node (ref "IC7") (pin "10") (pinfunction "CLKOUT_10") (pintype "output"))
    )
    (net (code "145") (name "unconnected-(IC7-CONFIG_NO-Pad35)") (class "Default")
      (node (ref "IC7") (pin "35") (pinfunction "CONFIG_NO_35") (pintype "output"))
    )
    (net (code "146") (name "unconnected-(IC7-CONFIG_PO-Pad36)") (class "Default")
      (node (ref "IC7") (pin "36") (pinfunction "CONFIG_PO_36") (pintype "output"))
    )
    (net (code "147") (name "unconnected-(IC7-CORE_CLKOUT-Pad44)") (class "Default")
      (node (ref "IC7") (pin "44") (pinfunction "CORE_CLKOUT_44") (pintype "output"))
    )
    (net (code "148") (name "unconnected-(IC7-DBG0-Pad30)") (class "Default")
      (node (ref "IC7") (pin "30") (pinfunction "DBG0_30") (pintype "output"))
    )
    (net (code "149") (name "unconnected-(IC7-DBG1-Pad29)") (class "Default")
      (node (ref "IC7") (pin "29") (pinfunction "DBG1_29") (pintype "output"))
    )
    (net (code "150") (name "unconnected-(IC8-CLKOUT-Pad10)") (class "Default")
      (node (ref "IC8") (pin "10") (pinfunction "CLKOUT_10") (pintype "output"))
    )
    (net (code "151") (name "unconnected-(IC8-CORE_CLKOUT-Pad44)") (class "Default")
      (node (ref "IC8") (pin "44") (pinfunction "CORE_CLKOUT_44") (pintype "output"))
    )
    (net (code "152") (name "unconnected-(IC8-DBG0-Pad30)") (class "Default")
      (node (ref "IC8") (pin "30") (pinfunction "DBG0_30") (pintype "output"))
    )
    (net (code "153") (name "unconnected-(IC8-DBG1-Pad29)") (class "Default")
      (node (ref "IC8") (pin "29") (pinfunction "DBG1_29") (pintype "output"))
    )
    (net (code "154") (name "unconnected-(IC9-CLKOUT-Pad10)") (class "Default")
      (node (ref "IC9") (pin "10") (pinfunction "CLKOUT_10") (pintype "output"))
    )
    (net (code "155") (name "unconnected-(IC9-CORE_CLKOUT-Pad44)") (class "Default")
      (node (ref "IC9") (pin "44") (pinfunction "CORE_CLKOUT_44") (pintype "output"))
    )
    (net (code "156") (name "unconnected-(IC9-DBG0-Pad30)") (class "Default")
      (node (ref "IC9") (pin "30") (pinfunction "DBG0_30") (pintype "output"))
    )
    (net (code "157") (name "unconnected-(IC9-DBG1-Pad29)") (class "Default")
      (node (ref "IC9") (pin "29") (pinfunction "DBG1_29") (pintype "output"))
    )
    (net (code "158") (name "unconnected-(IC10-CLKOUT-Pad10)") (class "Default")
      (node (ref "IC10") (pin "10") (pinfunction "CLKOUT_10") (pintype "output"))
    )
    (net (code "159") (name "unconnected-(IC10-CORE_CLKOUT-Pad44)") (class "Default")
      (node (ref "IC10") (pin "44") (pinfunction "CORE_CLKOUT_44") (pintype "output"))
    )
    (net (code "160") (name "unconnected-(IC10-DBG0-Pad30)") (class "Default")
      (node (ref "IC10") (pin "30") (pinfunction "DBG0_30") (pintype "output"))
    )
    (net (code "161") (name "unconnected-(IC10-DBG1-Pad29)") (class "Default")
      (node (ref "IC10") (pin "29") (pinfunction "DBG1_29") (pintype "output"))
    )
    (net (code "162") (name "unconnected-(IC11-CLKOUT-Pad10)") (class "Default")
      (node (ref "IC11") (pin "10") (pinfunction "CLKOUT_10") (pintype "output"))
    )
    (net (code "163") (name "unconnected-(IC11-CONFIG_NO-Pad35)") (class "Default")
      (node (ref "IC11") (pin "35") (pinfunction "CONFIG_NO_35") (pintype "output"))
    )
    (net (code "164") (name "unconnected-(IC11-CONFIG_PO-Pad36)") (class "Default")
      (node (ref "IC11") (pin "36") (pinfunction "CONFIG_PO_36") (pintype "output"))
    )
    (net (code "165") (name "unconnected-(IC11-CORE_CLKOUT-Pad44)") (class "Default")
      (node (ref "IC11") (pin "44") (pinfunction "CORE_CLKOUT_44") (pintype "output"))
    )
    (net (code "166") (name "unconnected-(IC11-DBG0-Pad30)") (class "Default")
      (node (ref "IC11") (pin "30") (pinfunction "DBG0_30") (pintype "output"))
    )
    (net (code "167") (name "unconnected-(IC11-DBG1-Pad29)") (class "Default")
      (node (ref "IC11") (pin "29") (pinfunction "DBG1_29") (pintype "output"))
    )
    (net (code "168") (name "unconnected-(IC12-CLKOUT-Pad10)") (class "Default")
      (node (ref "IC12") (pin "10") (pinfunction "CLKOUT_10") (pintype "output"))
    )
    (net (code "169") (name "unconnected-(IC12-CORE_CLKOUT-Pad44)") (class "Default")
      (node (ref "IC12") (pin "44") (pinfunction "CORE_CLKOUT_44") (pintype "output"))
    )
    (net (code "170") (name "unconnected-(IC12-DBG0-Pad30)") (class "Default")
      (node (ref "IC12") (pin "30") (pinfunction "DBG0_30") (pintype "output"))
    )
    (net (code "171") (name "unconnected-(IC12-DBG1-Pad29)") (class "Default")
      (node (ref "IC12") (pin "29") (pinfunction "DBG1_29") (pintype "output"))
    )
    (net (code "172") (name "unconnected-(IC13-CLKOUT-Pad10)") (class "Default")
      (node (ref "IC13") (pin "10") (pinfunction "CLKOUT_10") (pintype "output"))
    )
    (net (code "173") (name "unconnected-(IC13-CORE_CLKOUT-Pad44)") (class "Default")
      (node (ref "IC13") (pin "44") (pinfunction "CORE_CLKOUT_44") (pintype "output"))
    )
    (net (code "174") (name "unconnected-(IC13-DBG0-Pad30)") (class "Default")
      (node (ref "IC13") (pin "30") (pinfunction "DBG0_30") (pintype "output"))
    )
    (net (code "175") (name "unconnected-(IC13-DBG1-Pad29)") (class "Default")
      (node (ref "IC13") (pin "29") (pinfunction "DBG1_29") (pintype "output"))
    )
    (net (code "176") (name "unconnected-(IC14-CLKOUT-Pad10)") (class "Default")
      (node (ref "IC14") (pin "10") (pinfunction "CLKOUT_10") (pintype "output"))
    )
    (net (code "177") (name "unconnected-(IC14-CORE_CLKOUT-Pad44)") (class "Default")
      (node (ref "IC14") (pin "44") (pinfunction "CORE_CLKOUT_44") (pintype "output"))
    )
    (net (code "178") (name "unconnected-(IC14-DBG0-Pad30)") (class "Default")
      (node (ref "IC14") (pin "30") (pinfunction "DBG0_30") (pintype "output"))
    )
    (net (code "179") (name "unconnected-(IC14-DBG1-Pad29)") (class "Default")
      (node (ref "IC14") (pin "29") (pinfunction "DBG1_29") (pintype "output"))
    )
    (net (code "180") (name "unconnected-(IC15-CLKOUT-Pad10)") (class "Default")
      (node (ref "IC15") (pin "10") (pinfunction "CLKOUT_10") (pintype "output"))
    )
    (net (code "181") (name "unconnected-(IC15-CONFIG_NO-Pad35)") (class "Default")
      (node (ref "IC15") (pin "35") (pinfunction "CONFIG_NO_35") (pintype "output"))
    )
    (net (code "182") (name "unconnected-(IC15-CONFIG_PO-Pad36)") (class "Default")
      (node (ref "IC15") (pin "36") (pinfunction "CONFIG_PO_36") (pintype "output"))
    )
    (net (code "183") (name "unconnected-(IC15-CORE_CLKOUT-Pad44)") (class "Default")
      (node (ref "IC15") (pin "44") (pinfunction "CORE_CLKOUT_44") (pintype "output"))
    )
    (net (code "184") (name "unconnected-(IC15-DBG0-Pad30)") (class "Default")
      (node (ref "IC15") (pin "30") (pinfunction "DBG0_30") (pintype "output"))
    )
    (net (code "185") (name "unconnected-(IC15-DBG1-Pad29)") (class "Default")
      (node (ref "IC15") (pin "29") (pinfunction "DBG1_29") (pintype "output"))
    )
    (net (code "186") (name "unconnected-(IC17-POK-Pad3)") (class "Default")
      (node (ref "IC17") (pin "3") (pinfunction "POK_3") (pintype "output"))
    )
    (net (code "187") (name "unconnected-(IC19-B6-Pad14)") (class "Default")
      (node (ref "IC19") (pin "14") (pinfunction "B6_14") (pintype "output"))
    )
    (net (code "188") (name "unconnected-(IC20-MRC-Pad4)") (class "Default")
      (node (ref "IC20") (pin "4") (pinfunction "MRC_4") (pintype "input"))
    )
    (net (code "189") (name "unconnected-(IC20-~{MR}-Pad3)") (class "Default")
      (node (ref "IC20") (pin "3") (pinfunction "~{MR}_3") (pintype "input"))
    )
    (net (code "190") (name "unconnected-(IC21-MRC-Pad4)") (class "Default")
      (node (ref "IC21") (pin "4") (pinfunction "MRC_4") (pintype "input"))
    )
    (net (code "191") (name "unconnected-(IC21-~{MR}-Pad3)") (class "Default")
      (node (ref "IC21") (pin "3") (pinfunction "~{MR}_3") (pintype "input"))
    )
    (net (code "192") (name "unconnected-(IC22-MRC-Pad4)") (class "Default")
      (node (ref "IC22") (pin "4") (pinfunction "MRC_4") (pintype "input"))
    )
    (net (code "193") (name "unconnected-(IC22-~{MR}-Pad3)") (class "Default")
      (node (ref "IC22") (pin "3") (pinfunction "~{MR}_3") (pintype "input"))
    )
    (net (code "194") (name "unconnected-(K1-PadA12)") (class "Default")
      (node (ref "K1") (pin "A12") (pinfunction "A12_A12") (pintype "passive"))
    )
    (net (code "195") (name "unconnected-(K1-PadA13)") (class "Default")
      (node (ref "K1") (pin "A13") (pinfunction "A13_A13") (pintype "passive"))
    )
    (net (code "196") (name "unconnected-(K1-PadA14)") (class "Default")
      (node (ref "K1") (pin "A14") (pinfunction "A14_A14") (pintype "passive"))
    )
    (net (code "197") (name "unconnected-(K1-PadA15)") (class "Default")
      (node (ref "K1") (pin "A15") (pinfunction "A15_A15") (pintype "passive"))
    )
    (net (code "198") (name "unconnected-(K1-PadA16)") (class "Default")
      (node (ref "K1") (pin "A16") (pinfunction "A16_A16") (pintype "passive"))
    )
    (net (code "199") (name "unconnected-(K1-PadA17)") (class "Default")
      (node (ref "K1") (pin "A17") (pinfunction "A17_A17") (pintype "passive"))
    )
    (net (code "200") (name "unconnected-(K1-PadA18)") (class "Default")
      (node (ref "K1") (pin "A18") (pinfunction "A18_A18") (pintype "passive"))
    )
    (net (code "201") (name "unconnected-(K1-PadA19)") (class "Default")
      (node (ref "K1") (pin "A19") (pinfunction "A19_A19") (pintype "passive"))
    )
    (net (code "202") (name "unconnected-(K1-PadA20)") (class "Default")
      (node (ref "K1") (pin "A20") (pinfunction "A20_A20") (pintype "passive"))
    )
    (net (code "203") (name "unconnected-(K1-PadA21)") (class "Default")
      (node (ref "K1") (pin "A21") (pinfunction "A21_A21") (pintype "passive"))
    )
    (net (code "204") (name "unconnected-(K1-PadA22)") (class "Default")
      (node (ref "K1") (pin "A22") (pinfunction "A22_A22") (pintype "passive"))
    )
    (net (code "205") (name "unconnected-(K1-PadA23)") (class "Default")
      (node (ref "K1") (pin "A23") (pinfunction "A23_A23") (pintype "passive"))
    )
    (net (code "206") (name "unconnected-(K1-PadA24)") (class "Default")
      (node (ref "K1") (pin "A24") (pinfunction "A24_A24") (pintype "passive"))
    )
    (net (code "207") (name "unconnected-(K1-PadA25)") (class "Default")
      (node (ref "K1") (pin "A25") (pinfunction "A25_A25") (pintype "passive"))
    )
    (net (code "208") (name "unconnected-(K1-PadA27)") (class "Default")
      (node (ref "K1") (pin "A27") (pinfunction "A27_A27") (pintype "passive"))
    )
    (net (code "209") (name "unconnected-(K1-PadA29)") (class "Default")
      (node (ref "K1") (pin "A29") (pinfunction "A29_A29") (pintype "passive"))
    )
    (net (code "210") (name "unconnected-(K1-PadA30)") (class "Default")
      (node (ref "K1") (pin "A30") (pinfunction "A30_A30") (pintype "passive"))
    )
    (net (code "211") (name "unconnected-(K1-PadA31)") (class "Default")
      (node (ref "K1") (pin "A31") (pinfunction "A31_A31") (pintype "passive"))
    )
    (net (code "212") (name "unconnected-(K1-PadA33)") (class "Default")
      (node (ref "K1") (pin "A33") (pinfunction "A33_A33") (pintype "passive"))
    )
    (net (code "213") (name "unconnected-(K1-PadA35)") (class "Default")
      (node (ref "K1") (pin "A35") (pinfunction "A35_A35") (pintype "passive"))
    )
    (net (code "214") (name "unconnected-(K1-PadA36)") (class "Default")
      (node (ref "K1") (pin "A36") (pinfunction "A36_A36") (pintype "passive"))
    )
    (net (code "215") (name "unconnected-(K1-PadA38)") (class "Default")
      (node (ref "K1") (pin "A38") (pinfunction "A38_A38") (pintype "passive"))
    )
    (net (code "216") (name "unconnected-(K1-PadA40)") (class "Default")
      (node (ref "K1") (pin "A40") (pinfunction "A40_A40") (pintype "passive"))
    )
    (net (code "217") (name "unconnected-(K1-PadA41)") (class "Default")
      (node (ref "K1") (pin "A41") (pinfunction "A41_A41") (pintype "passive"))
    )
    (net (code "218") (name "unconnected-(K1-PadA42)") (class "Default")
      (node (ref "K1") (pin "A42") (pinfunction "A42_A42") (pintype "passive"))
    )
    (net (code "219") (name "unconnected-(K1-PadA44)") (class "Default")
      (node (ref "K1") (pin "A44") (pinfunction "A44_A44") (pintype "passive"))
    )
    (net (code "220") (name "unconnected-(K1-PadA46)") (class "Default")
      (node (ref "K1") (pin "A46") (pinfunction "A46_A46") (pintype "passive"))
    )
    (net (code "221") (name "unconnected-(K1-PadA47)") (class "Default")
      (node (ref "K1") (pin "A47") (pinfunction "A47_A47") (pintype "passive"))
    )
    (net (code "222") (name "unconnected-(K1-PadA49)") (class "Default")
      (node (ref "K1") (pin "A49") (pinfunction "A49_A49") (pintype "passive"))
    )
    (net (code "223") (name "unconnected-(K1-PadA51)") (class "Default")
      (node (ref "K1") (pin "A51") (pinfunction "A51_A51") (pintype "passive"))
    )
    (net (code "224") (name "unconnected-(K1-PadA52)") (class "Default")
      (node (ref "K1") (pin "A52") (pinfunction "A52_A52") (pintype "passive"))
    )
    (net (code "225") (name "unconnected-(K1-PadA53)") (class "Default")
      (node (ref "K1") (pin "A53") (pinfunction "A53_A53") (pintype "passive"))
    )
    (net (code "226") (name "unconnected-(K1-PadA55)") (class "Default")
      (node (ref "K1") (pin "A55") (pinfunction "A55_A55") (pintype "passive"))
    )
    (net (code "227") (name "unconnected-(K1-PadA57)") (class "Default")
      (node (ref "K1") (pin "A57") (pinfunction "A57_A57") (pintype "passive"))
    )
    (net (code "228") (name "unconnected-(K1-PadA58)") (class "Default")
      (node (ref "K1") (pin "A58") (pinfunction "A58_A58") (pintype "passive"))
    )
    (net (code "229") (name "unconnected-(K1-PadA59)") (class "Default")
      (node (ref "K1") (pin "A59") (pinfunction "A59_A59") (pintype "passive"))
    )
    (net (code "230") (name "unconnected-(K1-PadA60)") (class "Default")
      (node (ref "K1") (pin "A60") (pinfunction "A60_A60") (pintype "passive"))
    )
    (net (code "231") (name "unconnected-(K1-PadA61)") (class "Default")
      (node (ref "K1") (pin "A61") (pinfunction "A61_A61") (pintype "passive"))
    )
    (net (code "232") (name "unconnected-(K1-PadA62)") (class "Default")
      (node (ref "K1") (pin "A62") (pinfunction "A62_A62") (pintype "passive"))
    )
    (net (code "233") (name "unconnected-(K1-PadB12)") (class "Default")
      (node (ref "K1") (pin "B12") (pinfunction "B12_B12") (pintype "passive"))
    )
    (net (code "234") (name "unconnected-(K1-PadB13)") (class "Default")
      (node (ref "K1") (pin "B13") (pinfunction "B13_B13") (pintype "passive"))
    )
    (net (code "235") (name "unconnected-(K1-PadB14)") (class "Default")
      (node (ref "K1") (pin "B14") (pinfunction "B14_B14") (pintype "passive"))
    )
    (net (code "236") (name "unconnected-(K1-PadB15)") (class "Default")
      (node (ref "K1") (pin "B15") (pinfunction "B15_B15") (pintype "passive"))
    )
    (net (code "237") (name "unconnected-(K1-PadB16)") (class "Default")
      (node (ref "K1") (pin "B16") (pinfunction "B16_B16") (pintype "passive"))
    )
    (net (code "238") (name "unconnected-(K1-PadB17)") (class "Default")
      (node (ref "K1") (pin "B17") (pinfunction "B17_B17") (pintype "passive"))
    )
    (net (code "239") (name "unconnected-(K1-PadB18)") (class "Default")
      (node (ref "K1") (pin "B18") (pinfunction "B18_B18") (pintype "passive"))
    )
    (net (code "240") (name "unconnected-(K1-PadB19)") (class "Default")
      (node (ref "K1") (pin "B19") (pinfunction "B19_B19") (pintype "passive"))
    )
    (net (code "241") (name "unconnected-(K1-PadB20)") (class "Default")
      (node (ref "K1") (pin "B20") (pinfunction "B20_B20") (pintype "passive"))
    )
    (net (code "242") (name "unconnected-(K1-PadB21)") (class "Default")
      (node (ref "K1") (pin "B21") (pinfunction "B21_B21") (pintype "passive"))
    )
    (net (code "243") (name "unconnected-(K1-PadB22)") (class "Default")
      (node (ref "K1") (pin "B22") (pinfunction "B22_B22") (pintype "passive"))
    )
    (net (code "244") (name "unconnected-(K1-PadB23)") (class "Default")
      (node (ref "K1") (pin "B23") (pinfunction "B23_B23") (pintype "passive"))
    )
    (net (code "245") (name "unconnected-(K1-PadB24)") (class "Default")
      (node (ref "K1") (pin "B24") (pinfunction "B24_B24") (pintype "passive"))
    )
    (net (code "246") (name "unconnected-(K1-PadB25)") (class "Default")
      (node (ref "K1") (pin "B25") (pinfunction "B25_B25") (pintype "passive"))
    )
    (net (code "247") (name "unconnected-(K1-PadB57)") (class "Default")
      (node (ref "K1") (pin "B57") (pinfunction "B57_B57") (pintype "passive"))
    )
    (net (code "248") (name "unconnected-(K1-PadB58)") (class "Default")
      (node (ref "K1") (pin "B58") (pinfunction "B58_B58") (pintype "passive"))
    )
    (net (code "249") (name "unconnected-(K1-PadB59)") (class "Default")
      (node (ref "K1") (pin "B59") (pinfunction "B59_B59") (pintype "passive"))
    )
    (net (code "250") (name "unconnected-(K1-PadB60)") (class "Default")
      (node (ref "K1") (pin "B60") (pinfunction "B60_B60") (pintype "passive"))
    )
    (net (code "251") (name "unconnected-(K1-PadB61)") (class "Default")
      (node (ref "K1") (pin "B61") (pinfunction "B61_B61") (pintype "passive"))
    )
    (net (code "252") (name "unconnected-(K1-PadB62)") (class "Default")
      (node (ref "K1") (pin "B62") (pinfunction "B62_B62") (pintype "passive"))
    )
  )
)
